# OSD62-PM-BRK.net
KiCad netlist of a schematic drawn in EAGLE
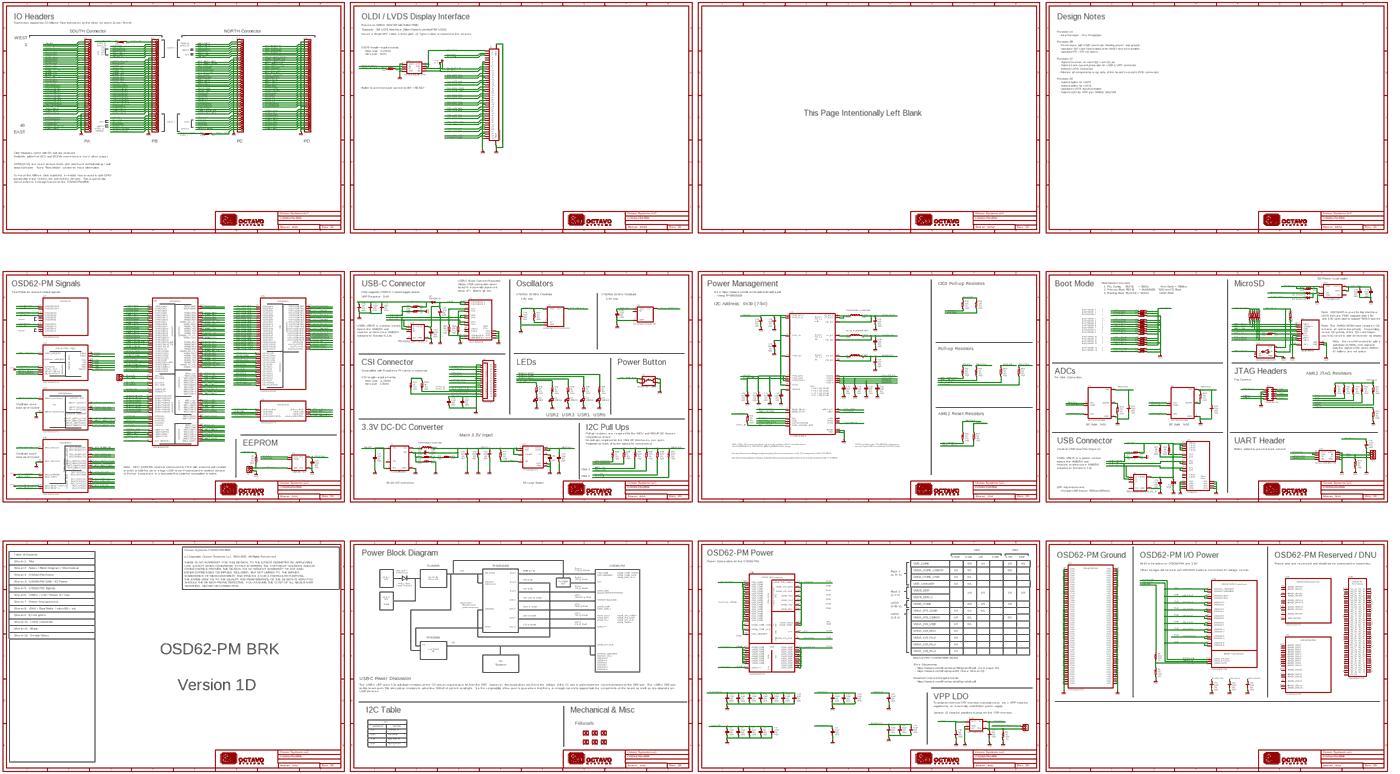
[diagram p0: schematic, sheet 1, overview]
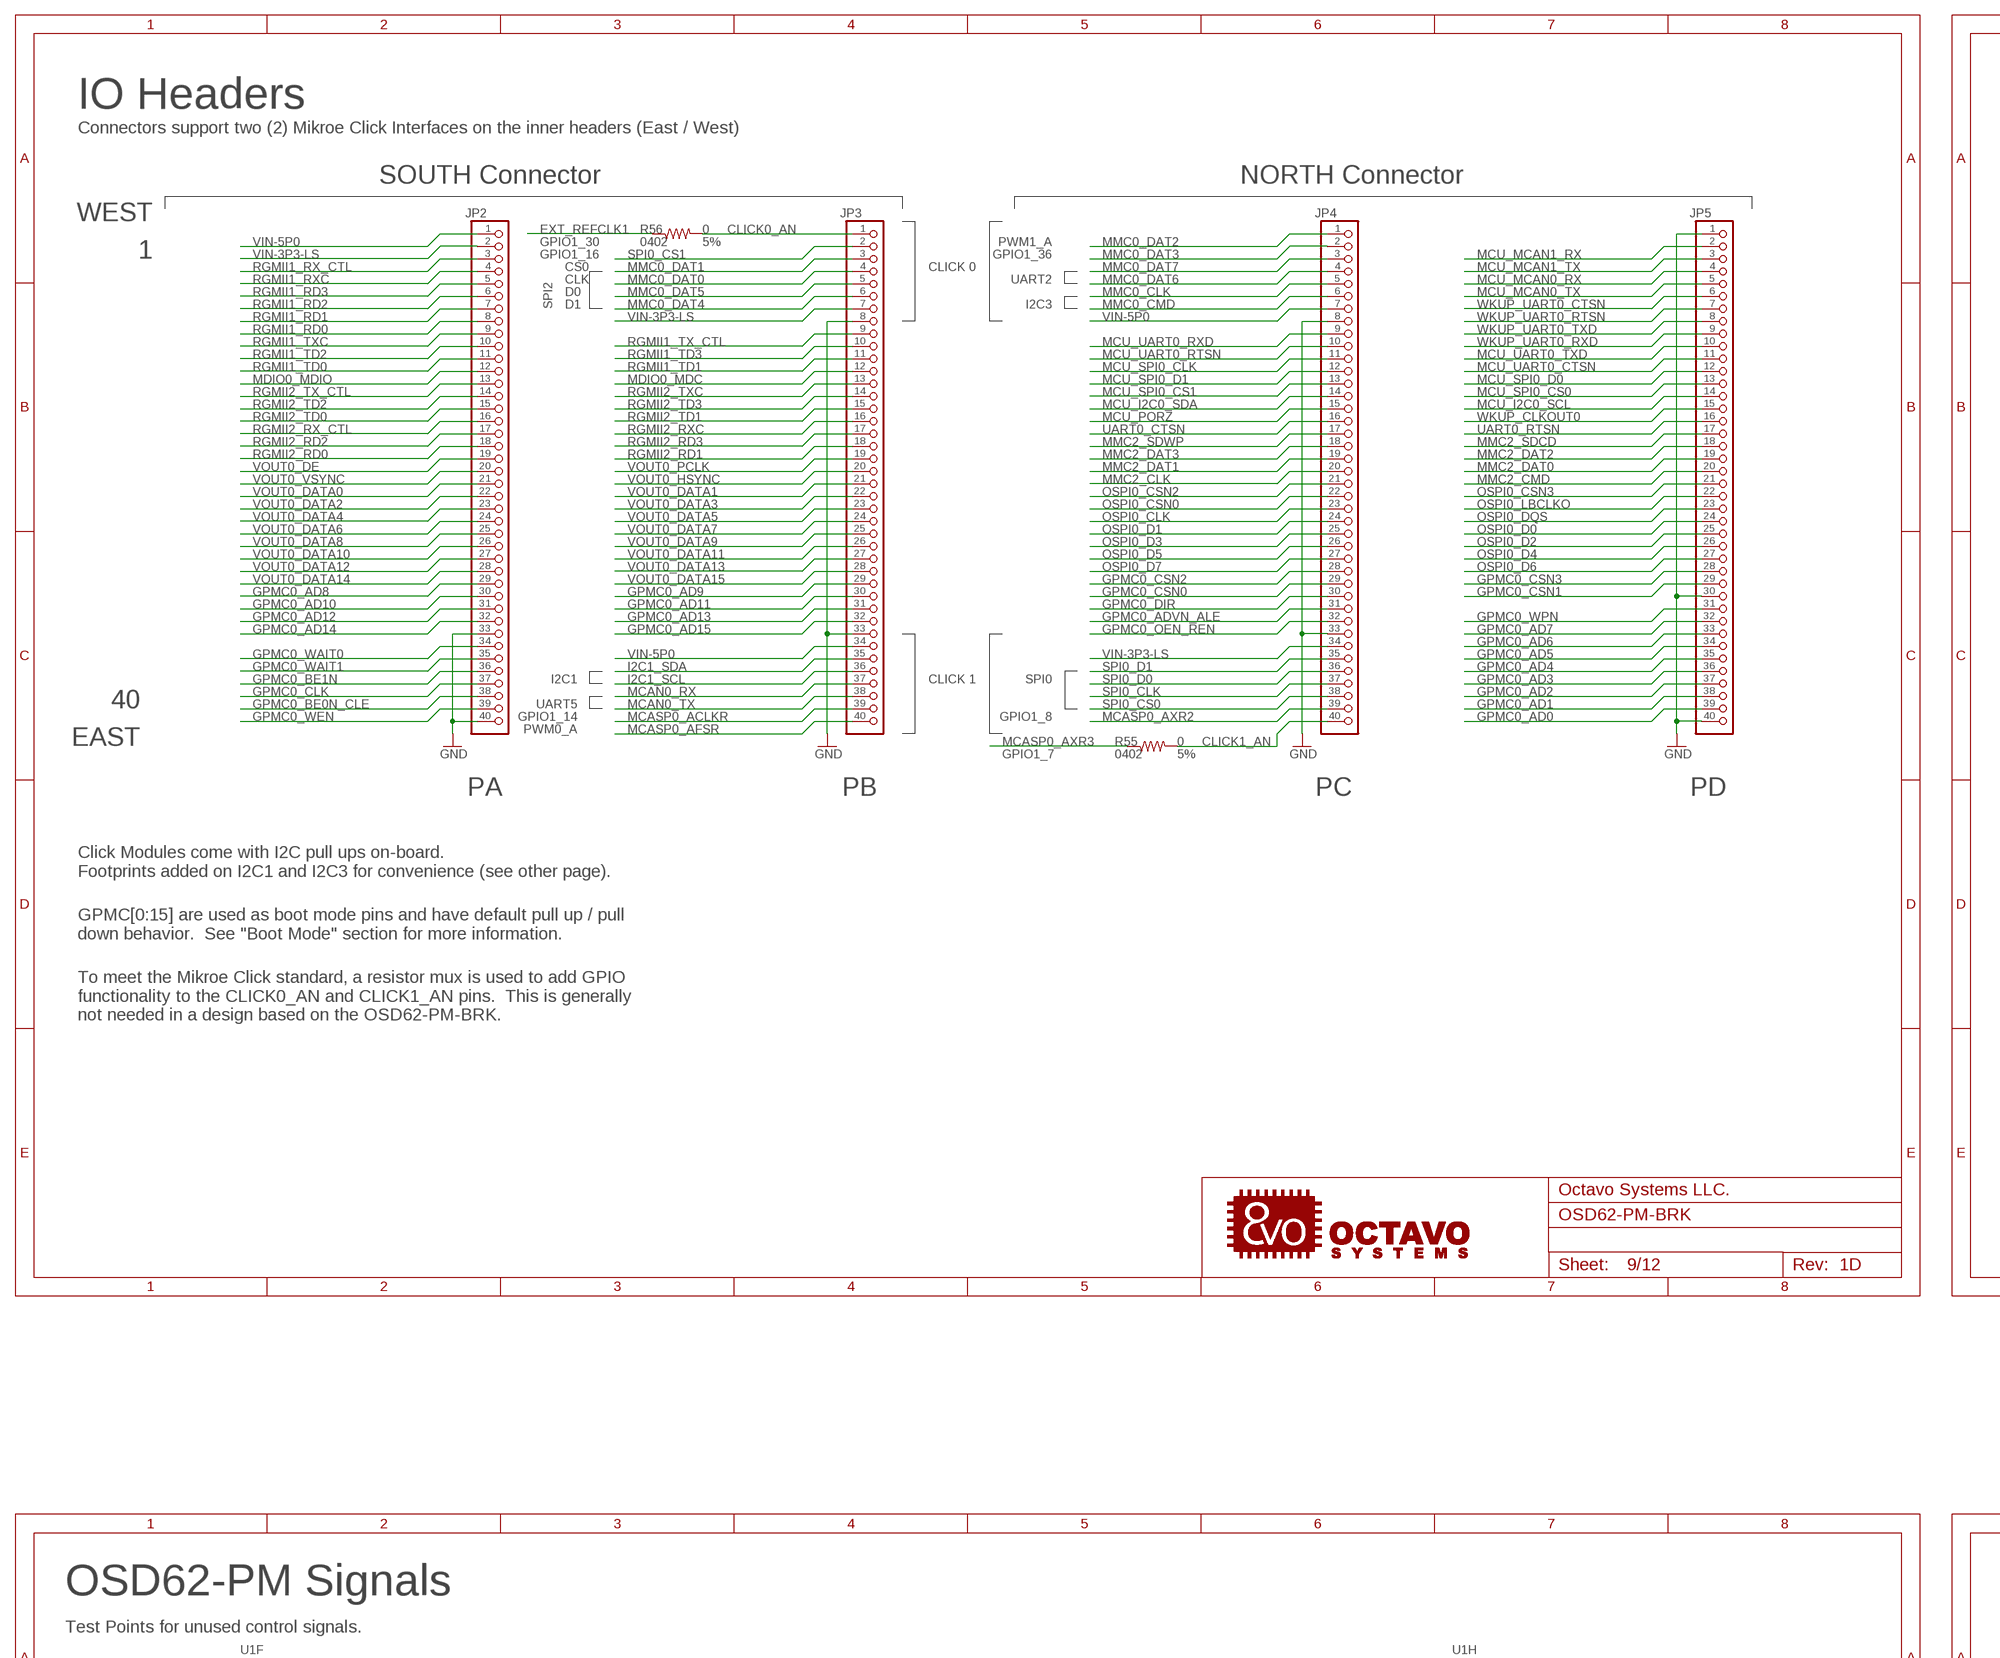
[diagram p1: schematic, sheet 1, part 1 of 8]
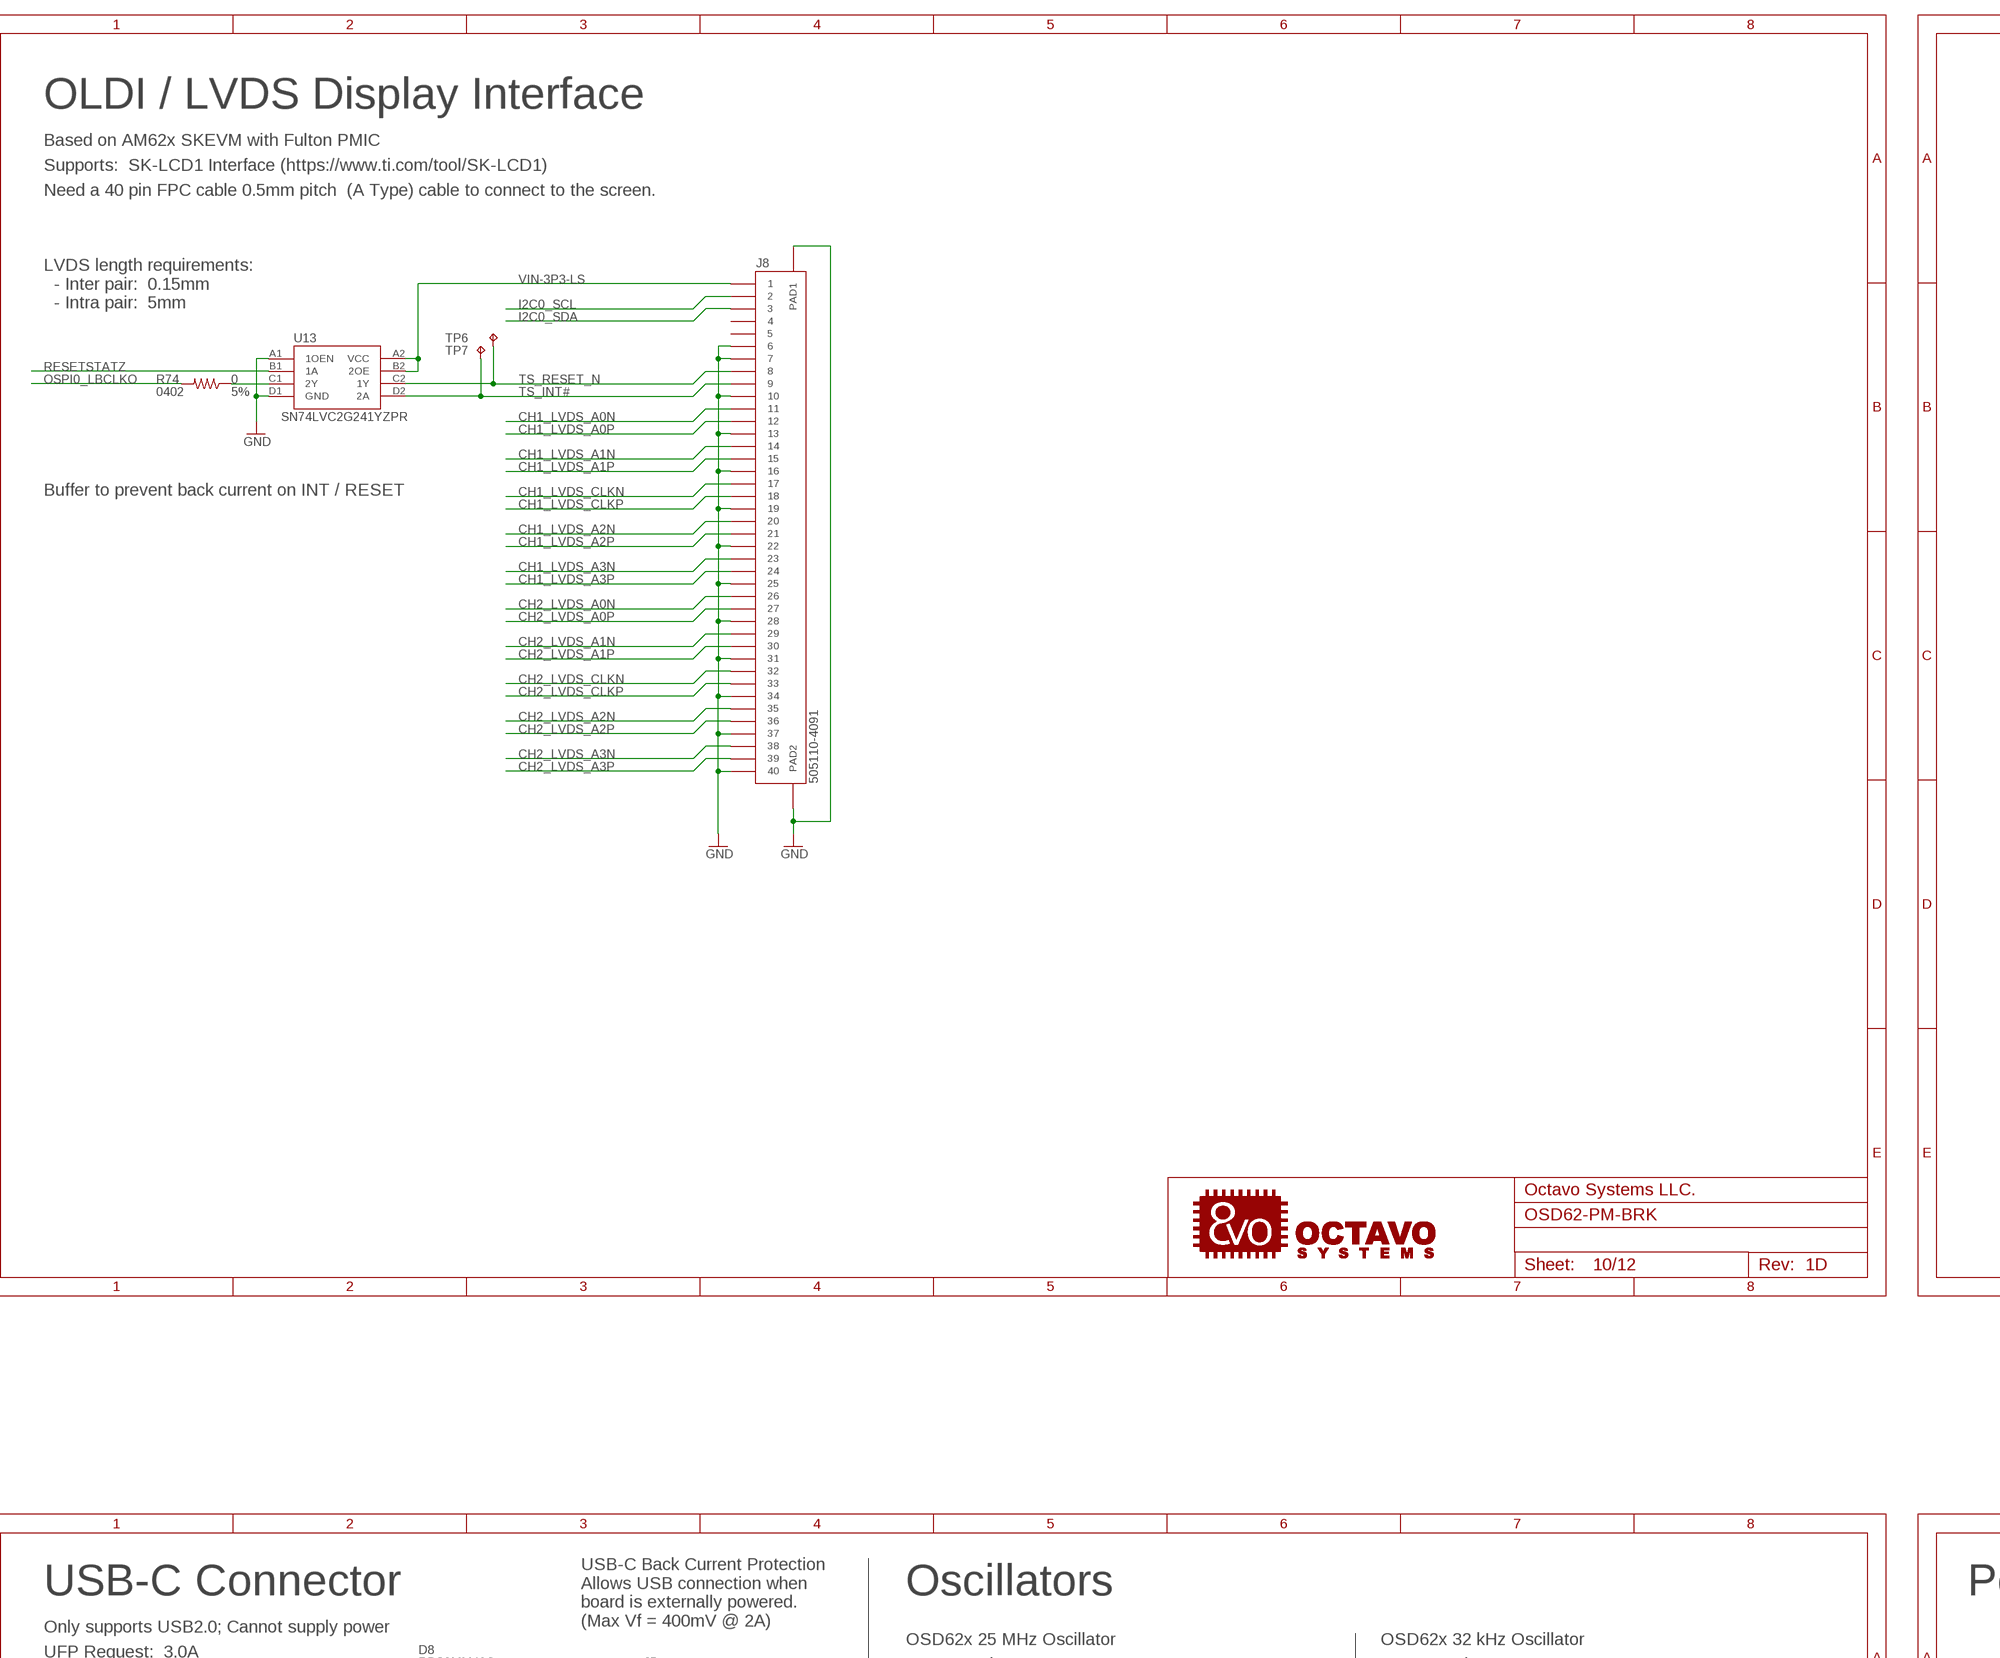
[diagram p2: schematic, sheet 1, part 2 of 8]
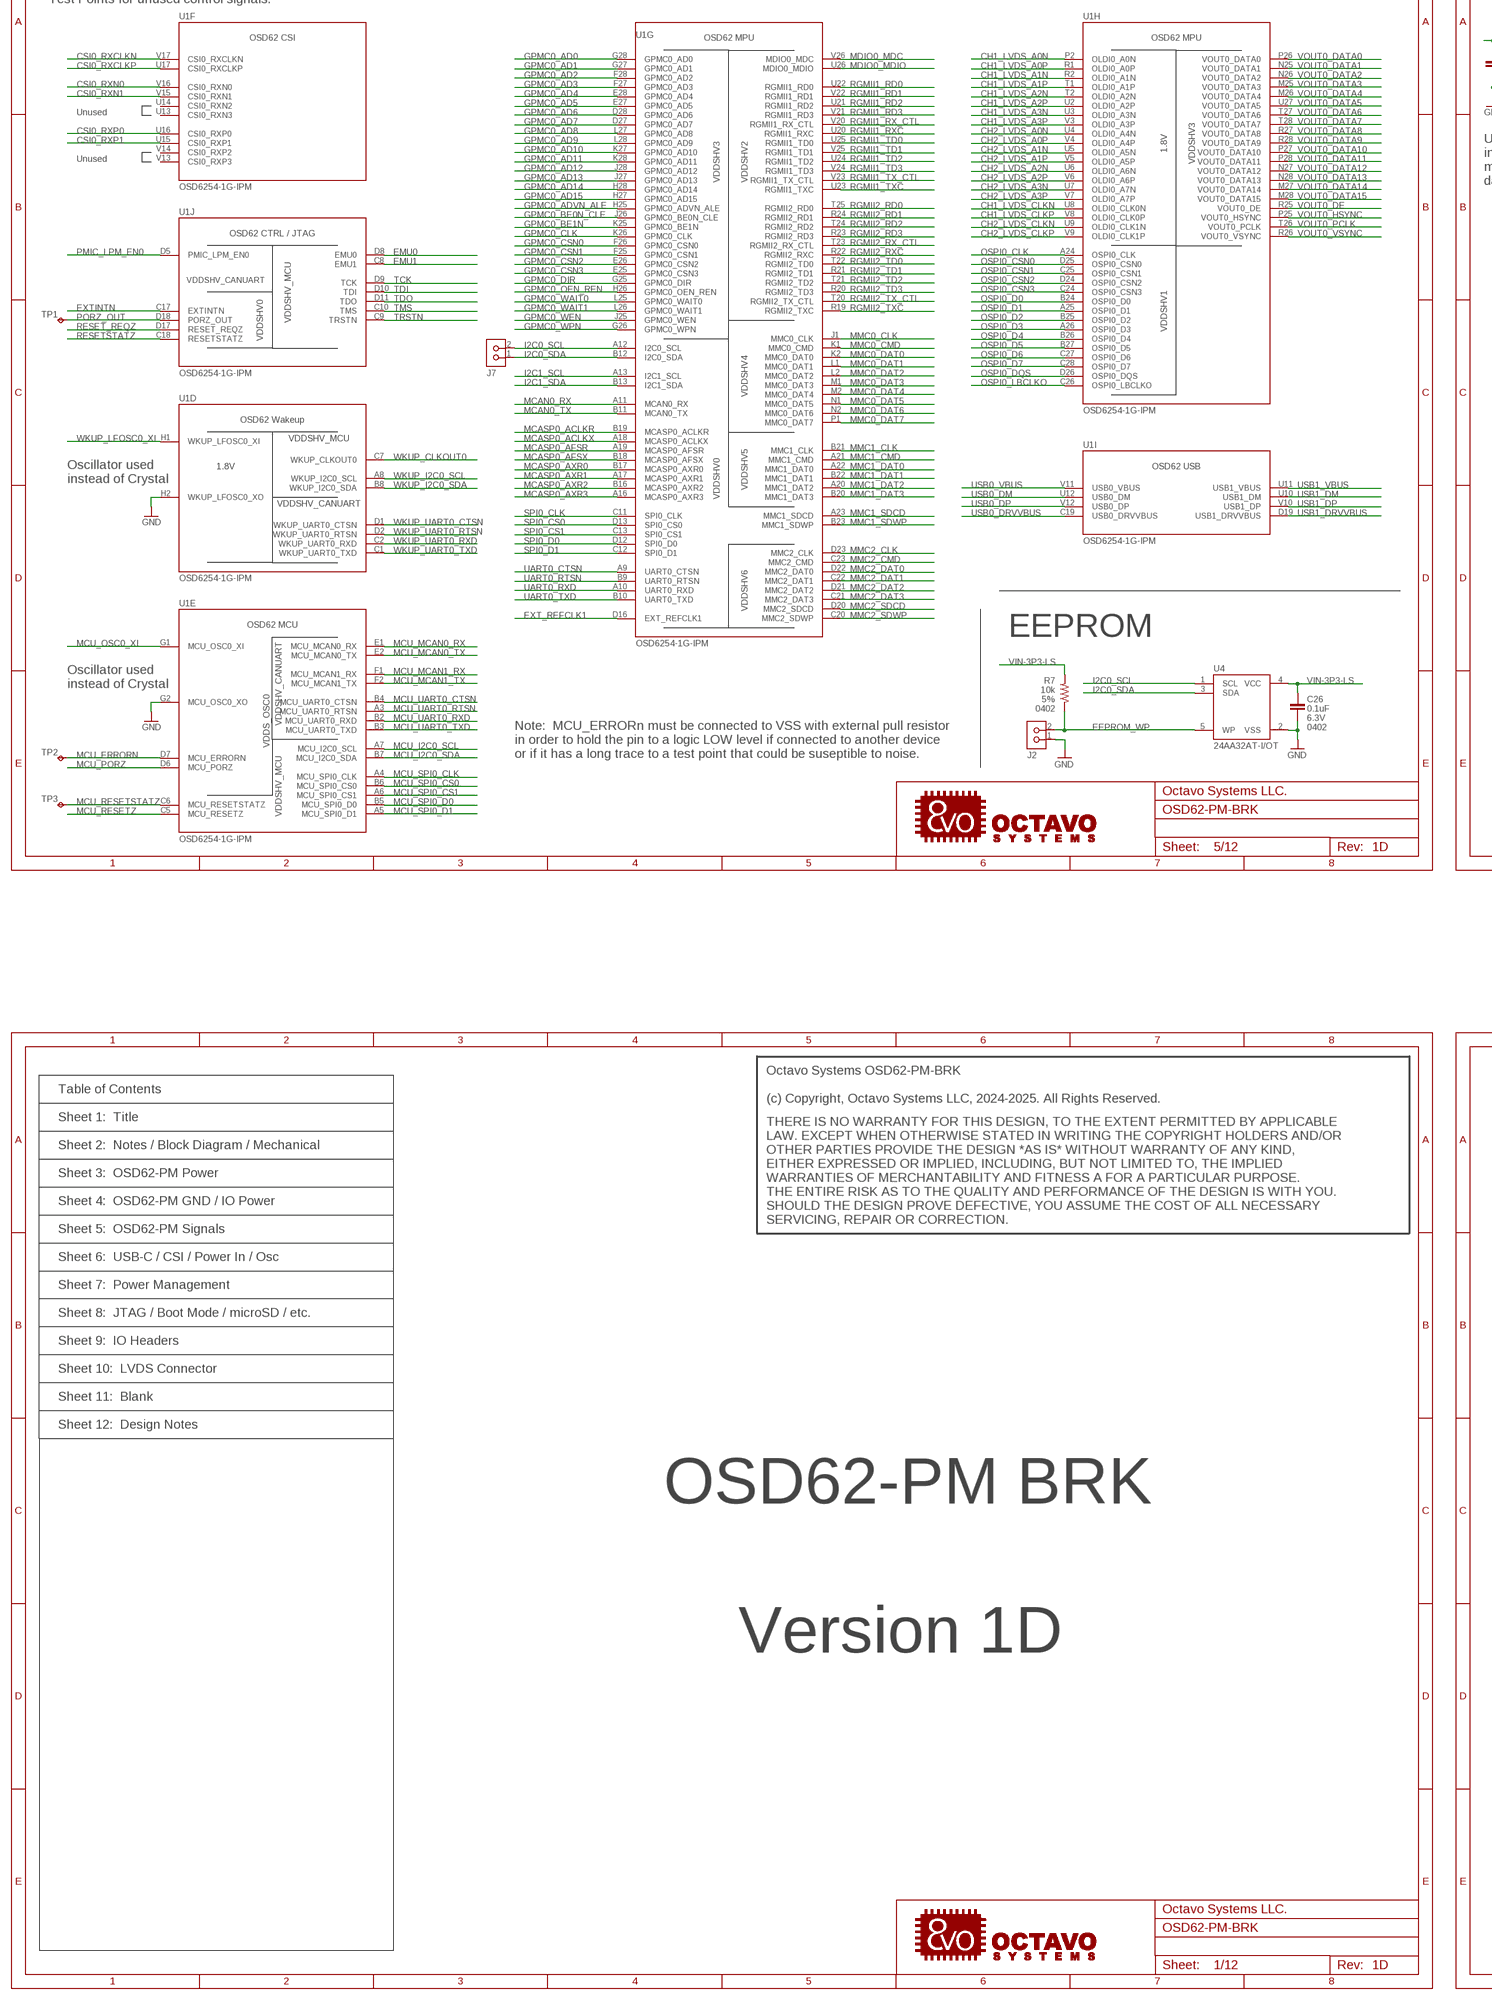
[diagram p3: schematic, sheet 1, part 3 of 8]
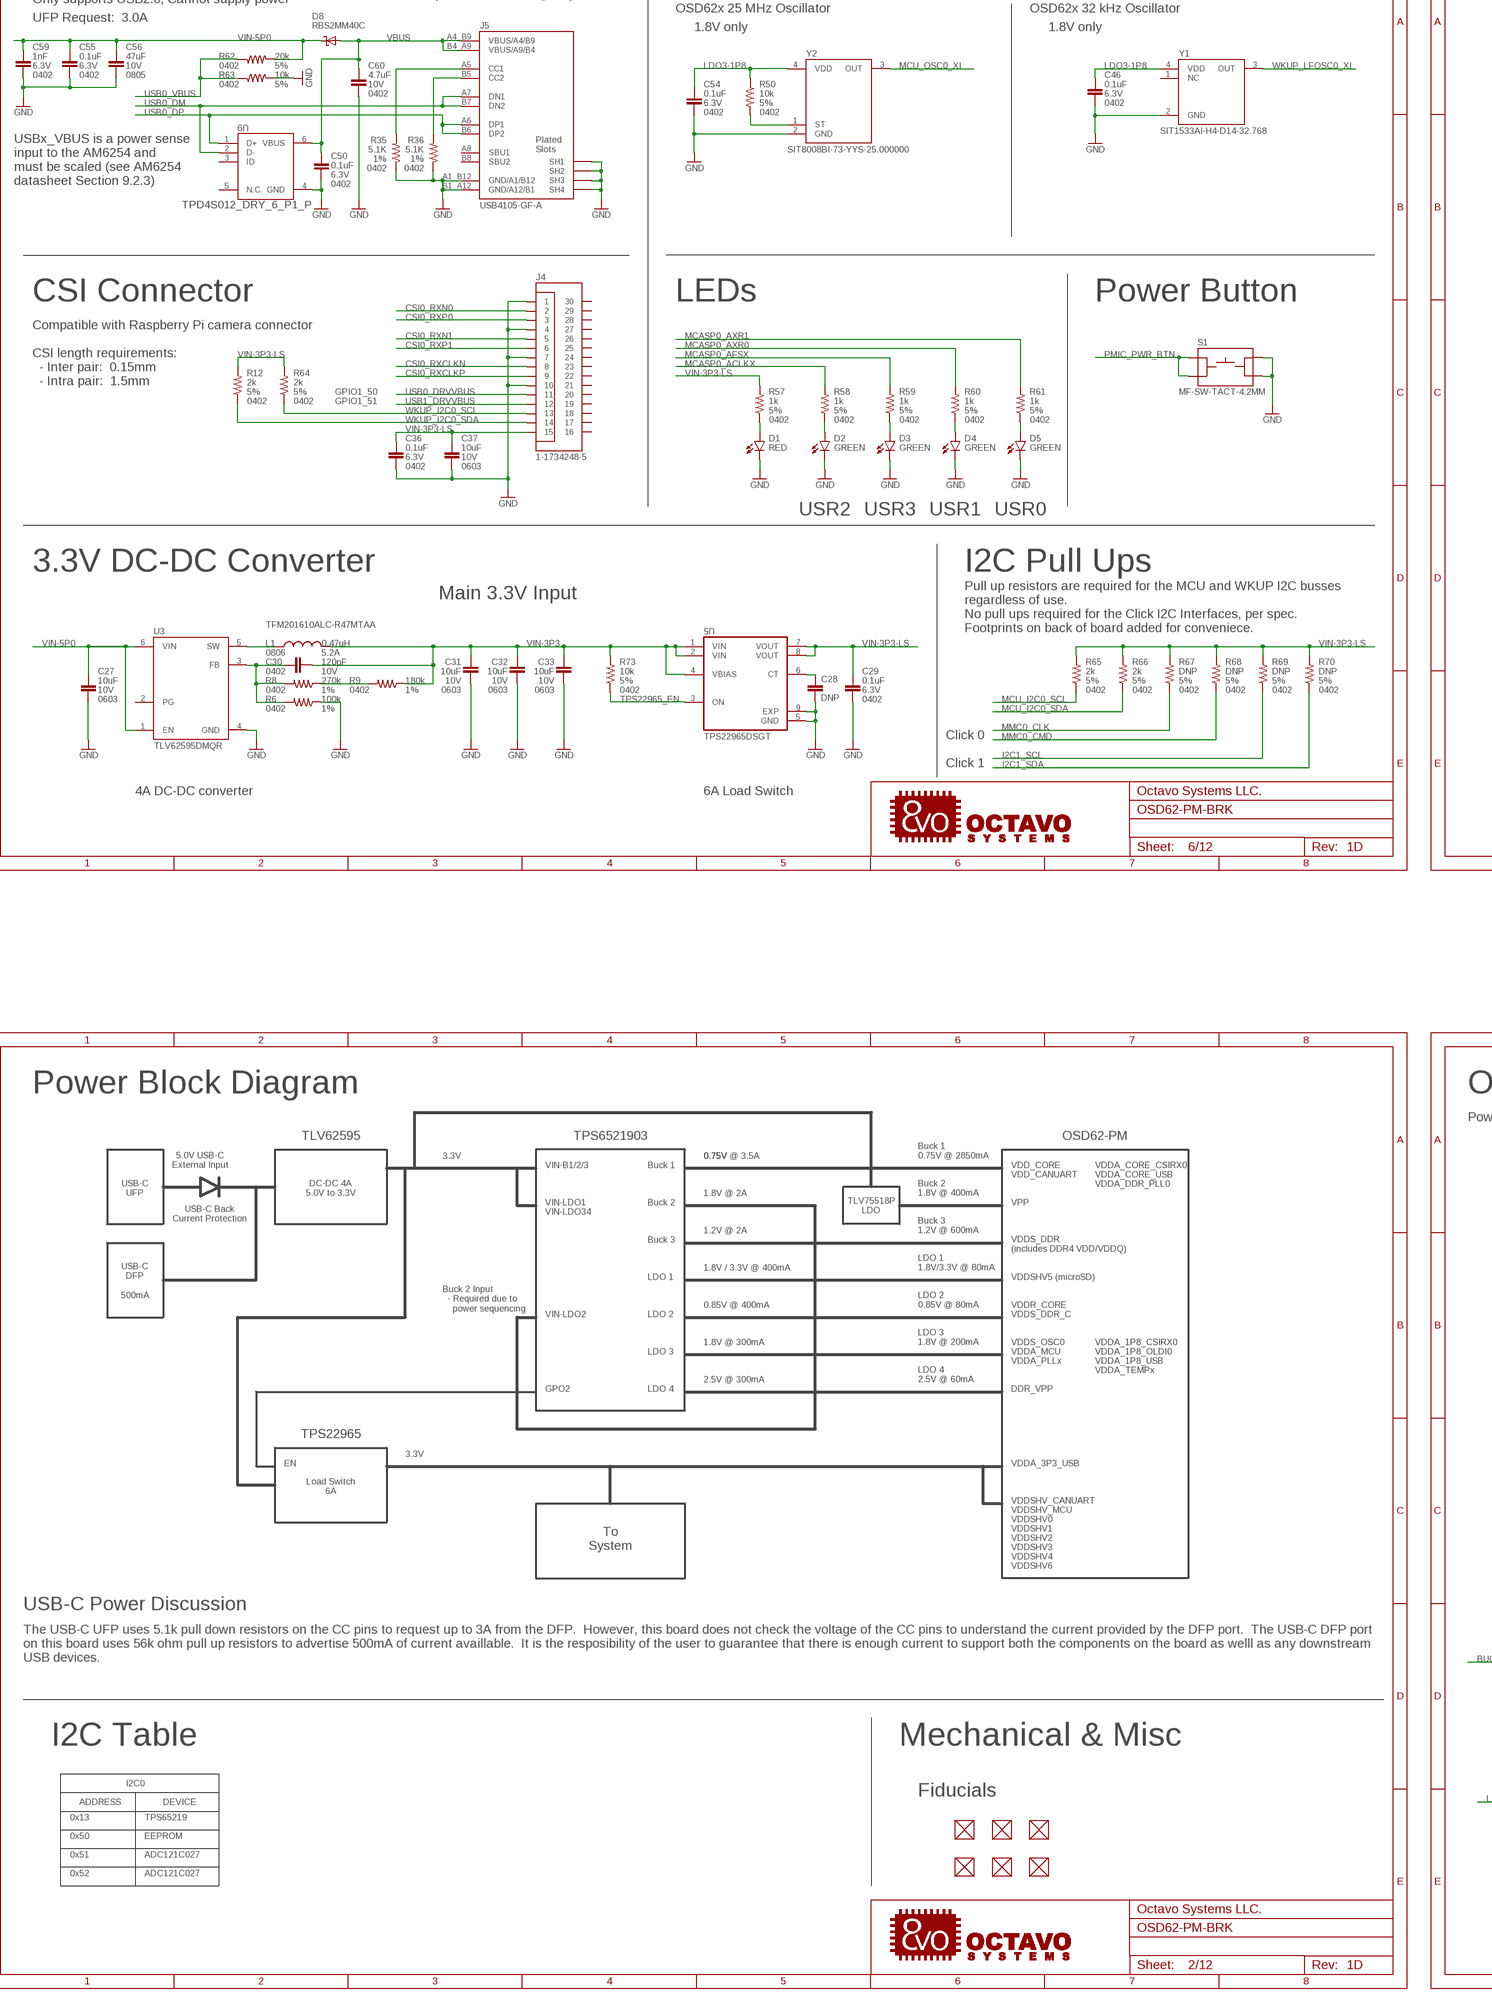
[diagram p4: schematic, sheet 1, part 4 of 8]
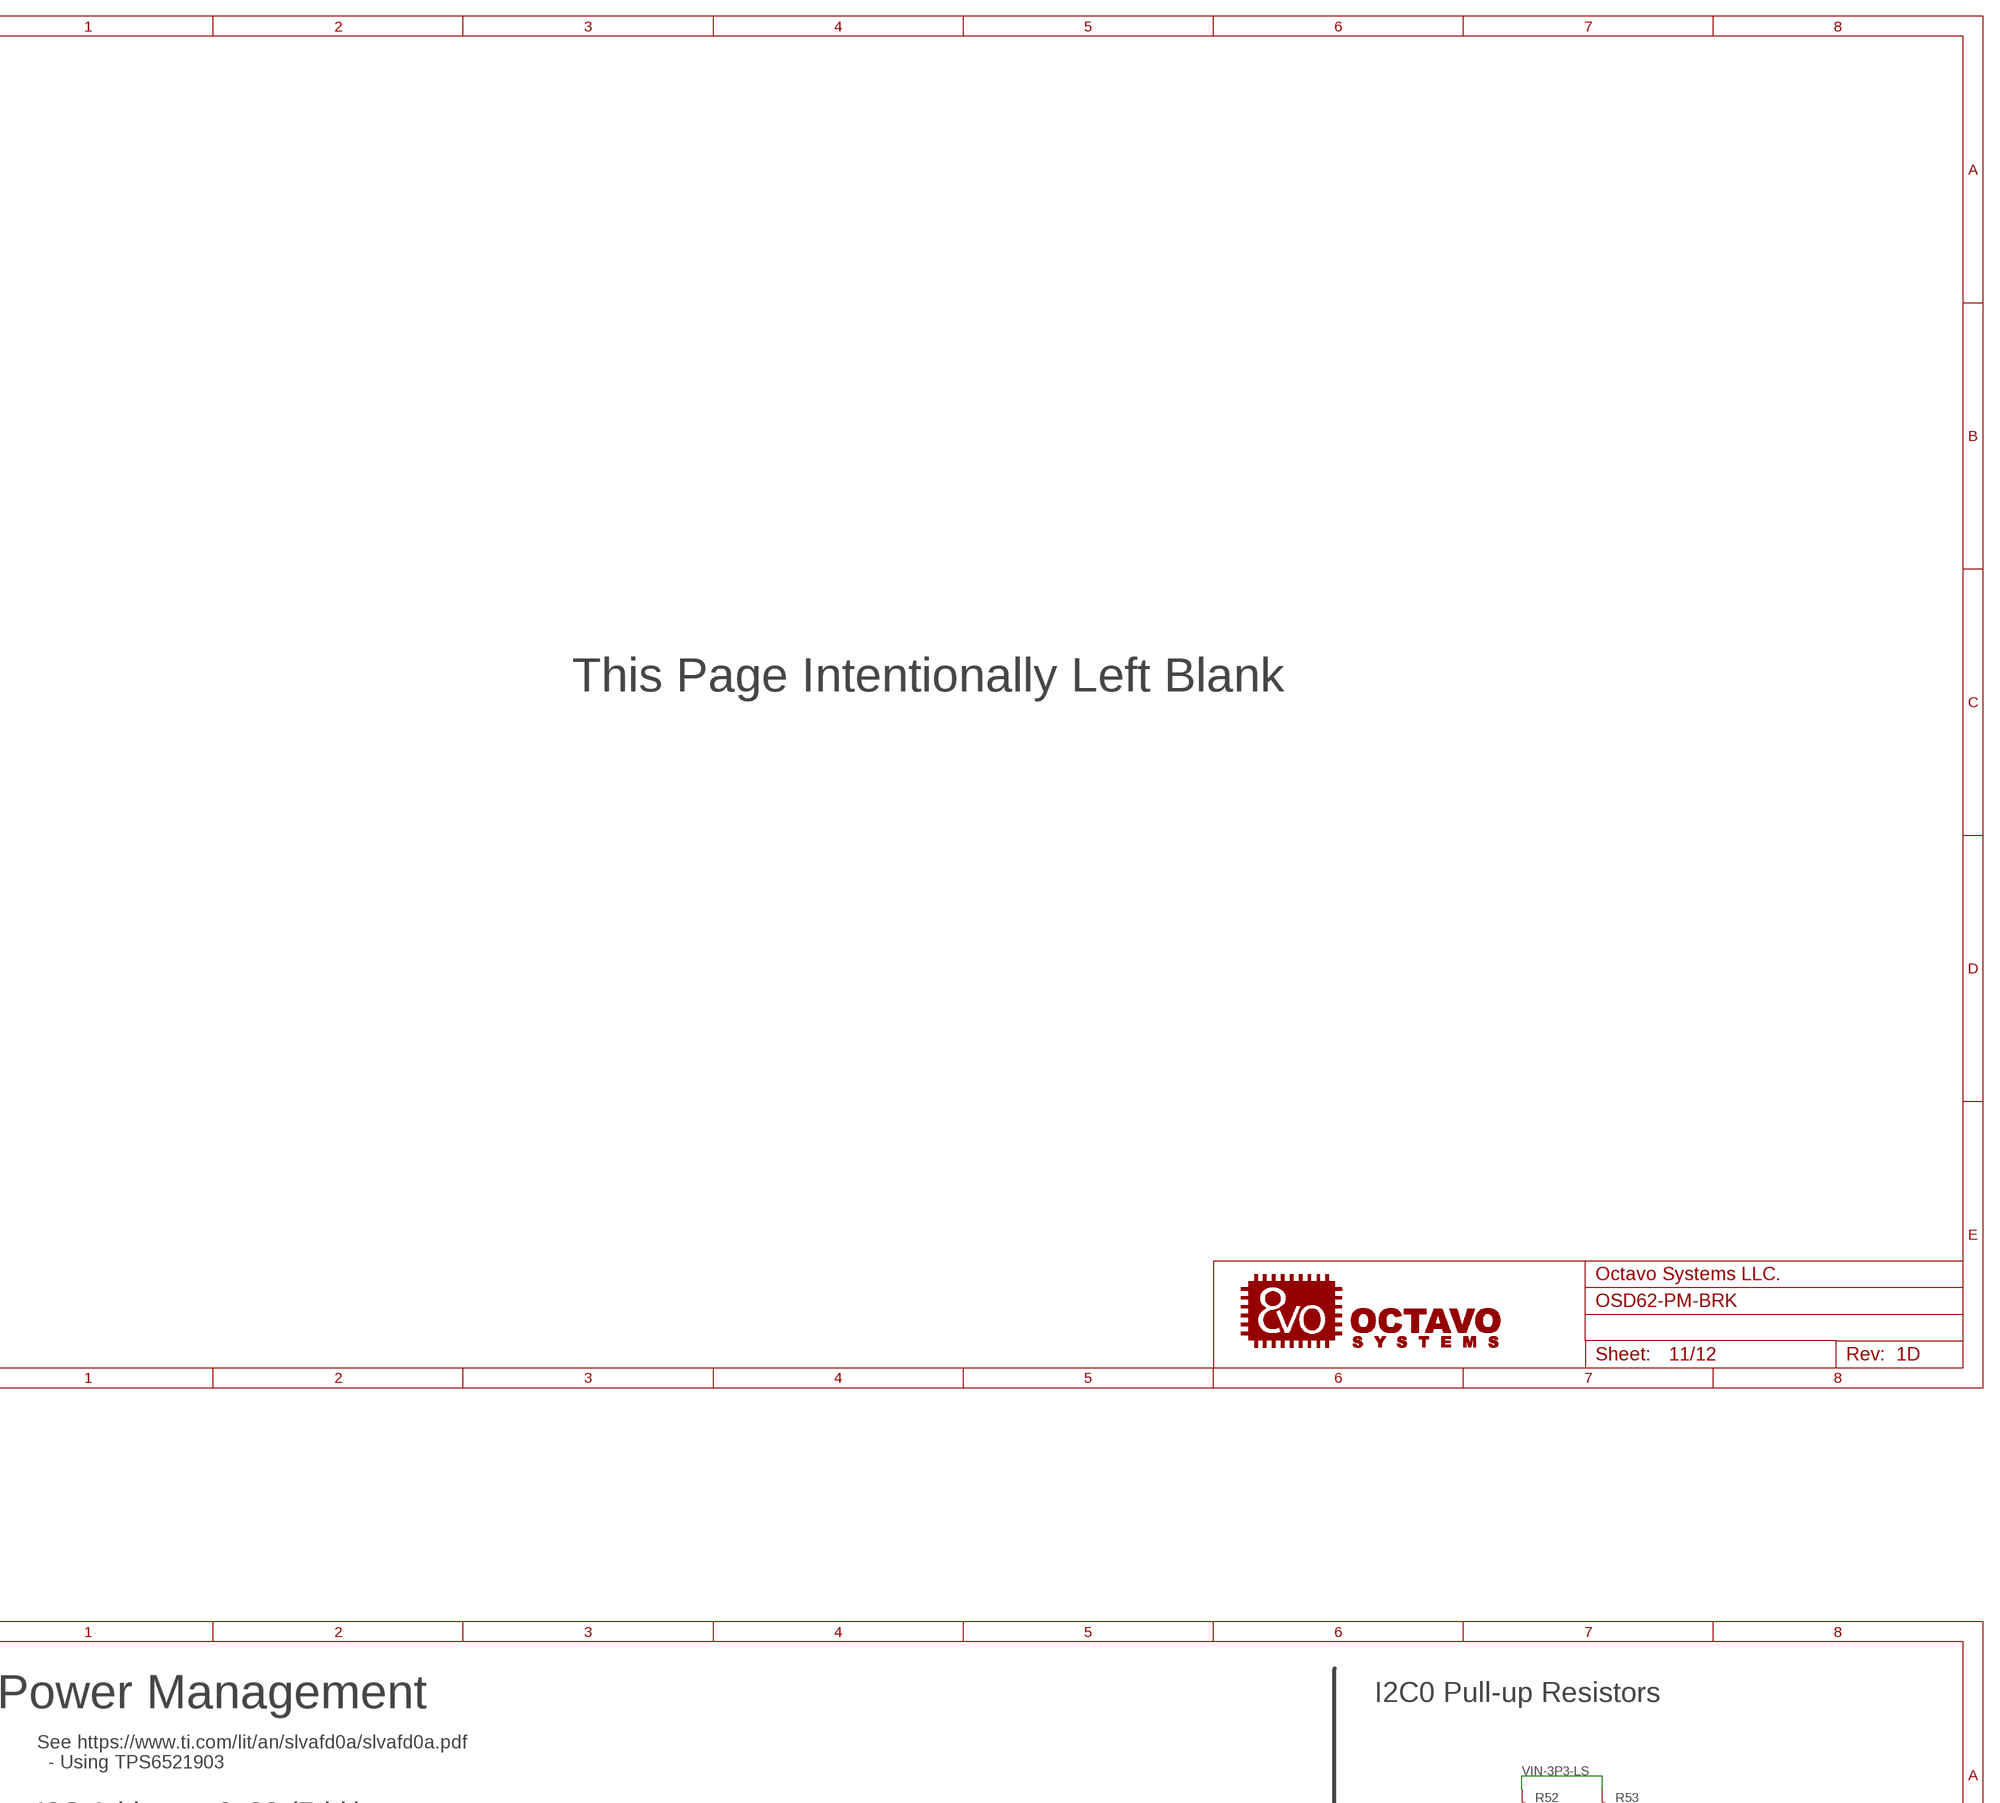
[diagram p5: schematic, sheet 1, part 5 of 8]
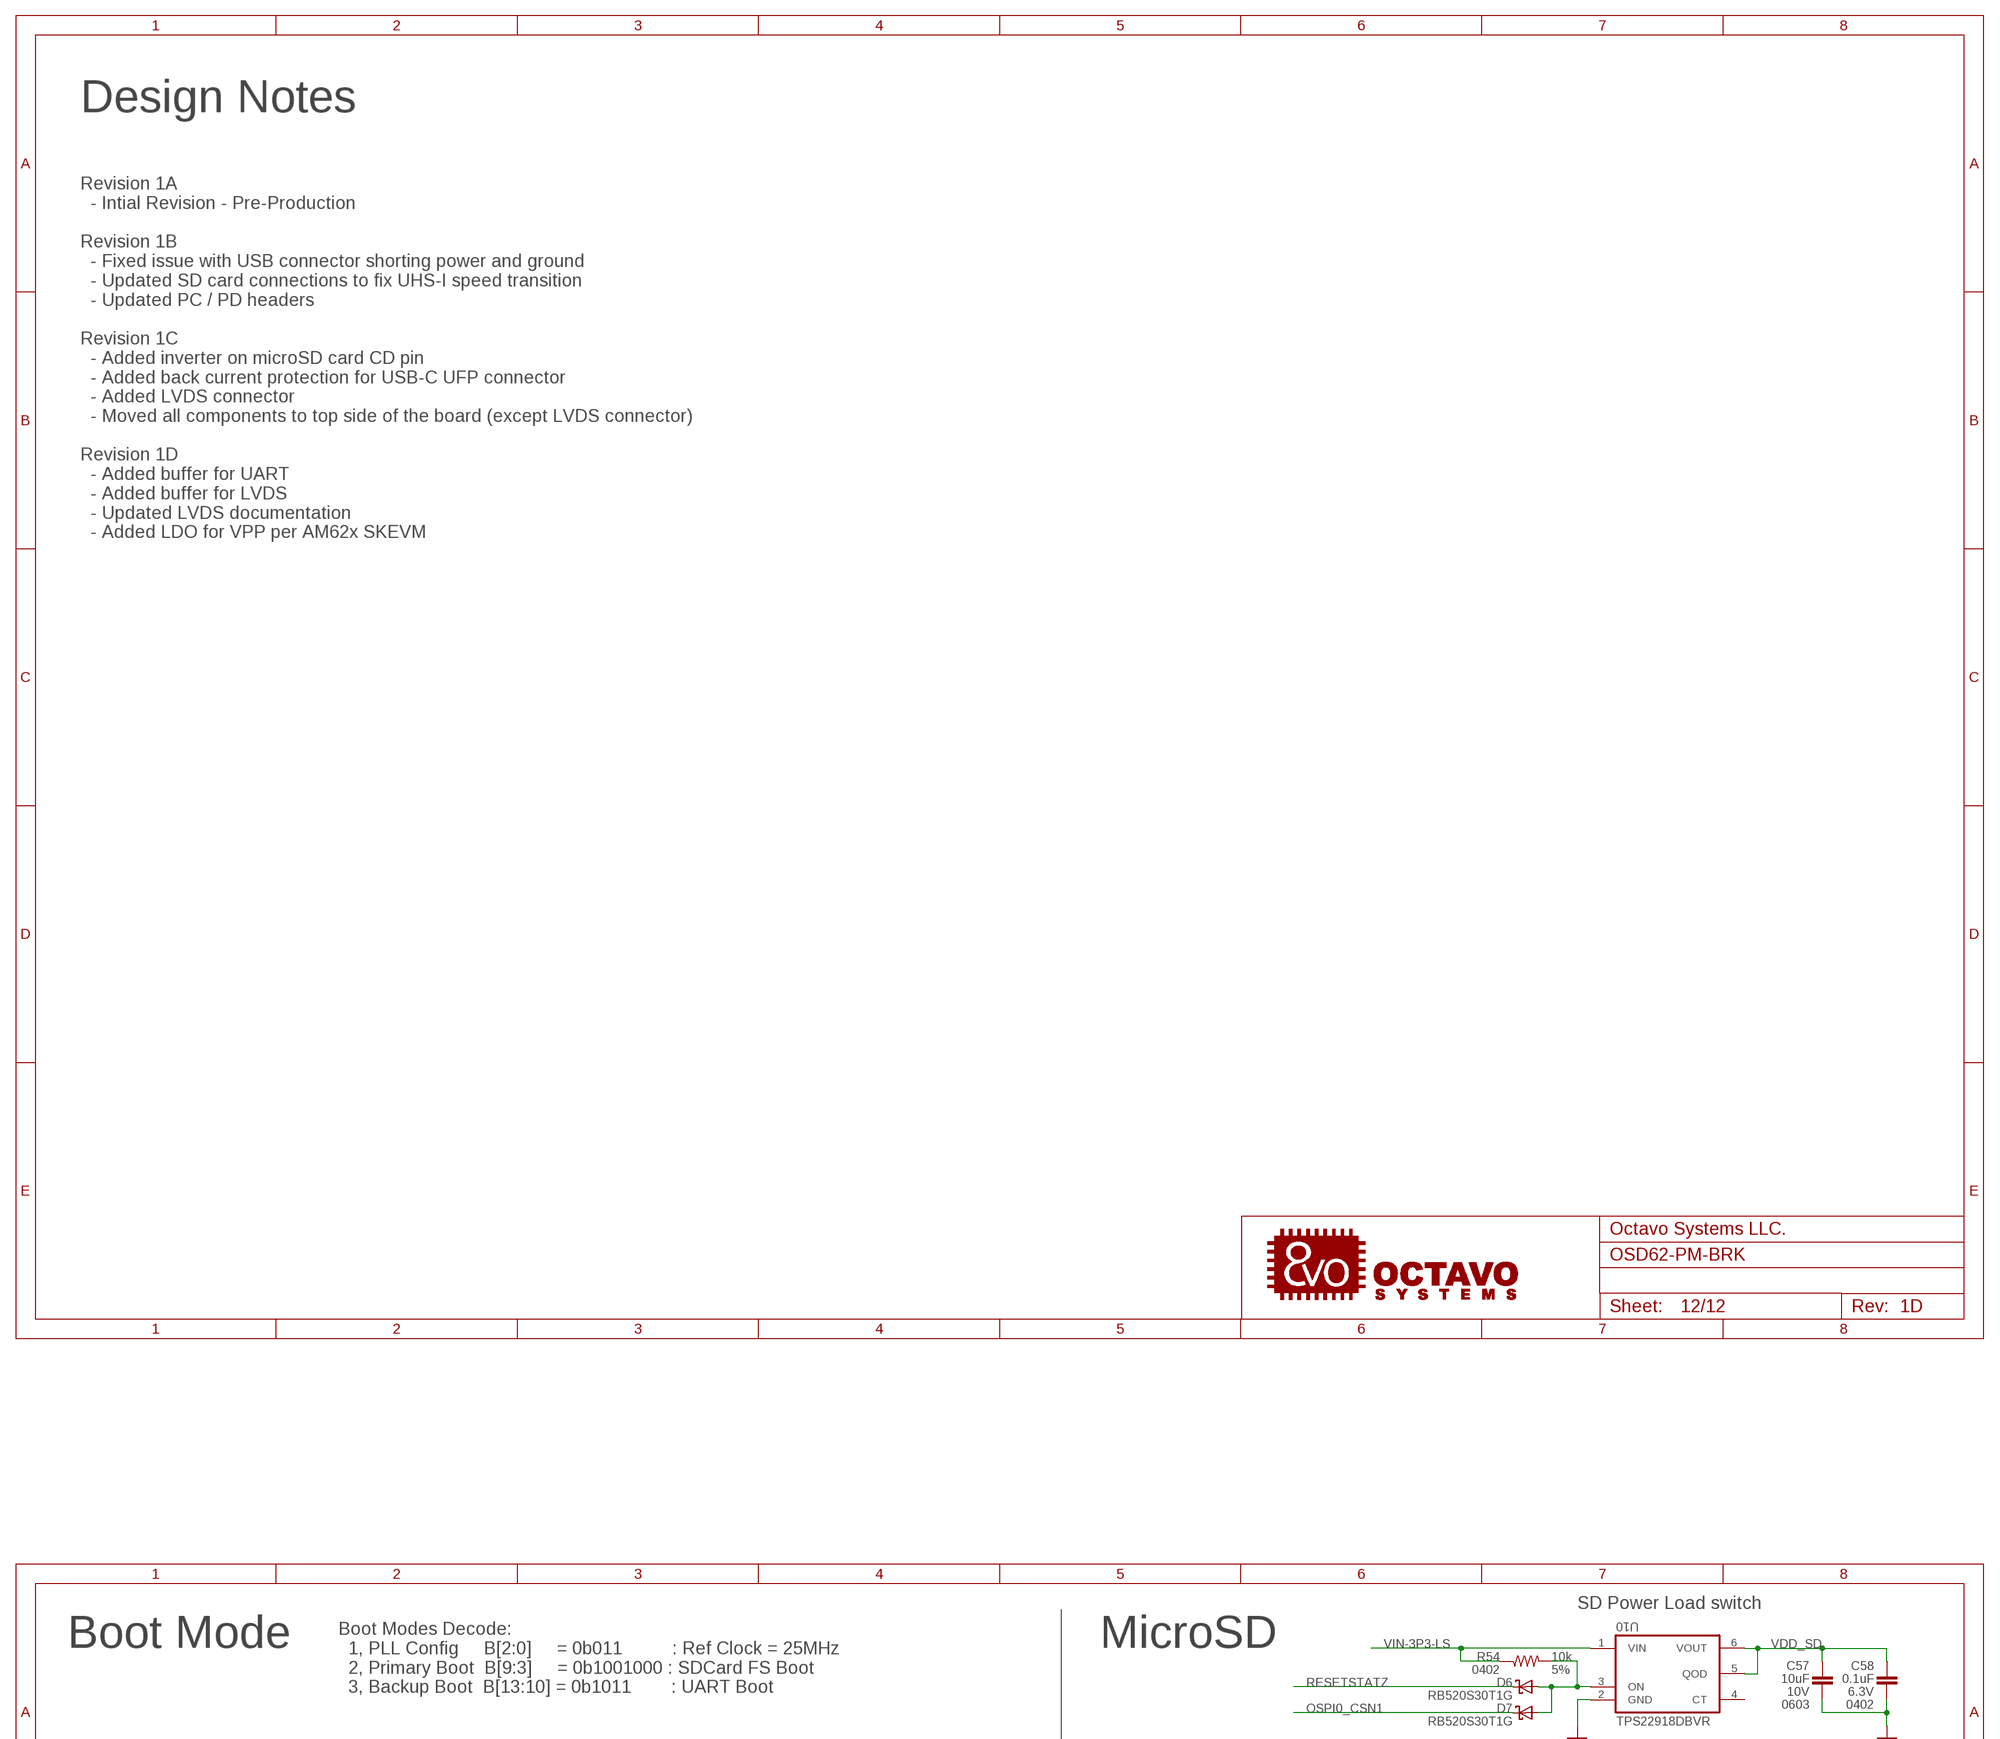
[diagram p6: schematic, sheet 1, part 6 of 8]
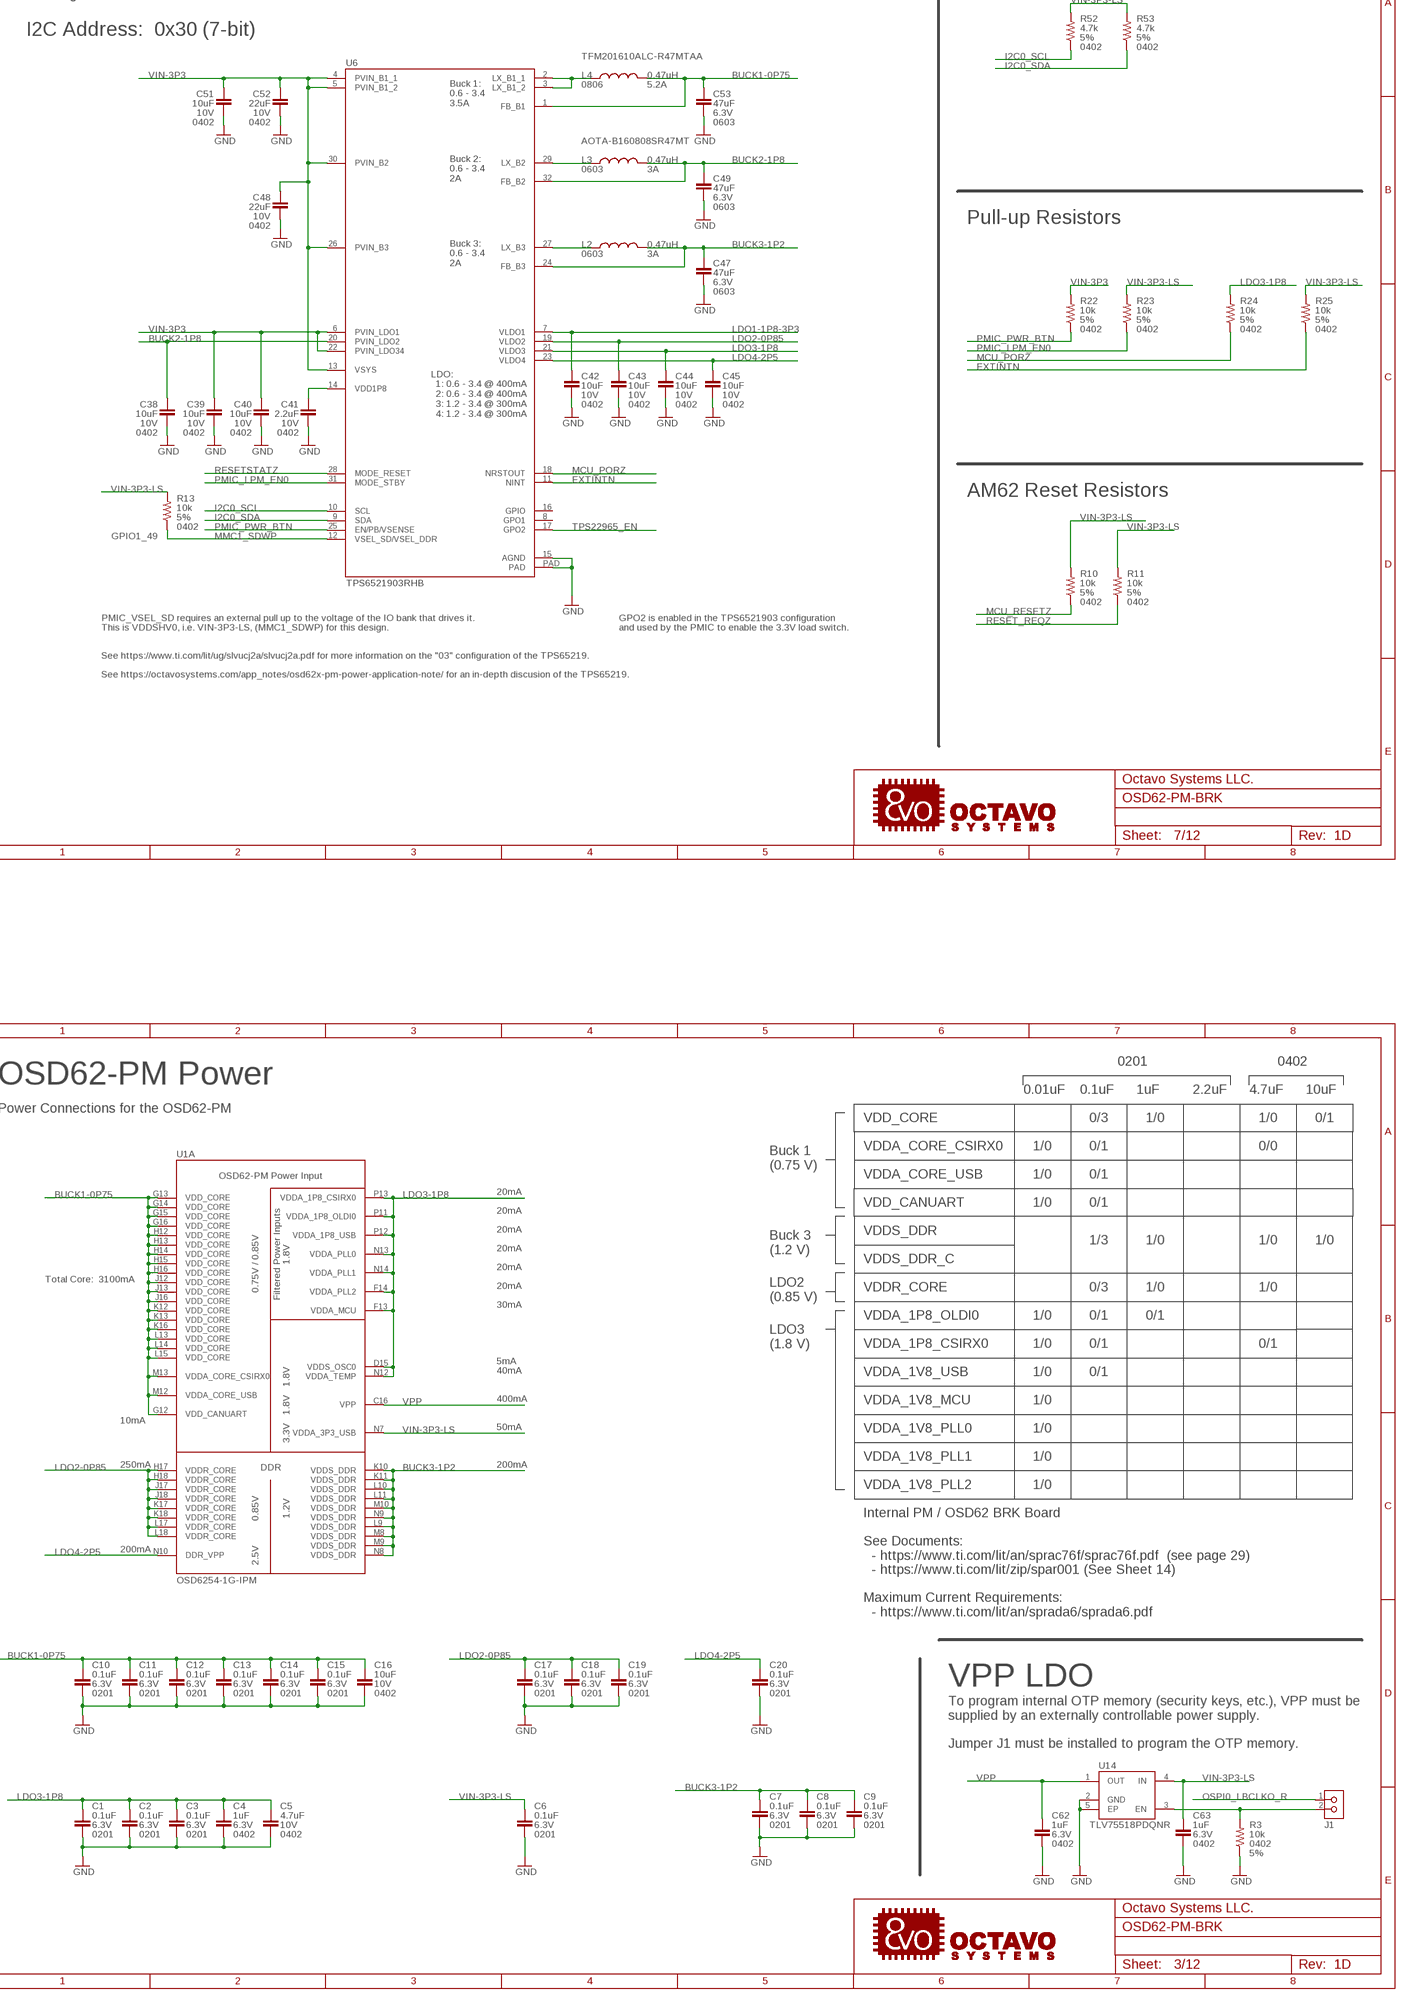
[diagram p7: schematic, sheet 1, part 7 of 8]
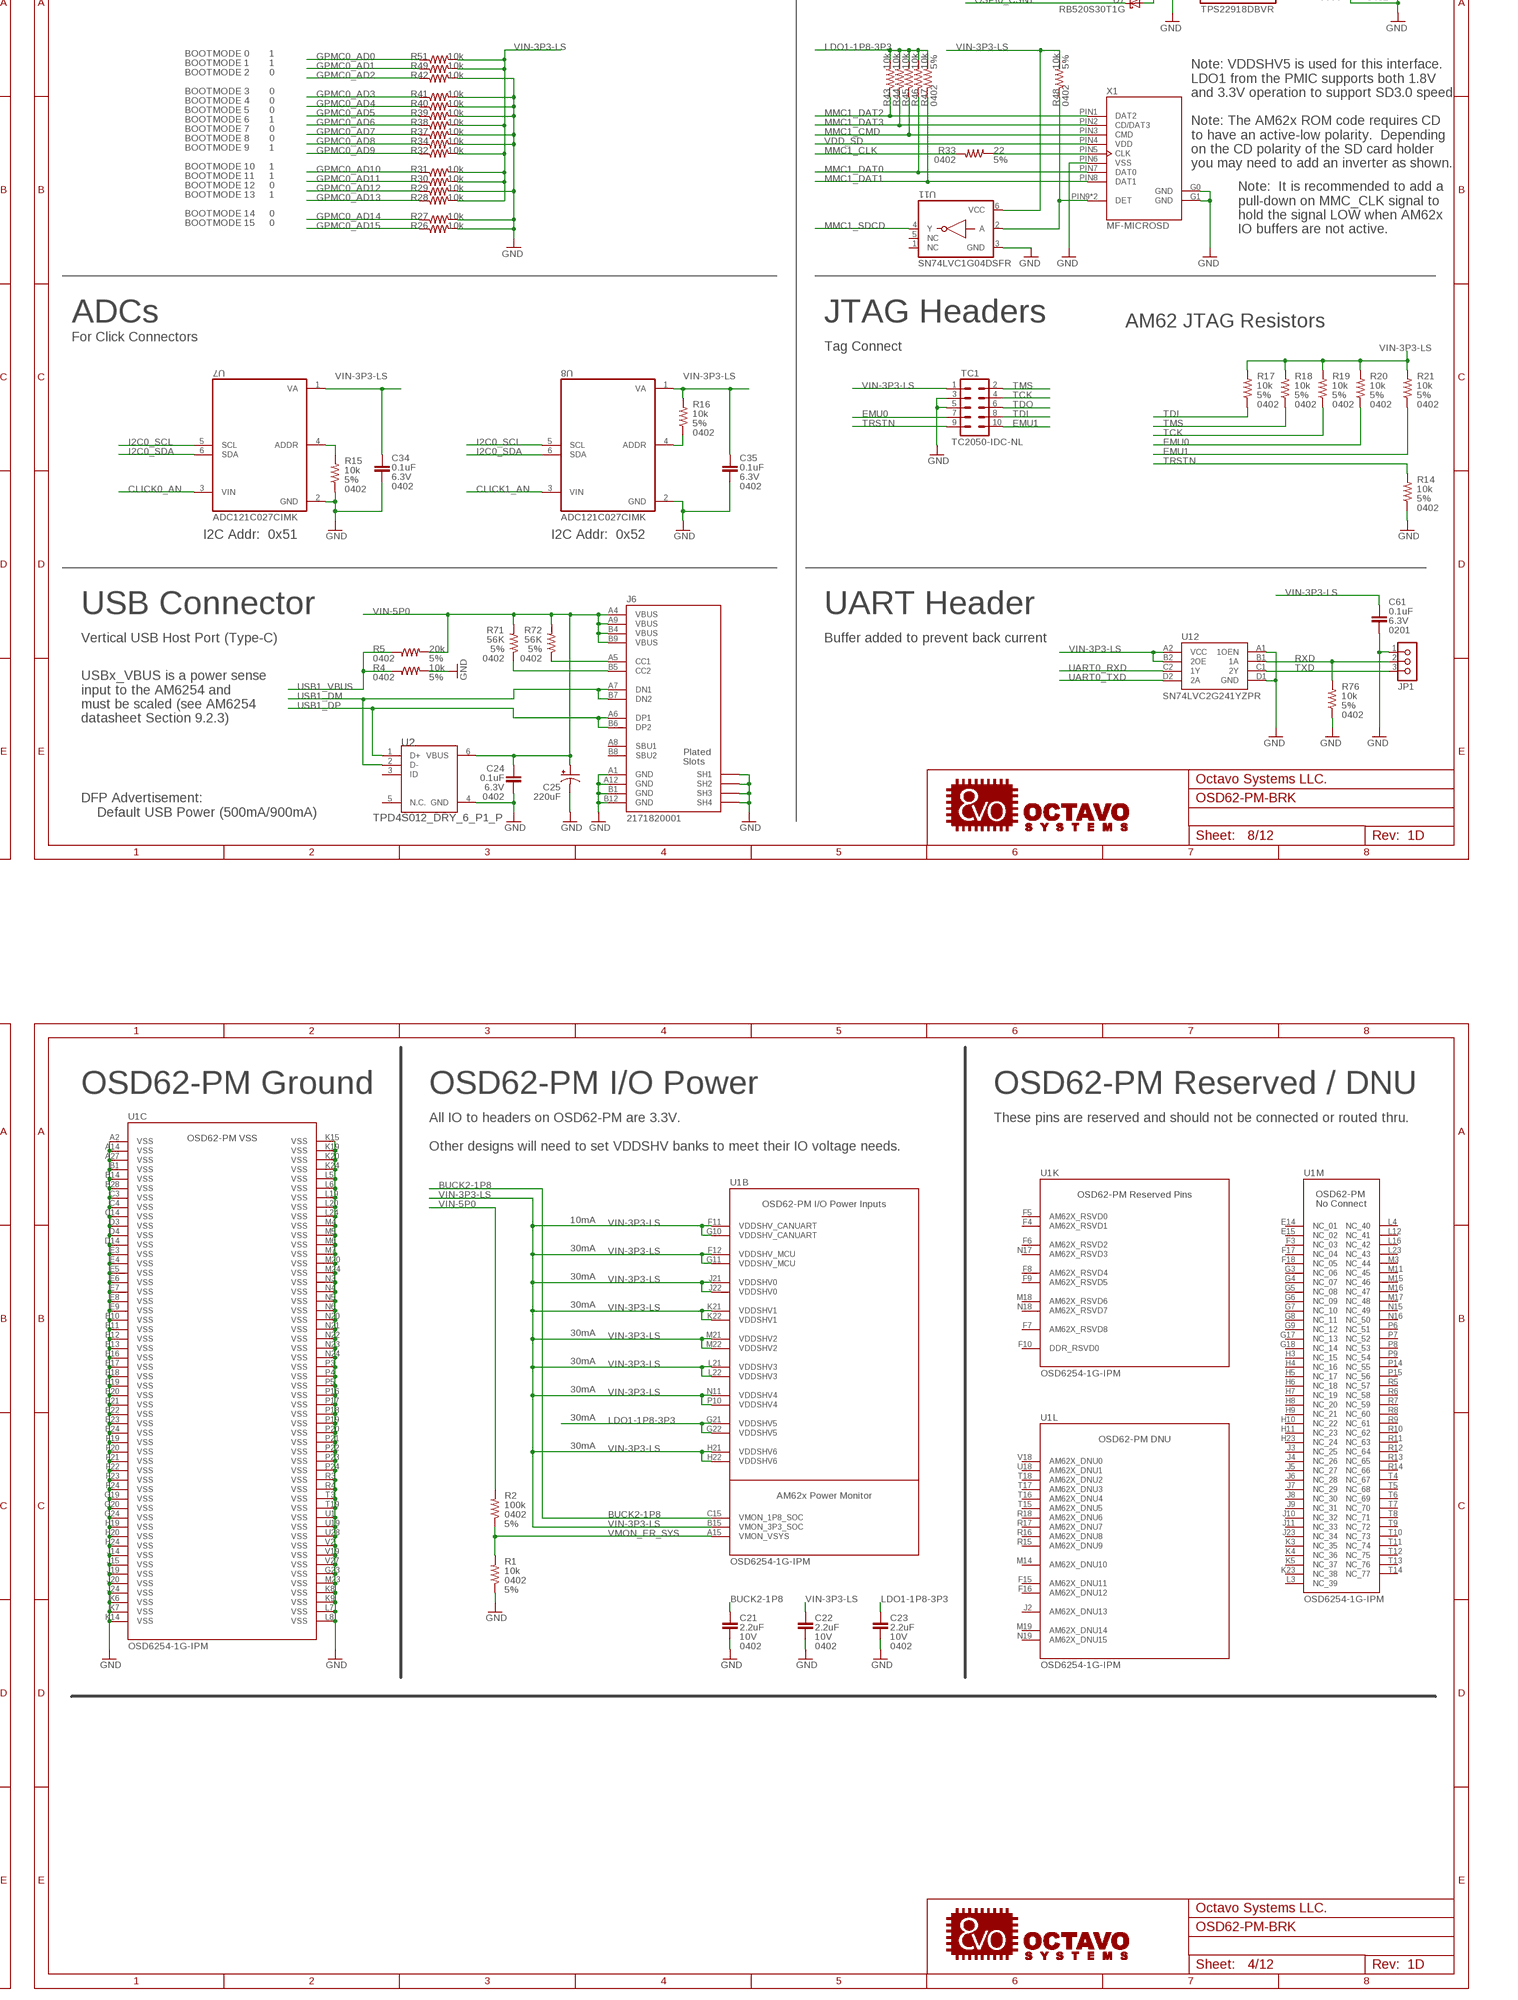
[diagram p8: schematic, sheet 1, part 8 of 8]

(export (version "E")
  (design (tool "Eeschema 10.0.6"))
  (components
    (comp (ref "C1")
      (value "0.1uF")
      (footprint "eagle-import:C0201")
      (fields (field (name "SIZE") "0201") (field (name "VOLTAGE") "6.3V"))
      (libsource (lib "eagle-import") (part "CC0201"))
    )
    (comp (ref "C2")
      (value "0.1uF")
      (footprint "eagle-import:C0201")
      (fields (field (name "SIZE") "0201") (field (name "VOLTAGE") "6.3V"))
      (libsource (lib "eagle-import") (part "CC0201"))
    )
    (comp (ref "C3")
      (value "0.1uF")
      (footprint "eagle-import:C0201")
      (fields (field (name "SIZE") "0201") (field (name "VOLTAGE") "6.3V"))
      (libsource (lib "eagle-import") (part "CC0201"))
    )
    (comp (ref "C4")
      (value "1uF")
      (footprint "eagle-import:C0402")
      (fields (field (name "SIZE") "0402") (field (name "VOLTAGE") "6.3V"))
      (libsource (lib "eagle-import") (part "CC0402"))
    )
    (comp (ref "C5")
      (value "4.7uF")
      (footprint "eagle-import:C0402")
      (fields (field (name "SIZE") "0402") (field (name "VOLTAGE") "10V"))
      (libsource (lib "eagle-import") (part "CC0402"))
    )
    (comp (ref "C6")
      (value "0.1uF")
      (footprint "eagle-import:C0201")
      (fields (field (name "SIZE") "0201") (field (name "VOLTAGE") "6.3V"))
      (libsource (lib "eagle-import") (part "CC0201"))
    )
    (comp (ref "C7")
      (value "0.1uF")
      (footprint "eagle-import:C0201")
      (fields (field (name "SIZE") "0201") (field (name "VOLTAGE") "6.3V"))
      (libsource (lib "eagle-import") (part "CC0201"))
    )
    (comp (ref "C8")
      (value "0.1uF")
      (footprint "eagle-import:C0201")
      (fields (field (name "SIZE") "0201") (field (name "VOLTAGE") "6.3V"))
      (libsource (lib "eagle-import") (part "CC0201"))
    )
    (comp (ref "C9")
      (value "0.1uF")
      (footprint "eagle-import:C0201")
      (fields (field (name "SIZE") "0201") (field (name "VOLTAGE") "6.3V"))
      (libsource (lib "eagle-import") (part "CC0201"))
    )
    (comp (ref "C10")
      (value "0.1uF")
      (footprint "eagle-import:C0201")
      (fields (field (name "SIZE") "0201") (field (name "VOLTAGE") "6.3V"))
      (libsource (lib "eagle-import") (part "CC0201"))
    )
    (comp (ref "C11")
      (value "0.1uF")
      (footprint "eagle-import:C0201")
      (fields (field (name "SIZE") "0201") (field (name "VOLTAGE") "6.3V"))
      (libsource (lib "eagle-import") (part "CC0201"))
    )
    (comp (ref "C12")
      (value "0.1uF")
      (footprint "eagle-import:C0201")
      (fields (field (name "SIZE") "0201") (field (name "VOLTAGE") "6.3V"))
      (libsource (lib "eagle-import") (part "CC0201"))
    )
    (comp (ref "C13")
      (value "0.1uF")
      (footprint "eagle-import:C0201")
      (fields (field (name "SIZE") "0201") (field (name "VOLTAGE") "6.3V"))
      (libsource (lib "eagle-import") (part "CC0201"))
    )
    (comp (ref "C14")
      (value "0.1uF")
      (footprint "eagle-import:C0201")
      (fields (field (name "SIZE") "0201") (field (name "VOLTAGE") "6.3V"))
      (libsource (lib "eagle-import") (part "CC0201"))
    )
    (comp (ref "C15")
      (value "0.1uF")
      (footprint "eagle-import:C0201")
      (fields (field (name "SIZE") "0201") (field (name "VOLTAGE") "6.3V"))
      (libsource (lib "eagle-import") (part "CC0201"))
    )
    (comp (ref "C16")
      (value "10uF")
      (footprint "eagle-import:C0402")
      (fields (field (name "SIZE") "0402") (field (name "VOLTAGE") "10V"))
      (libsource (lib "eagle-import") (part "CC0402"))
    )
    (comp (ref "C17")
      (value "0.1uF")
      (footprint "eagle-import:C0201")
      (fields (field (name "SIZE") "0201") (field (name "VOLTAGE") "6.3V"))
      (libsource (lib "eagle-import") (part "CC0201"))
    )
    (comp (ref "C18")
      (value "0.1uF")
      (footprint "eagle-import:C0201")
      (fields (field (name "SIZE") "0201") (field (name "VOLTAGE") "6.3V"))
      (libsource (lib "eagle-import") (part "CC0201"))
    )
    (comp (ref "C19")
      (value "0.1uF")
      (footprint "eagle-import:C0201")
      (fields (field (name "SIZE") "0201") (field (name "VOLTAGE") "6.3V"))
      (libsource (lib "eagle-import") (part "CC0201"))
    )
    (comp (ref "C20")
      (value "0.1uF")
      (footprint "eagle-import:C0201")
      (fields (field (name "SIZE") "0201") (field (name "VOLTAGE") "6.3V"))
      (libsource (lib "eagle-import") (part "CC0201"))
    )
    (comp (ref "C21")
      (value "2.2uF")
      (footprint "eagle-import:C0402")
      (fields (field (name "SIZE") "0402") (field (name "VOLTAGE") "10V"))
      (libsource (lib "eagle-import") (part "CC0402"))
    )
    (comp (ref "C22")
      (value "2.2uF")
      (footprint "eagle-import:C0402")
      (fields (field (name "SIZE") "0402") (field (name "VOLTAGE") "10V"))
      (libsource (lib "eagle-import") (part "CC0402"))
    )
    (comp (ref "C23")
      (value "2.2uF")
      (footprint "eagle-import:C0402")
      (fields (field (name "SIZE") "0402") (field (name "VOLTAGE") "10V"))
      (libsource (lib "eagle-import") (part "CC0402"))
    )
    (comp (ref "C24")
      (value "0.1uF")
      (footprint "eagle-import:C0402")
      (fields (field (name "SIZE") "0402") (field (name "SIZE_1") "0402") (field (name "VOLTAGE") "6.3V"))
      (libsource (lib "eagle-import") (part "CC0402"))
    )
    (comp (ref "C25")
      (value "220uF")
      (footprint "eagle-import:B_3528-21R")
      (libsource (lib "eagle-import") (part "CPOL-USB/3528-21R"))
    )
    (comp (ref "C26")
      (value "0.1uF")
      (footprint "eagle-import:C0402")
      (fields (field (name "SIZE") "0402") (field (name "VOLTAGE") "6.3V"))
      (libsource (lib "eagle-import") (part "CC0402"))
    )
    (comp (ref "C27")
      (value "10uF")
      (footprint "eagle-import:C0603")
      (fields (field (name "SIZE") "0603") (field (name "VOLTAGE") "10V"))
      (libsource (lib "eagle-import") (part "CC0603"))
    )
    (comp (ref "C28")
      (value "DNP")
      (footprint "eagle-import:C0402")
      (libsource (lib "eagle-import") (part "CC0402"))
    )
    (comp (ref "C29")
      (value "0.1uF")
      (footprint "eagle-import:C0402")
      (fields (field (name "SIZE") "0402") (field (name "VOLTAGE") "6.3V"))
      (libsource (lib "eagle-import") (part "CC0402"))
    )
    (comp (ref "C30")
      (value "120pF")
      (footprint "eagle-import:C0402")
      (fields (field (name "SIZE") "0402") (field (name "VOLTAGE") "10V"))
      (libsource (lib "eagle-import") (part "CC0402"))
    )
    (comp (ref "C31")
      (value "10uF")
      (footprint "eagle-import:C0603")
      (fields (field (name "SIZE") "0603") (field (name "VOLTAGE") "10V"))
      (libsource (lib "eagle-import") (part "CC0603"))
    )
    (comp (ref "C32")
      (value "10uF")
      (footprint "eagle-import:C0603")
      (fields (field (name "SIZE") "0603") (field (name "VOLTAGE") "10V"))
      (libsource (lib "eagle-import") (part "CC0603"))
    )
    (comp (ref "C33")
      (value "10uF")
      (footprint "eagle-import:C0603")
      (fields (field (name "SIZE") "0603") (field (name "VOLTAGE") "10V"))
      (libsource (lib "eagle-import") (part "CC0603"))
    )
    (comp (ref "C34")
      (value "0.1uF")
      (footprint "eagle-import:C0402")
      (fields (field (name "SIZE") "0402") (field (name "VOLTAGE") "6.3V"))
      (libsource (lib "eagle-import") (part "CC0402"))
    )
    (comp (ref "C35")
      (value "0.1uF")
      (footprint "eagle-import:C0402")
      (fields (field (name "SIZE") "0402") (field (name "VOLTAGE") "6.3V"))
      (libsource (lib "eagle-import") (part "CC0402"))
    )
    (comp (ref "C36")
      (value "0.1uF")
      (footprint "eagle-import:C0402")
      (fields (field (name "SIZE") "0402") (field (name "VOLTAGE") "6.3V"))
      (libsource (lib "eagle-import") (part "CC0402"))
    )
    (comp (ref "C37")
      (value "10uF")
      (footprint "eagle-import:C0603")
      (fields (field (name "SIZE") "0603") (field (name "VOLTAGE") "10V"))
      (libsource (lib "eagle-import") (part "CC0603"))
    )
    (comp (ref "C38")
      (value "10uF")
      (footprint "eagle-import:C0402")
      (fields (field (name "SIZE") "0402") (field (name "SIZE_1") "0402") (field (name "VOLTAGE") "10V"))
      (libsource (lib "eagle-import") (part "CC0402"))
    )
    (comp (ref "C39")
      (value "10uF")
      (footprint "eagle-import:C0402")
      (fields (field (name "SIZE") "0402") (field (name "SIZE_1") "0402") (field (name "VOLTAGE") "10V"))
      (libsource (lib "eagle-import") (part "CC0402"))
    )
    (comp (ref "C40")
      (value "10uF")
      (footprint "eagle-import:C0402")
      (fields (field (name "SIZE") "0402") (field (name "SIZE_1") "0402") (field (name "VOLTAGE") "10V"))
      (libsource (lib "eagle-import") (part "CC0402"))
    )
    (comp (ref "C41")
      (value "2.2uF")
      (footprint "eagle-import:C0402")
      (fields (field (name "SIZE") "0402") (field (name "SIZE_1") "0402") (field (name "VOLTAGE") "10V"))
      (libsource (lib "eagle-import") (part "CC0402"))
    )
    (comp (ref "C42")
      (value "10uF")
      (footprint "eagle-import:C0402")
      (fields (field (name "SIZE") "0402") (field (name "VOLTAGE") "10V"))
      (libsource (lib "eagle-import") (part "CC0402"))
    )
    (comp (ref "C43")
      (value "10uF")
      (footprint "eagle-import:C0402")
      (fields (field (name "SIZE") "0402") (field (name "VOLTAGE") "10V"))
      (libsource (lib "eagle-import") (part "CC0402"))
    )
    (comp (ref "C44")
      (value "10uF")
      (footprint "eagle-import:C0402")
      (fields (field (name "SIZE") "0402") (field (name "VOLTAGE") "10V"))
      (libsource (lib "eagle-import") (part "CC0402"))
    )
    (comp (ref "C45")
      (value "10uF")
      (footprint "eagle-import:C0402")
      (fields (field (name "SIZE") "0402") (field (name "VOLTAGE") "10V"))
      (libsource (lib "eagle-import") (part "CC0402"))
    )
    (comp (ref "C46")
      (value "0.1uF")
      (footprint "eagle-import:C0402")
      (fields (field (name "SIZE") "0402") (field (name "VOLTAGE") "6.3V"))
      (libsource (lib "eagle-import") (part "CC0402"))
    )
    (comp (ref "C47")
      (value "47uF")
      (footprint "eagle-import:C0603")
      (fields (field (name "SIZE") "0603") (field (name "SIZE_1") "0603") (field (name "VOLTAGE") "6.3V"))
      (libsource (lib "eagle-import") (part "CC0603"))
    )
    (comp (ref "C48")
      (value "22uF")
      (footprint "eagle-import:C0402")
      (fields (field (name "SIZE") "0402") (field (name "SIZE_1") "0402") (field (name "VOLTAGE") "10V"))
      (libsource (lib "eagle-import") (part "CC0402"))
    )
    (comp (ref "C49")
      (value "47uF")
      (footprint "eagle-import:C0603")
      (fields (field (name "SIZE") "0603") (field (name "SIZE_1") "0603") (field (name "VOLTAGE") "6.3V"))
      (libsource (lib "eagle-import") (part "CC0603"))
    )
    (comp (ref "C50")
      (value "0.1uF")
      (footprint "eagle-import:C0402")
      (fields (field (name "SIZE") "0402") (field (name "VOLTAGE") "6.3V"))
      (libsource (lib "eagle-import") (part "CC0402"))
    )
    (comp (ref "C51")
      (value "10uF")
      (footprint "eagle-import:C0402")
      (fields (field (name "SIZE") "0402") (field (name "SIZE_1") "0402") (field (name "VOLTAGE") "10V"))
      (libsource (lib "eagle-import") (part "CC0402"))
    )
    (comp (ref "C52")
      (value "22uF")
      (footprint "eagle-import:C0402")
      (fields (field (name "SIZE") "0402") (field (name "SIZE_1") "0402") (field (name "VOLTAGE") "10V"))
      (libsource (lib "eagle-import") (part "CC0402"))
    )
    (comp (ref "C53")
      (value "47uF")
      (footprint "eagle-import:C0603")
      (fields (field (name "SIZE") "0603") (field (name "SIZE_1") "0603") (field (name "VOLTAGE") "6.3V"))
      (libsource (lib "eagle-import") (part "CC0603"))
    )
    (comp (ref "C54")
      (value "0.1uF")
      (footprint "eagle-import:C0402")
      (fields (field (name "SIZE") "0402") (field (name "VOLTAGE") "6.3V"))
      (libsource (lib "eagle-import") (part "CC0402"))
    )
    (comp (ref "C55")
      (value "0.1uF")
      (footprint "eagle-import:C0402")
      (fields (field (name "SIZE") "0402") (field (name "VOLTAGE") "6.3V"))
      (libsource (lib "eagle-import") (part "CC0402"))
    )
    (comp (ref "C56")
      (value "47uF")
      (footprint "eagle-import:C0805")
      (fields (field (name "SIZE") "0805") (field (name "VOLTAGE") "10V"))
      (libsource (lib "eagle-import") (part "CC0805"))
    )
    (comp (ref "C57")
      (value "10uF")
      (footprint "eagle-import:C0603")
      (fields (field (name "SIZE") "0603") (field (name "VOLTAGE") "10V"))
      (libsource (lib "eagle-import") (part "CC0603"))
    )
    (comp (ref "C58")
      (value "0.1uF")
      (footprint "eagle-import:C0402")
      (fields (field (name "SIZE") "0402") (field (name "VOLTAGE") "6.3V"))
      (libsource (lib "eagle-import") (part "CC0402"))
    )
    (comp (ref "C59")
      (value "1nF")
      (footprint "eagle-import:C0402")
      (fields (field (name "SIZE") "0402") (field (name "VOLTAGE") "6.3V"))
      (libsource (lib "eagle-import") (part "CC0402"))
    )
    (comp (ref "C60")
      (value "4.7uF")
      (footprint "eagle-import:C0402")
      (fields (field (name "SIZE") "0402") (field (name "VOLTAGE") "10V"))
      (libsource (lib "eagle-import") (part "CC0402"))
    )
    (comp (ref "C61")
      (value "0.1uF")
      (footprint "eagle-import:C0201")
      (fields (field (name "SIZE") "0201") (field (name "VOLTAGE") "6.3V"))
      (libsource (lib "eagle-import") (part "CC0201"))
    )
    (comp (ref "C62")
      (value "1uF")
      (footprint "eagle-import:C0402")
      (fields (field (name "SIZE") "0402") (field (name "VOLTAGE") "6.3V"))
      (libsource (lib "eagle-import") (part "CC0402"))
    )
    (comp (ref "C63")
      (value "1uF")
      (footprint "eagle-import:C0402")
      (fields (field (name "SIZE") "0402") (field (name "VOLTAGE") "6.3V"))
      (libsource (lib "eagle-import") (part "CC0402"))
    )
    (comp (ref "D1")
      (value "RED")
      (footprint "eagle-import:EIA-STD")
      (libsource (lib "eagle-import") (part "LTST-C191TBKTLED_EIA-STDLA"))
    )
    (comp (ref "D2")
      (value "GREEN")
      (footprint "eagle-import:EIA-STD")
      (libsource (lib "eagle-import") (part "LTST-C191TBKTLED_EIA-STDLA"))
    )
    (comp (ref "D3")
      (value "GREEN")
      (footprint "eagle-import:EIA-STD")
      (libsource (lib "eagle-import") (part "LTST-C191TBKTLED_EIA-STDLA"))
    )
    (comp (ref "D4")
      (value "GREEN")
      (footprint "eagle-import:EIA-STD")
      (libsource (lib "eagle-import") (part "LTST-C191TBKTLED_EIA-STDLA"))
    )
    (comp (ref "D5")
      (value "GREEN")
      (footprint "eagle-import:EIA-STD")
      (libsource (lib "eagle-import") (part "LTST-C191TBKTLED_EIA-STDLA"))
    )
    (comp (ref "D6")
      (value "RB520S30T1G")
      (footprint "eagle-import:RB520S30T1G")
      (libsource (lib "eagle-import") (part "RB520S30T1G"))
    )
    (comp (ref "D7")
      (value "RB520S30T1G")
      (footprint "eagle-import:RB520S30T1G")
      (libsource (lib "eagle-import") (part "RB520S30T1G"))
    )
    (comp (ref "D8")
      (value "RBS2MM40C")
      (footprint "eagle-import:SOD-123FL")
      (libsource (lib "eagle-import") (part "RBS2MM40C"))
    )
    (comp (ref "FUD1")
      (value "FIDUCIAL")
      (footprint "eagle-import:FIDUCIAL_40MIL")
      (libsource (lib "eagle-import") (part "FIDUCIAL"))
    )
    (comp (ref "FUD2")
      (value "FIDUCIAL")
      (footprint "eagle-import:FIDUCIAL_40MIL")
      (libsource (lib "eagle-import") (part "FIDUCIAL"))
    )
    (comp (ref "FUD3")
      (value "FIDUCIAL")
      (footprint "eagle-import:FIDUCIAL_40MIL")
      (libsource (lib "eagle-import") (part "FIDUCIAL"))
    )
    (comp (ref "FUD4")
      (value "FIDUCIAL")
      (footprint "eagle-import:FIDUCIAL_40MIL")
      (libsource (lib "eagle-import") (part "FIDUCIAL"))
    )
    (comp (ref "FUD5")
      (value "FIDUCIAL")
      (footprint "eagle-import:FIDUCIAL_40MIL")
      (libsource (lib "eagle-import") (part "FIDUCIAL"))
    )
    (comp (ref "FUD6")
      (value "FIDUCIAL")
      (footprint "eagle-import:FIDUCIAL_40MIL")
      (libsource (lib "eagle-import") (part "FIDUCIAL"))
    )
    (comp (ref "J1")
      (value "PINHD-1X21.27")
      (footprint "eagle-import:H1X2-1.27")
      (libsource (lib "eagle-import") (part "PINHD-1X21.27"))
    )
    (comp (ref "J2")
      (value "PINHD-1X2")
      (footprint "eagle-import:H1X2-2.54")
      (libsource (lib "eagle-import") (part "PINHD-1X2"))
    )
    (comp (ref "J4")
      (value "1-1734248-5")
      (footprint "eagle-import:TE_1-1734248-5")
      (fields (field (name "MF") "TE Connectivity"))
      (libsource (lib "eagle-import") (part "1-1734248-5"))
    )
    (comp (ref "J5")
      (value "USB4105-GF-A")
      (footprint "eagle-import:GCT_USB4105-GF-A")
      (fields (field (name "MF") "GCT"))
      (libsource (lib "eagle-import") (part "USB4105-GF-A"))
    )
    (comp (ref "J6")
      (value "2171820001")
      (footprint "eagle-import:MOLEX_2171820001")
      (fields (field (name "MF") "Molex") (field (name "MP") "217182-0001"))
      (libsource (lib "eagle-import") (part "2171820001"))
    )
    (comp (ref "J7")
      (value "PINHD-1X2")
      (footprint "eagle-import:H1X2-2.54")
      (libsource (lib "eagle-import") (part "PINHD-1X2"))
    )
    (comp (ref "J8")
      (value "505110-4091")
      (footprint "eagle-import:MOLEX_505110-4091")
      (fields (field (name "MF") "Molex") (field (name "MP") "5051104091"))
      (libsource (lib "eagle-import") (part "505110-4091"))
    )
    (comp (ref "JP1")
      (value "PINHD-1X3")
      (footprint "eagle-import:H1X3-2.54")
      (libsource (lib "eagle-import") (part "PINHD-1X3"))
    )
    (comp (ref "JP2")
      (value "PINHD-1X40")
      (footprint "eagle-import:H1X40-2.54")
      (libsource (lib "eagle-import") (part "PINHD-1X40"))
    )
    (comp (ref "JP3")
      (value "PINHD-1X40")
      (footprint "eagle-import:H1X40-2.54")
      (libsource (lib "eagle-import") (part "PINHD-1X40"))
    )
    (comp (ref "JP4")
      (value "PINHD-1X40")
      (footprint "eagle-import:H1X40-2.54")
      (libsource (lib "eagle-import") (part "PINHD-1X40"))
    )
    (comp (ref "JP5")
      (value "PINHD-1X40")
      (footprint "eagle-import:H1X40-2.54")
      (libsource (lib "eagle-import") (part "PINHD-1X40"))
    )
    (comp (ref "L1")
      (value "0.47uH")
      (footprint "eagle-import:L0806")
      (fields (field (name "SIZE") "0806") (field (name "CURRENT") "1A") (field (name "CURRENT_1") "5.2A"))
      (libsource (lib "eagle-import") (part "L0806"))
    )
    (comp (ref "L2")
      (value "0.47uH")
      (footprint "eagle-import:L0603")
      (fields (field (name "SIZE") "0603") (field (name "CURRENT") "1A") (field (name "CURRENT_1") "3A"))
      (libsource (lib "eagle-import") (part "L0603"))
    )
    (comp (ref "L3")
      (value "0.47uH")
      (footprint "eagle-import:L0603")
      (fields (field (name "SIZE") "0603") (field (name "CURRENT") "1A") (field (name "CURRENT_1") "3A"))
      (libsource (lib "eagle-import") (part "L0603"))
    )
    (comp (ref "L4")
      (value "0.47uH")
      (footprint "eagle-import:L0806")
      (fields (field (name "SIZE") "0806") (field (name "CURRENT") "1A") (field (name "CURRENT_1") "5.2A"))
      (libsource (lib "eagle-import") (part "L0806"))
    )
    (comp (ref "R1")
      (value "10k")
      (footprint "eagle-import:R0402")
      (fields (field (name "SIZE") "0402") (field (name "SIZE_1") "0402") (field (name "TOLERANCE") "5%"))
      (libsource (lib "eagle-import") (part "R-US_R0402"))
    )
    (comp (ref "R2")
      (value "100k")
      (footprint "eagle-import:R0402")
      (fields (field (name "SIZE") "0402") (field (name "SIZE_1") "0402") (field (name "TOLERANCE") "5%"))
      (libsource (lib "eagle-import") (part "R-US_R0402"))
    )
    (comp (ref "R3")
      (value "10k")
      (footprint "eagle-import:R0402")
      (fields (field (name "SIZE") "0402") (field (name "TOLERANCE") "5%"))
      (libsource (lib "eagle-import") (part "R-US_R0402"))
    )
    (comp (ref "R4")
      (value "10k")
      (footprint "eagle-import:R0402")
      (fields (field (name "SIZE") "0402") (field (name "TOLERANCE") "5%"))
      (libsource (lib "eagle-import") (part "R-US_R0402"))
    )
    (comp (ref "R5")
      (value "20k")
      (footprint "eagle-import:R0402")
      (fields (field (name "SIZE") "0402") (field (name "TOLERANCE") "5%"))
      (libsource (lib "eagle-import") (part "R-US_R0402"))
    )
    (comp (ref "R6")
      (value "100k")
      (footprint "eagle-import:R0402")
      (fields (field (name "SIZE") "0402") (field (name "TOLERANCE") "1%"))
      (libsource (lib "eagle-import") (part "R-US_R0402"))
    )
    (comp (ref "R7")
      (value "10k")
      (footprint "eagle-import:R0402")
      (fields (field (name "SIZE") "0402") (field (name "TOLERANCE") "5%"))
      (libsource (lib "eagle-import") (part "R-US_R0402"))
    )
    (comp (ref "R8")
      (value "270k")
      (footprint "eagle-import:R0402")
      (fields (field (name "SIZE") "0402") (field (name "TOLERANCE") "1%"))
      (libsource (lib "eagle-import") (part "R-US_R0402"))
    )
    (comp (ref "R9")
      (value "180k")
      (footprint "eagle-import:R0402")
      (fields (field (name "SIZE") "0402") (field (name "TOLERANCE") "1%"))
      (libsource (lib "eagle-import") (part "R-US_R0402"))
    )
    (comp (ref "R10")
      (value "10k")
      (footprint "eagle-import:R0402")
      (fields (field (name "SIZE") "0402") (field (name "TOLERANCE") "5%"))
      (libsource (lib "eagle-import") (part "R-US_R0402"))
    )
    (comp (ref "R11")
      (value "10k")
      (footprint "eagle-import:R0402")
      (fields (field (name "SIZE") "0402") (field (name "TOLERANCE") "5%"))
      (libsource (lib "eagle-import") (part "R-US_R0402"))
    )
    (comp (ref "R12")
      (value "2k")
      (footprint "eagle-import:R0402")
      (fields (field (name "SIZE") "0402") (field (name "TOLERANCE") "5%"))
      (libsource (lib "eagle-import") (part "R-US_R0402"))
    )
    (comp (ref "R13")
      (value "10k")
      (footprint "eagle-import:R0402")
      (fields (field (name "SIZE") "0402") (field (name "TOLERANCE") "5%"))
      (libsource (lib "eagle-import") (part "R-US_R0402"))
    )
    (comp (ref "R14")
      (value "10k")
      (footprint "eagle-import:R0402")
      (fields (field (name "SIZE") "0402") (field (name "TOLERANCE") "5%"))
      (libsource (lib "eagle-import") (part "R-US_R0402"))
    )
    (comp (ref "R15")
      (value "10k")
      (footprint "eagle-import:R0402")
      (fields (field (name "SIZE") "0402") (field (name "TOLERANCE") "5%"))
      (libsource (lib "eagle-import") (part "R-US_R0402"))
    )
    (comp (ref "R16")
      (value "10k")
      (footprint "eagle-import:R0402")
      (fields (field (name "SIZE") "0402") (field (name "TOLERANCE") "5%"))
      (libsource (lib "eagle-import") (part "R-US_R0402"))
    )
    (comp (ref "R17")
      (value "10k")
      (footprint "eagle-import:R0402")
      (fields (field (name "SIZE") "0402") (field (name "TOLERANCE") "5%"))
      (libsource (lib "eagle-import") (part "R-US_R0402"))
    )
    (comp (ref "R18")
      (value "10k")
      (footprint "eagle-import:R0402")
      (fields (field (name "SIZE") "0402") (field (name "TOLERANCE") "5%"))
      (libsource (lib "eagle-import") (part "R-US_R0402"))
    )
    (comp (ref "R19")
      (value "10k")
      (footprint "eagle-import:R0402")
      (fields (field (name "SIZE") "0402") (field (name "TOLERANCE") "5%"))
      (libsource (lib "eagle-import") (part "R-US_R0402"))
    )
    (comp (ref "R20")
      (value "10k")
      (footprint "eagle-import:R0402")
      (fields (field (name "SIZE") "0402") (field (name "TOLERANCE") "5%"))
      (libsource (lib "eagle-import") (part "R-US_R0402"))
    )
    (comp (ref "R21")
      (value "10k")
      (footprint "eagle-import:R0402")
      (fields (field (name "SIZE") "0402") (field (name "TOLERANCE") "5%"))
      (libsource (lib "eagle-import") (part "R-US_R0402"))
    )
    (comp (ref "R22")
      (value "10k")
      (footprint "eagle-import:R0402")
      (fields (field (name "SIZE") "0402") (field (name "TOLERANCE") "5%"))
      (libsource (lib "eagle-import") (part "R-US_R0402"))
    )
    (comp (ref "R23")
      (value "10k")
      (footprint "eagle-import:R0402")
      (fields (field (name "SIZE") "0402") (field (name "TOLERANCE") "5%"))
      (libsource (lib "eagle-import") (part "R-US_R0402"))
    )
    (comp (ref "R24")
      (value "10k")
      (footprint "eagle-import:R0402")
      (fields (field (name "SIZE") "0402") (field (name "TOLERANCE") "5%"))
      (libsource (lib "eagle-import") (part "R-US_R0402"))
    )
    (comp (ref "R25")
      (value "10k")
      (footprint "eagle-import:R0402")
      (fields (field (name "SIZE") "0402") (field (name "TOLERANCE") "5%"))
      (libsource (lib "eagle-import") (part "R-US_R0402"))
    )
    (comp (ref "R26")
      (value "10k")
      (footprint "eagle-import:R0402")
      (fields (field (name "TOLERANCE") "5%"))
      (libsource (lib "eagle-import") (part "R-US_R0402"))
    )
    (comp (ref "R27")
      (value "10k")
      (footprint "eagle-import:R0402")
      (fields (field (name "TOLERANCE") "5%"))
      (libsource (lib "eagle-import") (part "R-US_R0402"))
    )
    (comp (ref "R28")
      (value "10k")
      (footprint "eagle-import:R0402")
      (fields (field (name "TOLERANCE") "5%"))
      (libsource (lib "eagle-import") (part "R-US_R0402"))
    )
    (comp (ref "R29")
      (value "10k")
      (footprint "eagle-import:R0402")
      (fields (field (name "TOLERANCE") "5%"))
      (libsource (lib "eagle-import") (part "R-US_R0402"))
    )
    (comp (ref "R30")
      (value "10k")
      (footprint "eagle-import:R0402")
      (fields (field (name "TOLERANCE") "5%"))
      (libsource (lib "eagle-import") (part "R-US_R0402"))
    )
    (comp (ref "R31")
      (value "10k")
      (footprint "eagle-import:R0402")
      (fields (field (name "TOLERANCE") "5%"))
      (libsource (lib "eagle-import") (part "R-US_R0402"))
    )
    (comp (ref "R32")
      (value "10k")
      (footprint "eagle-import:R0402")
      (fields (field (name "TOLERANCE") "5%"))
      (libsource (lib "eagle-import") (part "R-US_R0402"))
    )
    (comp (ref "R33")
      (value "22")
      (footprint "eagle-import:R0402")
      (fields (field (name "SIZE") "0402") (field (name "SIZE_1") "0402") (field (name "TOLERANCE") "5%"))
      (libsource (lib "eagle-import") (part "R-US_R0402"))
    )
    (comp (ref "R34")
      (value "10k")
      (footprint "eagle-import:R0402")
      (fields (field (name "TOLERANCE") "5%"))
      (libsource (lib "eagle-import") (part "R-US_R0402"))
    )
    (comp (ref "R35")
      (value "5.1K")
      (footprint "eagle-import:R0402")
      (fields (field (name "SIZE") "0402") (field (name "TOLERANCE") "1%"))
      (libsource (lib "eagle-import") (part "R-US_R0402"))
    )
    (comp (ref "R36")
      (value "5.1K")
      (footprint "eagle-import:R0402")
      (fields (field (name "SIZE") "0402") (field (name "TOLERANCE") "1%"))
      (libsource (lib "eagle-import") (part "R-US_R0402"))
    )
    (comp (ref "R37")
      (value "10k")
      (footprint "eagle-import:R0402")
      (fields (field (name "TOLERANCE") "5%"))
      (libsource (lib "eagle-import") (part "R-US_R0402"))
    )
    (comp (ref "R38")
      (value "10k")
      (footprint "eagle-import:R0402")
      (fields (field (name "TOLERANCE") "5%"))
      (libsource (lib "eagle-import") (part "R-US_R0402"))
    )
    (comp (ref "R39")
      (value "10k")
      (footprint "eagle-import:R0402")
      (fields (field (name "TOLERANCE") "5%"))
      (libsource (lib "eagle-import") (part "R-US_R0402"))
    )
    (comp (ref "R40")
      (value "10k")
      (footprint "eagle-import:R0402")
      (fields (field (name "TOLERANCE") "5%"))
      (libsource (lib "eagle-import") (part "R-US_R0402"))
    )
    (comp (ref "R41")
      (value "10k")
      (footprint "eagle-import:R0402")
      (fields (field (name "TOLERANCE") "5%"))
      (libsource (lib "eagle-import") (part "R-US_R0402"))
    )
    (comp (ref "R42")
      (value "10k")
      (footprint "eagle-import:R0402")
      (fields (field (name "TOLERANCE") "5%"))
      (libsource (lib "eagle-import") (part "R-US_R0402"))
    )
    (comp (ref "R43")
      (value "10k")
      (footprint "eagle-import:R0402")
      (fields (field (name "TOLERANCE") "5%"))
      (libsource (lib "eagle-import") (part "R-US_R0402"))
    )
    (comp (ref "R44")
      (value "10k")
      (footprint "eagle-import:R0402")
      (fields (field (name "TOLERANCE") "5%"))
      (libsource (lib "eagle-import") (part "R-US_R0402"))
    )
    (comp (ref "R45")
      (value "10k")
      (footprint "eagle-import:R0402")
      (fields (field (name "TOLERANCE") "5%"))
      (libsource (lib "eagle-import") (part "R-US_R0402"))
    )
    (comp (ref "R46")
      (value "10k")
      (footprint "eagle-import:R0402")
      (fields (field (name "TOLERANCE") "5%"))
      (libsource (lib "eagle-import") (part "R-US_R0402"))
    )
    (comp (ref "R47")
      (value "10k")
      (footprint "eagle-import:R0402")
      (fields (field (name "SIZE") "0402") (field (name "SIZE_1") "0402") (field (name "TOLERANCE") "5%"))
      (libsource (lib "eagle-import") (part "R-US_R0402"))
    )
    (comp (ref "R48")
      (value "10k")
      (footprint "eagle-import:R0402")
      (fields (field (name "SIZE") "0402") (field (name "SIZE_1") "0402") (field (name "TOLERANCE") "5%"))
      (libsource (lib "eagle-import") (part "R-US_R0402"))
    )
    (comp (ref "R49")
      (value "10k")
      (footprint "eagle-import:R0402")
      (fields (field (name "TOLERANCE") "5%"))
      (libsource (lib "eagle-import") (part "R-US_R0402"))
    )
    (comp (ref "R50")
      (value "10k")
      (footprint "eagle-import:R0402")
      (fields (field (name "SIZE") "0402") (field (name "TOLERANCE") "5%"))
      (libsource (lib "eagle-import") (part "R-US_R0402"))
    )
    (comp (ref "R51")
      (value "10k")
      (footprint "eagle-import:R0402")
      (fields (field (name "TOLERANCE") "5%"))
      (libsource (lib "eagle-import") (part "R-US_R0402"))
    )
    (comp (ref "R52")
      (value "4.7k")
      (footprint "eagle-import:R0402")
      (fields (field (name "SIZE") "0402") (field (name "TOLERANCE") "5%"))
      (libsource (lib "eagle-import") (part "R-US_R0402"))
    )
    (comp (ref "R53")
      (value "4.7k")
      (footprint "eagle-import:R0402")
      (fields (field (name "SIZE") "0402") (field (name "TOLERANCE") "5%"))
      (libsource (lib "eagle-import") (part "R-US_R0402"))
    )
    (comp (ref "R54")
      (value "10k")
      (footprint "eagle-import:R0402")
      (fields (field (name "SIZE") "0402") (field (name "TOLERANCE") "5%"))
      (libsource (lib "eagle-import") (part "R-US_R0402"))
    )
    (comp (ref "R55")
      (value "0")
      (footprint "eagle-import:R0402")
      (fields (field (name "SIZE") "0402") (field (name "SIZE_1") "0402") (field (name "TOLERANCE") "5%"))
      (libsource (lib "eagle-import") (part "R-US_R0402"))
    )
    (comp (ref "R56")
      (value "0")
      (footprint "eagle-import:R0402")
      (fields (field (name "SIZE") "0402") (field (name "TOLERANCE") "5%"))
      (libsource (lib "eagle-import") (part "R-US_R0402"))
    )
    (comp (ref "R57")
      (value "1k")
      (footprint "eagle-import:R0402")
      (fields (field (name "SIZE") "0402") (field (name "TOLERANCE") "5%"))
      (libsource (lib "eagle-import") (part "R-US_R0402"))
    )
    (comp (ref "R58")
      (value "1k")
      (footprint "eagle-import:R0402")
      (fields (field (name "SIZE") "0402") (field (name "TOLERANCE") "5%"))
      (libsource (lib "eagle-import") (part "R-US_R0402"))
    )
    (comp (ref "R59")
      (value "1k")
      (footprint "eagle-import:R0402")
      (fields (field (name "SIZE") "0402") (field (name "TOLERANCE") "5%"))
      (libsource (lib "eagle-import") (part "R-US_R0402"))
    )
    (comp (ref "R60")
      (value "1k")
      (footprint "eagle-import:R0402")
      (fields (field (name "SIZE") "0402") (field (name "TOLERANCE") "5%"))
      (libsource (lib "eagle-import") (part "R-US_R0402"))
    )
    (comp (ref "R61")
      (value "1k")
      (footprint "eagle-import:R0402")
      (fields (field (name "SIZE") "0402") (field (name "TOLERANCE") "5%"))
      (libsource (lib "eagle-import") (part "R-US_R0402"))
    )
    (comp (ref "R62")
      (value "20k")
      (footprint "eagle-import:R0402")
      (fields (field (name "SIZE") "0402") (field (name "TOLERANCE") "5%"))
      (libsource (lib "eagle-import") (part "R-US_R0402"))
    )
    (comp (ref "R63")
      (value "10k")
      (footprint "eagle-import:R0402")
      (fields (field (name "SIZE") "0402") (field (name "TOLERANCE") "5%"))
      (libsource (lib "eagle-import") (part "R-US_R0402"))
    )
    (comp (ref "R64")
      (value "2k")
      (footprint "eagle-import:R0402")
      (fields (field (name "SIZE") "0402") (field (name "TOLERANCE") "5%"))
      (libsource (lib "eagle-import") (part "R-US_R0402"))
    )
    (comp (ref "R65")
      (value "2k")
      (footprint "eagle-import:R0402")
      (fields (field (name "SIZE") "0402") (field (name "TOLERANCE") "5%"))
      (libsource (lib "eagle-import") (part "R-US_R0402"))
    )
    (comp (ref "R66")
      (value "2k")
      (footprint "eagle-import:R0402")
      (fields (field (name "SIZE") "0402") (field (name "TOLERANCE") "5%"))
      (libsource (lib "eagle-import") (part "R-US_R0402"))
    )
    (comp (ref "R67")
      (value "DNP")
      (footprint "eagle-import:R0402")
      (fields (field (name "SIZE") "0402") (field (name "TOLERANCE") "5%"))
      (libsource (lib "eagle-import") (part "R-US_R0402"))
    )
    (comp (ref "R68")
      (value "DNP")
      (footprint "eagle-import:R0402")
      (fields (field (name "SIZE") "0402") (field (name "TOLERANCE") "5%"))
      (libsource (lib "eagle-import") (part "R-US_R0402"))
    )
    (comp (ref "R69")
      (value "DNP")
      (footprint "eagle-import:R0402")
      (fields (field (name "SIZE") "0402") (field (name "TOLERANCE") "5%"))
      (libsource (lib "eagle-import") (part "R-US_R0402"))
    )
    (comp (ref "R70")
      (value "DNP")
      (footprint "eagle-import:R0402")
      (fields (field (name "SIZE") "0402") (field (name "TOLERANCE") "5%"))
      (libsource (lib "eagle-import") (part "R-US_R0402"))
    )
    (comp (ref "R71")
      (value "56K")
      (footprint "eagle-import:R0402")
      (fields (field (name "SIZE") "0402") (field (name "TOLERANCE") "5%"))
      (libsource (lib "eagle-import") (part "R-US_R0402"))
    )
    (comp (ref "R72")
      (value "56K")
      (footprint "eagle-import:R0402")
      (fields (field (name "SIZE") "0402") (field (name "TOLERANCE") "5%"))
      (libsource (lib "eagle-import") (part "R-US_R0402"))
    )
    (comp (ref "R73")
      (value "10k")
      (footprint "eagle-import:R0402")
      (fields (field (name "SIZE") "0402") (field (name "TOLERANCE") "5%"))
      (libsource (lib "eagle-import") (part "R-US_R0402"))
    )
    (comp (ref "R74")
      (value "0")
      (footprint "eagle-import:R0402")
      (fields (field (name "SIZE") "0402") (field (name "TOLERANCE") "5%"))
      (libsource (lib "eagle-import") (part "R-US_R0402"))
    )
    (comp (ref "R76")
      (value "10k")
      (footprint "eagle-import:R0402")
      (fields (field (name "SIZE") "0402") (field (name "TOLERANCE") "5%"))
      (libsource (lib "eagle-import") (part "R-US_R0402"))
    )
    (comp (ref "S1")
      (value "MF-SW-TACT-4.2MM")
      (footprint "eagle-import:TACT4.2MM")
      (fields (field (name "HOUSEPART") "YES"))
      (libsource (lib "eagle-import") (part "TACT_4.2MM"))
    )
    (comp (ref "TC1")
      (value "TC2050-IDC-NL")
      (footprint "eagle-import:TC2050-IDC-NL")
      (libsource (lib "eagle-import") (part "TC2050-IDC-NL"))
    )
    (comp (ref "TP1")
      (value "TPB0,65")
      (footprint "eagle-import:TP_B0,65")
      (libsource (lib "eagle-import") (part "TPB0,65"))
    )
    (comp (ref "TP2")
      (value "TPB0,65")
      (footprint "eagle-import:TP_B0,65")
      (libsource (lib "eagle-import") (part "TPB0,65"))
    )
    (comp (ref "TP3")
      (value "TPB0,65")
      (footprint "eagle-import:TP_B0,65")
      (libsource (lib "eagle-import") (part "TPB0,65"))
    )
    (comp (ref "TP6")
      (value "TPB0,65")
      (footprint "eagle-import:TP_B0,65")
      (libsource (lib "eagle-import") (part "TPB0,65"))
    )
    (comp (ref "TP7")
      (value "TPB0,65")
      (footprint "eagle-import:TP_B0,65")
      (libsource (lib "eagle-import") (part "TPB0,65"))
    )
    (comp (ref "U1")
      (value "OSD6254-1G-IPM")
      (footprint "eagle-import:OSD6254-BGA-500")
      (libsource (lib "eagle-import") (part "OSD6254-1G-IPM"))
    )
    (comp (ref "U2")
      (value "TPD4S012_DRY_6_P1_P")
      (footprint "eagle-import:DRY6")
      (libsource (lib "eagle-import") (part "TPD4S012_DRY_6_P1_P"))
    )
    (comp (ref "U3")
      (value "TLV62595DMQR")
      (footprint "eagle-import:DMQ0006A")
      (libsource (lib "eagle-import") (part "TLV62595DMQR"))
    )
    (comp (ref "U4")
      (value "24AA32AT-I/OT")
      (footprint "eagle-import:SOT95P280X145-5N")
      (libsource (lib "eagle-import") (part "24AA32AT-I/OT"))
    )
    (comp (ref "U5")
      (value "TPS22965DSGT")
      (footprint "eagle-import:SON50P200X200X80-9N")
      (fields (field (name "MF") "Texas Instruments"))
      (libsource (lib "eagle-import") (part "TPS22965DSGT"))
    )
    (comp (ref "U6")
      (value "TPS6521903RHB")
      (footprint "eagle-import:RHB0032W")
      (libsource (lib "eagle-import") (part "TPS65219-5X5"))
    )
    (comp (ref "U7")
      (value "ADC121C027CIMK")
      (footprint "eagle-import:SOT95P280X110-6N")
      (fields (field (name "MF") "Texas Instruments") (field (name "MP") "ADC121C027CIMK/NOPB"))
      (libsource (lib "eagle-import") (part "ADC121C027CIMK"))
    )
    (comp (ref "U8")
      (value "ADC121C027CIMK")
      (footprint "eagle-import:SOT95P280X110-6N")
      (fields (field (name "MF") "Texas Instruments") (field (name "MP") "ADC121C027CIMK/NOPB"))
      (libsource (lib "eagle-import") (part "ADC121C027CIMK"))
    )
    (comp (ref "U9")
      (value "TPD4S012_DRY_6_P1_P")
      (footprint "eagle-import:DRY6")
      (libsource (lib "eagle-import") (part "TPD4S012_DRY_6_P1_P"))
    )
    (comp (ref "U10")
      (value "TPS22918DBVR")
      (footprint "eagle-import:SOT95P280X145-6N")
      (fields (field (name "MF") "Texas Instruments"))
      (libsource (lib "eagle-import") (part "TPS22918DBVR"))
    )
    (comp (ref "U11")
      (value "SN74LVC1G04DSFR")
      (footprint "eagle-import:SON35P100X100X40-6N")
      (fields (field (name "MF") "Texas Instruments"))
      (libsource (lib "eagle-import") (part "SN74LVC1G04DSFR"))
    )
    (comp (ref "U12")
      (value "SN74LVC2G241YZPR")
      (footprint "eagle-import:YZP0008")
      (libsource (lib "eagle-import") (part "SN74LVC2G241YZPR"))
    )
    (comp (ref "U13")
      (value "SN74LVC2G241YZPR")
      (footprint "eagle-import:YZP0008")
      (libsource (lib "eagle-import") (part "SN74LVC2G241YZPR"))
    )
    (comp (ref "U14")
      (value "TLV75518PDQNR")
      (footprint "eagle-import:DQN0004A")
      (libsource (lib "eagle-import") (part "TLV75518PDQNR"))
    )
    (comp (ref "X1")
      (value "MF-MICROSD")
      (footprint "eagle-import:MF-MICROSD")
      (fields (field (name "HOUSEPART") "YES"))
      (libsource (lib "eagle-import") (part "SD_CARD_SLOT_MICRO_RIGHT"))
    )
    (comp (ref "Y1")
      (value "SIT1533AI-H4-D14-32.768")
      (footprint "eagle-import:SIT1533AI_2X1.2MM")
      (libsource (lib "eagle-import") (part "SIT1533AI-H4-D14-32.768"))
    )
    (comp (ref "Y2")
      (value "SIT8008BI-73-YYS-25.000000")
      (footprint "eagle-import:QFN-4-2X1.6MM")
      (libsource (lib "eagle-import") (part "SIT8008BI-73-YYS-25.000000"))
    )
  )
  (nets
    (net (code "1") (name "/BUCK1-0P75") (class "Default")
      (node (ref "C10") (pin "1") (pinfunction "1_1") (pintype "passive"))
      (node (ref "C11") (pin "1") (pinfunction "1_1") (pintype "passive"))
      (node (ref "C12") (pin "1") (pinfunction "1_1") (pintype "passive"))
      (node (ref "C13") (pin "1") (pinfunction "1_1") (pintype "passive"))
      (node (ref "C14") (pin "1") (pinfunction "1_1") (pintype "passive"))
      (node (ref "C15") (pin "1") (pinfunction "1_1") (pintype "passive"))
      (node (ref "C16") (pin "1") (pinfunction "1_1") (pintype "passive"))
      (node (ref "C53") (pin "1") (pinfunction "1_1") (pintype "passive"))
      (node (ref "L4") (pin "2") (pinfunction "2_2") (pintype "passive"))
      (node (ref "U1") (pin "G12") (pinfunction "VDD_CANUART_G12") (pintype "bidirectional"))
      (node (ref "U1") (pin "G13") (pinfunction "VDD_CORE_G13") (pintype "bidirectional"))
      (node (ref "U1") (pin "G14") (pinfunction "VDD_CORE_G14") (pintype "bidirectional"))
      (node (ref "U1") (pin "G15") (pinfunction "VDD_CORE_G15") (pintype "bidirectional"))
      (node (ref "U1") (pin "G16") (pinfunction "VDD_CORE_G16") (pintype "bidirectional"))
      (node (ref "U1") (pin "H12") (pinfunction "VDD_CORE_H12") (pintype "bidirectional"))
      (node (ref "U1") (pin "H13") (pinfunction "VDD_CORE_H13") (pintype "bidirectional"))
      (node (ref "U1") (pin "H14") (pinfunction "VDD_CORE_H14") (pintype "bidirectional"))
      (node (ref "U1") (pin "H15") (pinfunction "VDD_CORE_H15") (pintype "bidirectional"))
      (node (ref "U1") (pin "H16") (pinfunction "VDD_CORE_H16") (pintype "bidirectional"))
      (node (ref "U1") (pin "J12") (pinfunction "VDD_CORE_J12") (pintype "bidirectional"))
      (node (ref "U1") (pin "J13") (pinfunction "VDD_CORE_J13") (pintype "bidirectional"))
      (node (ref "U1") (pin "J16") (pinfunction "VDD_CORE_J16") (pintype "bidirectional"))
      (node (ref "U1") (pin "K12") (pinfunction "VDD_CORE_K12") (pintype "bidirectional"))
      (node (ref "U1") (pin "K13") (pinfunction "VDD_CORE_K13") (pintype "bidirectional"))
      (node (ref "U1") (pin "K16") (pinfunction "VDD_CORE_K16") (pintype "bidirectional"))
      (node (ref "U1") (pin "L13") (pinfunction "VDD_CORE_L13") (pintype "bidirectional"))
      (node (ref "U1") (pin "L14") (pinfunction "VDD_CORE_L14") (pintype "bidirectional"))
      (node (ref "U1") (pin "L15") (pinfunction "VDD_CORE_L15") (pintype "bidirectional"))
      (node (ref "U1") (pin "M12") (pinfunction "VDDA_CORE_USB_M12") (pintype "bidirectional"))
      (node (ref "U1") (pin "M13") (pinfunction "VDDA_CORE_CSIRX0_M13") (pintype "bidirectional"))
      (node (ref "U6") (pin "1") (pinfunction "FB_B1_1") (pintype "bidirectional"))
    )
    (net (code "2") (name "/BUCK2-1P8") (class "Default")
      (node (ref "C21") (pin "1") (pinfunction "1_1") (pintype "passive"))
      (node (ref "C38") (pin "1") (pinfunction "1_1") (pintype "passive"))
      (node (ref "C49") (pin "1") (pinfunction "1_1") (pintype "passive"))
      (node (ref "L3") (pin "2") (pinfunction "2_2") (pintype "passive"))
      (node (ref "U1") (pin "C15") (pinfunction "VMON_1P8_SOC_C15") (pintype "bidirectional"))
      (node (ref "U6") (pin "20") (pinfunction "PVIN_LDO2_20") (pintype "bidirectional"))
      (node (ref "U6") (pin "32") (pinfunction "FB_B2_32") (pintype "bidirectional"))
    )
    (net (code "3") (name "/BUCK3-1P2") (class "Default")
      (node (ref "C47") (pin "1") (pinfunction "1_1") (pintype "passive"))
      (node (ref "C7") (pin "1") (pinfunction "1_1") (pintype "passive"))
      (node (ref "C8") (pin "1") (pinfunction "1_1") (pintype "passive"))
      (node (ref "C9") (pin "1") (pinfunction "1_1") (pintype "passive"))
      (node (ref "L2") (pin "2") (pinfunction "2_2") (pintype "passive"))
      (node (ref "U1") (pin "K10") (pinfunction "VDDS_DDR_K10") (pintype "bidirectional"))
      (node (ref "U1") (pin "K11") (pinfunction "VDDS_DDR_K11") (pintype "bidirectional"))
      (node (ref "U1") (pin "L10") (pinfunction "VDDS_DDR_L10") (pintype "bidirectional"))
      (node (ref "U1") (pin "L11") (pinfunction "VDDS_DDR_L11") (pintype "bidirectional"))
      (node (ref "U1") (pin "L9") (pinfunction "VDDS_DDR_L9") (pintype "bidirectional"))
      (node (ref "U1") (pin "M10") (pinfunction "VDDS_DDR_M10") (pintype "bidirectional"))
      (node (ref "U1") (pin "M8") (pinfunction "VDDS_DDR_M8") (pintype "bidirectional"))
      (node (ref "U1") (pin "M9") (pinfunction "VDDS_DDR_M9") (pintype "bidirectional"))
      (node (ref "U1") (pin "N8") (pinfunction "VDDS_DDR_N8") (pintype "bidirectional"))
      (node (ref "U1") (pin "N9") (pinfunction "VDDS_DDR_N9") (pintype "bidirectional"))
      (node (ref "U6") (pin "24") (pinfunction "FB_B3_24") (pintype "bidirectional"))
    )
    (net (code "4") (name "/CH1_LVDS_A0N") (class "Default")
      (node (ref "J8") (pin "11") (pinfunction "11_11") (pintype "bidirectional"))
      (node (ref "U1") (pin "P2") (pinfunction "OLDI0_A0N_P2") (pintype "bidirectional"))
    )
    (net (code "5") (name "/CH1_LVDS_A0P") (class "Default")
      (node (ref "J8") (pin "12") (pinfunction "12_12") (pintype "bidirectional"))
      (node (ref "U1") (pin "R1") (pinfunction "OLDI0_A0P_R1") (pintype "bidirectional"))
    )
    (net (code "6") (name "/CH1_LVDS_A1N") (class "Default")
      (node (ref "J8") (pin "14") (pinfunction "14_14") (pintype "bidirectional"))
      (node (ref "U1") (pin "R2") (pinfunction "OLDI0_A1N_R2") (pintype "bidirectional"))
    )
    (net (code "7") (name "/CH1_LVDS_A1P") (class "Default")
      (node (ref "J8") (pin "15") (pinfunction "15_15") (pintype "bidirectional"))
      (node (ref "U1") (pin "T1") (pinfunction "OLDI0_A1P_T1") (pintype "bidirectional"))
    )
    (net (code "8") (name "/CH1_LVDS_A2N") (class "Default")
      (node (ref "J8") (pin "20") (pinfunction "20_20") (pintype "bidirectional"))
      (node (ref "U1") (pin "T2") (pinfunction "OLDI0_A2N_T2") (pintype "bidirectional"))
    )
    (net (code "9") (name "/CH1_LVDS_A2P") (class "Default")
      (node (ref "J8") (pin "21") (pinfunction "21_21") (pintype "bidirectional"))
      (node (ref "U1") (pin "U2") (pinfunction "OLDI0_A2P_U2") (pintype "bidirectional"))
    )
    (net (code "10") (name "/CH1_LVDS_A3N") (class "Default")
      (node (ref "J8") (pin "23") (pinfunction "23_23") (pintype "bidirectional"))
      (node (ref "U1") (pin "U3") (pinfunction "OLDI0_A3N_U3") (pintype "bidirectional"))
    )
    (net (code "11") (name "/CH1_LVDS_A3P") (class "Default")
      (node (ref "J8") (pin "24") (pinfunction "24_24") (pintype "bidirectional"))
      (node (ref "U1") (pin "V3") (pinfunction "OLDI0_A3P_V3") (pintype "bidirectional"))
    )
    (net (code "12") (name "/CH1_LVDS_CLKN") (class "Default")
      (node (ref "J8") (pin "17") (pinfunction "17_17") (pintype "bidirectional"))
      (node (ref "U1") (pin "U8") (pinfunction "OLDI0_CLK0N_U8") (pintype "bidirectional"))
    )
    (net (code "13") (name "/CH1_LVDS_CLKP") (class "Default")
      (node (ref "J8") (pin "18") (pinfunction "18_18") (pintype "bidirectional"))
      (node (ref "U1") (pin "V8") (pinfunction "OLDI0_CLK0P_V8") (pintype "bidirectional"))
    )
    (net (code "14") (name "/CH2_LVDS_A0N") (class "Default")
      (node (ref "J8") (pin "26") (pinfunction "26_26") (pintype "bidirectional"))
      (node (ref "U1") (pin "U4") (pinfunction "OLDI0_A4N_U4") (pintype "bidirectional"))
    )
    (net (code "15") (name "/CH2_LVDS_A0P") (class "Default")
      (node (ref "J8") (pin "27") (pinfunction "27_27") (pintype "bidirectional"))
      (node (ref "U1") (pin "V4") (pinfunction "OLDI0_A4P_V4") (pintype "bidirectional"))
    )
    (net (code "16") (name "/CH2_LVDS_A1N") (class "Default")
      (node (ref "J8") (pin "29") (pinfunction "29_29") (pintype "bidirectional"))
      (node (ref "U1") (pin "U5") (pinfunction "OLDI0_A5N_U5") (pintype "bidirectional"))
    )
    (net (code "17") (name "/CH2_LVDS_A1P") (class "Default")
      (node (ref "J8") (pin "30") (pinfunction "30_30") (pintype "bidirectional"))
      (node (ref "U1") (pin "V5") (pinfunction "OLDI0_A5P_V5") (pintype "bidirectional"))
    )
    (net (code "18") (name "/CH2_LVDS_A2N") (class "Default")
      (node (ref "J8") (pin "35") (pinfunction "35_35") (pintype "bidirectional"))
      (node (ref "U1") (pin "U6") (pinfunction "OLDI0_A6N_U6") (pintype "bidirectional"))
    )
    (net (code "19") (name "/CH2_LVDS_A2P") (class "Default")
      (node (ref "J8") (pin "36") (pinfunction "36_36") (pintype "bidirectional"))
      (node (ref "U1") (pin "V6") (pinfunction "OLDI0_A6P_V6") (pintype "bidirectional"))
    )
    (net (code "20") (name "/CH2_LVDS_A3N") (class "Default")
      (node (ref "J8") (pin "38") (pinfunction "38_38") (pintype "bidirectional"))
      (node (ref "U1") (pin "U7") (pinfunction "OLDI0_A7N_U7") (pintype "bidirectional"))
    )
    (net (code "21") (name "/CH2_LVDS_A3P") (class "Default")
      (node (ref "J8") (pin "39") (pinfunction "39_39") (pintype "bidirectional"))
      (node (ref "U1") (pin "V7") (pinfunction "OLDI0_A7P_V7") (pintype "bidirectional"))
    )
    (net (code "22") (name "/CH2_LVDS_CLKN") (class "Default")
      (node (ref "J8") (pin "32") (pinfunction "32_32") (pintype "bidirectional"))
      (node (ref "U1") (pin "U9") (pinfunction "OLDI0_CLK1N_U9") (pintype "bidirectional"))
    )
    (net (code "23") (name "/CH2_LVDS_CLKP") (class "Default")
      (node (ref "J8") (pin "33") (pinfunction "33_33") (pintype "bidirectional"))
      (node (ref "U1") (pin "V9") (pinfunction "OLDI0_CLK1P_V9") (pintype "bidirectional"))
    )
    (net (code "24") (name "/CLICK0_AN") (class "Default")
      (node (ref "JP3") (pin "1") (pinfunction "1_1") (pintype "passive"))
      (node (ref "R56") (pin "2") (pinfunction "2_2") (pintype "passive"))
      (node (ref "U7") (pin "3") (pinfunction "VIN_3") (pintype "input"))
    )
    (net (code "25") (name "/CLICK1_AN") (class "Default")
      (node (ref "JP4") (pin "40") (pinfunction "40_40") (pintype "passive"))
      (node (ref "R55") (pin "2") (pinfunction "2_2") (pintype "passive"))
      (node (ref "U8") (pin "3") (pinfunction "VIN_3") (pintype "input"))
    )
    (net (code "26") (name "/CSI0_RXCLKN") (class "Default")
      (node (ref "J4") (pin "8") (pinfunction "8_8") (pintype "passive"))
      (node (ref "U1") (pin "V17") (pinfunction "CSI0_RXCLKN_V17") (pintype "bidirectional"))
    )
    (net (code "27") (name "/CSI0_RXCLKP") (class "Default")
      (node (ref "J4") (pin "9") (pinfunction "9_9") (pintype "passive"))
      (node (ref "U1") (pin "U17") (pinfunction "CSI0_RXCLKP_U17") (pintype "bidirectional"))
    )
    (net (code "28") (name "/CSI0_RXN0") (class "Default")
      (node (ref "J4") (pin "2") (pinfunction "2_2") (pintype "passive"))
      (node (ref "U1") (pin "V16") (pinfunction "CSI0_RXN0_V16") (pintype "bidirectional"))
    )
    (net (code "29") (name "/CSI0_RXN1") (class "Default")
      (node (ref "J4") (pin "5") (pinfunction "5_5") (pintype "passive"))
      (node (ref "U1") (pin "V15") (pinfunction "CSI0_RXN1_V15") (pintype "bidirectional"))
    )
    (net (code "30") (name "/CSI0_RXP0") (class "Default")
      (node (ref "J4") (pin "3") (pinfunction "3_3") (pintype "passive"))
      (node (ref "U1") (pin "U16") (pinfunction "CSI0_RXP0_U16") (pintype "bidirectional"))
    )
    (net (code "31") (name "/CSI0_RXP1") (class "Default")
      (node (ref "J4") (pin "6") (pinfunction "6_6") (pintype "passive"))
      (node (ref "U1") (pin "U15") (pinfunction "CSI0_RXP1_U15") (pintype "bidirectional"))
    )
    (net (code "32") (name "/EEPROM_WP") (class "Default")
      (node (ref "J2") (pin "2") (pinfunction "2_2") (pintype "bidirectional"))
      (node (ref "R7") (pin "1") (pinfunction "1_1") (pintype "passive"))
      (node (ref "U4") (pin "5") (pinfunction "WP_5") (pintype "bidirectional"))
    )
    (net (code "33") (name "/EMU0") (class "Default")
      (node (ref "R20") (pin "1") (pinfunction "1_1") (pintype "passive"))
      (node (ref "TC1") (pin "7") (pinfunction "7_7") (pintype "passive"))
      (node (ref "U1") (pin "D8") (pinfunction "EMU0_D8") (pintype "bidirectional"))
    )
    (net (code "34") (name "/EMU1") (class "Default")
      (node (ref "R21") (pin "1") (pinfunction "1_1") (pintype "passive"))
      (node (ref "TC1") (pin "10") (pinfunction "10_10") (pintype "passive"))
      (node (ref "U1") (pin "C8") (pinfunction "EMU1_C8") (pintype "bidirectional"))
    )
    (net (code "35") (name "/EXTINTN") (class "Default")
      (node (ref "R25") (pin "1") (pinfunction "1_1") (pintype "passive"))
      (node (ref "U1") (pin "C17") (pinfunction "EXTINTN_C17") (pintype "bidirectional"))
      (node (ref "U6") (pin "11") (pinfunction "NINT_11") (pintype "bidirectional"))
    )
    (net (code "36") (name "/EXT_REFCLK1") (class "Default")
      (node (ref "R56") (pin "1") (pinfunction "1_1") (pintype "passive"))
      (node (ref "U1") (pin "D16") (pinfunction "EXT_REFCLK1_D16") (pintype "bidirectional"))
    )
    (net (code "37") (name "/GPMC0_AD0") (class "Default")
      (node (ref "JP5") (pin "39") (pinfunction "39_39") (pintype "passive"))
      (node (ref "R51") (pin "1") (pinfunction "1_1") (pintype "passive"))
      (node (ref "U1") (pin "G28") (pinfunction "GPMC0_AD0_G28") (pintype "bidirectional"))
    )
    (net (code "38") (name "/GPMC0_AD1") (class "Default")
      (node (ref "JP5") (pin "38") (pinfunction "38_38") (pintype "passive"))
      (node (ref "R49") (pin "1") (pinfunction "1_1") (pintype "passive"))
      (node (ref "U1") (pin "G27") (pinfunction "GPMC0_AD1_G27") (pintype "bidirectional"))
    )
    (net (code "39") (name "/GPMC0_AD2") (class "Default")
      (node (ref "JP5") (pin "37") (pinfunction "37_37") (pintype "passive"))
      (node (ref "R42") (pin "1") (pinfunction "1_1") (pintype "passive"))
      (node (ref "U1") (pin "F28") (pinfunction "GPMC0_AD2_F28") (pintype "bidirectional"))
    )
    (net (code "40") (name "/GPMC0_AD3") (class "Default")
      (node (ref "JP5") (pin "36") (pinfunction "36_36") (pintype "passive"))
      (node (ref "R41") (pin "1") (pinfunction "1_1") (pintype "passive"))
      (node (ref "U1") (pin "F27") (pinfunction "GPMC0_AD3_F27") (pintype "bidirectional"))
    )
    (net (code "41") (name "/GPMC0_AD4") (class "Default")
      (node (ref "JP5") (pin "35") (pinfunction "35_35") (pintype "passive"))
      (node (ref "R40") (pin "1") (pinfunction "1_1") (pintype "passive"))
      (node (ref "U1") (pin "E28") (pinfunction "GPMC0_AD4_E28") (pintype "bidirectional"))
    )
    (net (code "42") (name "/GPMC0_AD5") (class "Default")
      (node (ref "JP5") (pin "34") (pinfunction "34_34") (pintype "passive"))
      (node (ref "R39") (pin "1") (pinfunction "1_1") (pintype "passive"))
      (node (ref "U1") (pin "E27") (pinfunction "GPMC0_AD5_E27") (pintype "bidirectional"))
    )
    (net (code "43") (name "/GPMC0_AD6") (class "Default")
      (node (ref "JP5") (pin "33") (pinfunction "33_33") (pintype "passive"))
      (node (ref "R38") (pin "1") (pinfunction "1_1") (pintype "passive"))
      (node (ref "U1") (pin "D28") (pinfunction "GPMC0_AD6_D28") (pintype "bidirectional"))
    )
    (net (code "44") (name "/GPMC0_AD7") (class "Default")
      (node (ref "JP5") (pin "32") (pinfunction "32_32") (pintype "passive"))
      (node (ref "R37") (pin "1") (pinfunction "1_1") (pintype "passive"))
      (node (ref "U1") (pin "D27") (pinfunction "GPMC0_AD7_D27") (pintype "bidirectional"))
    )
    (net (code "45") (name "/GPMC0_AD8") (class "Default")
      (node (ref "JP2") (pin "29") (pinfunction "29_29") (pintype "passive"))
      (node (ref "R34") (pin "1") (pinfunction "1_1") (pintype "passive"))
      (node (ref "U1") (pin "L27") (pinfunction "GPMC0_AD8_L27") (pintype "bidirectional"))
    )
    (net (code "46") (name "/GPMC0_AD9") (class "Default")
      (node (ref "JP3") (pin "29") (pinfunction "29_29") (pintype "passive"))
      (node (ref "R32") (pin "1") (pinfunction "1_1") (pintype "passive"))
      (node (ref "U1") (pin "L28") (pinfunction "GPMC0_AD9_L28") (pintype "bidirectional"))
    )
    (net (code "47") (name "/GPMC0_AD10") (class "Default")
      (node (ref "JP2") (pin "30") (pinfunction "30_30") (pintype "passive"))
      (node (ref "R31") (pin "1") (pinfunction "1_1") (pintype "passive"))
      (node (ref "U1") (pin "K27") (pinfunction "GPMC0_AD10_K27") (pintype "bidirectional"))
    )
    (net (code "48") (name "/GPMC0_AD11") (class "Default")
      (node (ref "JP3") (pin "30") (pinfunction "30_30") (pintype "passive"))
      (node (ref "R30") (pin "1") (pinfunction "1_1") (pintype "passive"))
      (node (ref "U1") (pin "K28") (pinfunction "GPMC0_AD11_K28") (pintype "bidirectional"))
    )
    (net (code "49") (name "/GPMC0_AD12") (class "Default")
      (node (ref "JP2") (pin "31") (pinfunction "31_31") (pintype "passive"))
      (node (ref "R29") (pin "1") (pinfunction "1_1") (pintype "passive"))
      (node (ref "U1") (pin "J28") (pinfunction "GPMC0_AD12_J28") (pintype "bidirectional"))
    )
    (net (code "50") (name "/GPMC0_AD13") (class "Default")
      (node (ref "JP3") (pin "31") (pinfunction "31_31") (pintype "passive"))
      (node (ref "R28") (pin "1") (pinfunction "1_1") (pintype "passive"))
      (node (ref "U1") (pin "J27") (pinfunction "GPMC0_AD13_J27") (pintype "bidirectional"))
    )
    (net (code "51") (name "/GPMC0_AD14") (class "Default")
      (node (ref "JP2") (pin "32") (pinfunction "32_32") (pintype "passive"))
      (node (ref "R27") (pin "1") (pinfunction "1_1") (pintype "passive"))
      (node (ref "U1") (pin "H28") (pinfunction "GPMC0_AD14_H28") (pintype "bidirectional"))
    )
    (net (code "52") (name "/GPMC0_AD15") (class "Default")
      (node (ref "JP3") (pin "32") (pinfunction "32_32") (pintype "passive"))
      (node (ref "R26") (pin "1") (pinfunction "1_1") (pintype "passive"))
      (node (ref "U1") (pin "H27") (pinfunction "GPMC0_AD15_H27") (pintype "bidirectional"))
    )
    (net (code "53") (name "/GPMC0_ADVN_ALE") (class "Default")
      (node (ref "JP4") (pin "31") (pinfunction "31_31") (pintype "passive"))
      (node (ref "U1") (pin "H25") (pinfunction "GPMC0_ADVN_ALE_H25") (pintype "bidirectional"))
    )
    (net (code "54") (name "/GPMC0_BE0N_CLE") (class "Default")
      (node (ref "JP2") (pin "38") (pinfunction "38_38") (pintype "passive"))
      (node (ref "U1") (pin "J26") (pinfunction "GPMC0_BE0N_CLE_J26") (pintype "bidirectional"))
    )
    (net (code "55") (name "/GPMC0_BE1N") (class "Default")
      (node (ref "JP2") (pin "36") (pinfunction "36_36") (pintype "passive"))
      (node (ref "U1") (pin "K25") (pinfunction "GPMC0_BE1N_K25") (pintype "bidirectional"))
    )
    (net (code "56") (name "/GPMC0_CLK") (class "Default")
      (node (ref "JP2") (pin "37") (pinfunction "37_37") (pintype "passive"))
      (node (ref "U1") (pin "K26") (pinfunction "GPMC0_CLK_K26") (pintype "bidirectional"))
    )
    (net (code "57") (name "/GPMC0_CSN0") (class "Default")
      (node (ref "JP4") (pin "29") (pinfunction "29_29") (pintype "passive"))
      (node (ref "U1") (pin "F26") (pinfunction "GPMC0_CSN0_F26") (pintype "bidirectional"))
    )
    (net (code "58") (name "/GPMC0_CSN1") (class "Default")
      (node (ref "JP5") (pin "29") (pinfunction "29_29") (pintype "passive"))
      (node (ref "U1") (pin "F25") (pinfunction "GPMC0_CSN1_F25") (pintype "bidirectional"))
    )
    (net (code "59") (name "/GPMC0_CSN2") (class "Default")
      (node (ref "JP4") (pin "28") (pinfunction "28_28") (pintype "passive"))
      (node (ref "U1") (pin "E26") (pinfunction "GPMC0_CSN2_E26") (pintype "bidirectional"))
    )
    (net (code "60") (name "/GPMC0_CSN3") (class "Default")
      (node (ref "JP5") (pin "28") (pinfunction "28_28") (pintype "passive"))
      (node (ref "U1") (pin "E25") (pinfunction "GPMC0_CSN3_E25") (pintype "bidirectional"))
    )
    (net (code "61") (name "/GPMC0_DIR") (class "Default")
      (node (ref "JP4") (pin "30") (pinfunction "30_30") (pintype "passive"))
      (node (ref "U1") (pin "G25") (pinfunction "GPMC0_DIR_G25") (pintype "bidirectional"))
    )
    (net (code "62") (name "/GPMC0_OEN_REN") (class "Default")
      (node (ref "JP4") (pin "32") (pinfunction "32_32") (pintype "passive"))
      (node (ref "U1") (pin "H26") (pinfunction "GPMC0_OEN_REN_H26") (pintype "bidirectional"))
    )
    (net (code "63") (name "/GPMC0_WAIT0") (class "Default")
      (node (ref "JP2") (pin "34") (pinfunction "34_34") (pintype "passive"))
      (node (ref "U1") (pin "L25") (pinfunction "GPMC0_WAIT0_L25") (pintype "bidirectional"))
    )
    (net (code "64") (name "/GPMC0_WAIT1") (class "Default")
      (node (ref "JP2") (pin "35") (pinfunction "35_35") (pintype "passive"))
      (node (ref "U1") (pin "L26") (pinfunction "GPMC0_WAIT1_L26") (pintype "bidirectional"))
    )
    (net (code "65") (name "/GPMC0_WEN") (class "Default")
      (node (ref "JP2") (pin "39") (pinfunction "39_39") (pintype "passive"))
      (node (ref "U1") (pin "J25") (pinfunction "GPMC0_WEN_J25") (pintype "bidirectional"))
    )
    (net (code "66") (name "/GPMC0_WPN") (class "Default")
      (node (ref "JP5") (pin "31") (pinfunction "31_31") (pintype "passive"))
      (node (ref "U1") (pin "G26") (pinfunction "GPMC0_WPN_G26") (pintype "bidirectional"))
    )
    (net (code "67") (name "/I2C0_SCL") (class "Default")
      (node (ref "J7") (pin "2") (pinfunction "2_2") (pintype "bidirectional"))
      (node (ref "J8") (pin "2") (pinfunction "2_2") (pintype "bidirectional"))
      (node (ref "R52") (pin "1") (pinfunction "1_1") (pintype "passive"))
      (node (ref "U1") (pin "A12") (pinfunction "I2C0_SCL_A12") (pintype "bidirectional"))
      (node (ref "U4") (pin "1") (pinfunction "SCL_1") (pintype "bidirectional"))
      (node (ref "U6") (pin "10") (pinfunction "SCL_10") (pintype "bidirectional"))
      (node (ref "U7") (pin "5") (pinfunction "SCL_5") (pintype "input"))
      (node (ref "U8") (pin "5") (pinfunction "SCL_5") (pintype "input"))
    )
    (net (code "68") (name "/I2C0_SDA") (class "Default")
      (node (ref "J7") (pin "1") (pinfunction "1_1") (pintype "bidirectional"))
      (node (ref "J8") (pin "3") (pinfunction "3_3") (pintype "bidirectional"))
      (node (ref "R53") (pin "1") (pinfunction "1_1") (pintype "passive"))
      (node (ref "U1") (pin "B12") (pinfunction "I2C0_SDA_B12") (pintype "bidirectional"))
      (node (ref "U4") (pin "3") (pinfunction "SDA_3") (pintype "bidirectional"))
      (node (ref "U6") (pin "9") (pinfunction "SDA_9") (pintype "bidirectional"))
      (node (ref "U7") (pin "6") (pinfunction "SDA_6") (pintype "bidirectional"))
      (node (ref "U8") (pin "6") (pinfunction "SDA_6") (pintype "bidirectional"))
    )
    (net (code "69") (name "/I2C1_SCL") (class "Default")
      (node (ref "JP3") (pin "36") (pinfunction "36_36") (pintype "passive"))
      (node (ref "R69") (pin "1") (pinfunction "1_1") (pintype "passive"))
      (node (ref "U1") (pin "A13") (pinfunction "I2C1_SCL_A13") (pintype "bidirectional"))
    )
    (net (code "70") (name "/I2C1_SDA") (class "Default")
      (node (ref "JP3") (pin "35") (pinfunction "35_35") (pintype "passive"))
      (node (ref "R70") (pin "1") (pinfunction "1_1") (pintype "passive"))
      (node (ref "U1") (pin "B13") (pinfunction "I2C1_SDA_B13") (pintype "bidirectional"))
    )
    (net (code "71") (name "/LDO1-1P8-3P3") (class "Default")
      (node (ref "C23") (pin "1") (pinfunction "1_1") (pintype "passive"))
      (node (ref "C42") (pin "1") (pinfunction "1_1") (pintype "passive"))
      (node (ref "R43") (pin "2") (pinfunction "2_2") (pintype "passive"))
      (node (ref "R44") (pin "2") (pinfunction "2_2") (pintype "passive"))
      (node (ref "R45") (pin "2") (pinfunction "2_2") (pintype "passive"))
      (node (ref "R46") (pin "2") (pinfunction "2_2") (pintype "passive"))
      (node (ref "R47") (pin "2") (pinfunction "2_2") (pintype "passive"))
      (node (ref "U1") (pin "G21") (pinfunction "VDDSHV5_G21") (pintype "bidirectional"))
      (node (ref "U1") (pin "G22") (pinfunction "VDDSHV5_G22") (pintype "bidirectional"))
      (node (ref "U6") (pin "7") (pinfunction "VLDO1_7") (pintype "bidirectional"))
    )
    (net (code "72") (name "/LDO2-0P85") (class "Default")
      (node (ref "C17") (pin "1") (pinfunction "1_1") (pintype "passive"))
      (node (ref "C18") (pin "1") (pinfunction "1_1") (pintype "passive"))
      (node (ref "C19") (pin "1") (pinfunction "1_1") (pintype "passive"))
      (node (ref "C43") (pin "1") (pinfunction "1_1") (pintype "passive"))
      (node (ref "U1") (pin "H17") (pinfunction "VDDR_CORE_H17") (pintype "bidirectional"))
      (node (ref "U1") (pin "H18") (pinfunction "VDDR_CORE_H18") (pintype "bidirectional"))
      (node (ref "U1") (pin "J17") (pinfunction "VDDR_CORE_J17") (pintype "bidirectional"))
      (node (ref "U1") (pin "J18") (pinfunction "VDDR_CORE_J18") (pintype "bidirectional"))
      (node (ref "U1") (pin "K17") (pinfunction "VDDR_CORE_K17") (pintype "bidirectional"))
      (node (ref "U1") (pin "K18") (pinfunction "VDDR_CORE_K18") (pintype "bidirectional"))
      (node (ref "U1") (pin "L17") (pinfunction "VDDR_CORE_L17") (pintype "bidirectional"))
      (node (ref "U1") (pin "L18") (pinfunction "VDDR_CORE_L18") (pintype "bidirectional"))
      (node (ref "U6") (pin "19") (pinfunction "VLDO2_19") (pintype "bidirectional"))
    )
    (net (code "73") (name "/LDO3-1P8") (class "Default")
      (node (ref "C1") (pin "1") (pinfunction "1_1") (pintype "passive"))
      (node (ref "C2") (pin "1") (pinfunction "1_1") (pintype "passive"))
      (node (ref "C3") (pin "1") (pinfunction "1_1") (pintype "passive"))
      (node (ref "C4") (pin "1") (pinfunction "1_1") (pintype "passive"))
      (node (ref "C44") (pin "1") (pinfunction "1_1") (pintype "passive"))
      (node (ref "C46") (pin "1") (pinfunction "1_1") (pintype "passive"))
      (node (ref "C5") (pin "1") (pinfunction "1_1") (pintype "passive"))
      (node (ref "C54") (pin "1") (pinfunction "1_1") (pintype "passive"))
      (node (ref "R24") (pin "2") (pinfunction "2_2") (pintype "passive"))
      (node (ref "R50") (pin "1") (pinfunction "1_1") (pintype "passive"))
      (node (ref "U1") (pin "D15") (pinfunction "VDDS_OSC0_D15") (pintype "bidirectional"))
      (node (ref "U1") (pin "F13") (pinfunction "VDDA_MCU_F13") (pintype "bidirectional"))
      (node (ref "U1") (pin "F14") (pinfunction "VDDA_PLL2_F14") (pintype "bidirectional"))
      (node (ref "U1") (pin "N12") (pinfunction "VDDA_TEMP_N12") (pintype "bidirectional"))
      (node (ref "U1") (pin "N13") (pinfunction "VDDA_PLL0_N13") (pintype "bidirectional"))
      (node (ref "U1") (pin "N14") (pinfunction "VDDA_PLL1_N14") (pintype "bidirectional"))
      (node (ref "U1") (pin "P11") (pinfunction "VDDA_1P8_OLDI0_P11") (pintype "bidirectional"))
      (node (ref "U1") (pin "P12") (pinfunction "VDDA_1P8_USB_P12") (pintype "bidirectional"))
      (node (ref "U1") (pin "P13") (pinfunction "VDDA_1P8_CSIRX0_P13") (pintype "bidirectional"))
      (node (ref "U6") (pin "21") (pinfunction "VLDO3_21") (pintype "bidirectional"))
      (node (ref "Y1") (pin "4") (pinfunction "VDD_4") (pintype "bidirectional"))
      (node (ref "Y2") (pin "4") (pinfunction "VDD_4") (pintype "bidirectional"))
    )
    (net (code "74") (name "/LDO4-2P5") (class "Default")
      (node (ref "C20") (pin "1") (pinfunction "1_1") (pintype "passive"))
      (node (ref "C45") (pin "1") (pinfunction "1_1") (pintype "passive"))
      (node (ref "U1") (pin "N10") (pinfunction "DDR_VPP_N10") (pintype "bidirectional"))
      (node (ref "U6") (pin "23") (pinfunction "VLDO4_23") (pintype "bidirectional"))
    )
    (net (code "75") (name "/MCAN0_RX") (class "Default")
      (node (ref "JP3") (pin "37") (pinfunction "37_37") (pintype "passive"))
      (node (ref "U1") (pin "A11") (pinfunction "MCAN0_RX_A11") (pintype "bidirectional"))
    )
    (net (code "76") (name "/MCAN0_TX") (class "Default")
      (node (ref "JP3") (pin "38") (pinfunction "38_38") (pintype "passive"))
      (node (ref "U1") (pin "B11") (pinfunction "MCAN0_TX_B11") (pintype "bidirectional"))
    )
    (net (code "77") (name "/MCASP0_ACLKR") (class "Default")
      (node (ref "JP3") (pin "39") (pinfunction "39_39") (pintype "passive"))
      (node (ref "U1") (pin "B19") (pinfunction "MCASP0_ACLKR_B19") (pintype "bidirectional"))
    )
    (net (code "78") (name "/MCASP0_ACLKX") (class "Default")
      (node (ref "R58") (pin "2") (pinfunction "2_2") (pintype "passive"))
      (node (ref "U1") (pin "A18") (pinfunction "MCASP0_ACLKX_A18") (pintype "bidirectional"))
    )
    (net (code "79") (name "/MCASP0_AFSR") (class "Default")
      (node (ref "JP3") (pin "40") (pinfunction "40_40") (pintype "passive"))
      (node (ref "U1") (pin "A19") (pinfunction "MCASP0_AFSR_A19") (pintype "bidirectional"))
    )
    (net (code "80") (name "/MCASP0_AFSX") (class "Default")
      (node (ref "R59") (pin "2") (pinfunction "2_2") (pintype "passive"))
      (node (ref "U1") (pin "B18") (pinfunction "MCASP0_AFSX_B18") (pintype "bidirectional"))
    )
    (net (code "81") (name "/MCASP0_AXR0") (class "Default")
      (node (ref "R60") (pin "2") (pinfunction "2_2") (pintype "passive"))
      (node (ref "U1") (pin "B17") (pinfunction "MCASP0_AXR0_B17") (pintype "bidirectional"))
    )
    (net (code "82") (name "/MCASP0_AXR1") (class "Default")
      (node (ref "R61") (pin "2") (pinfunction "2_2") (pintype "passive"))
      (node (ref "U1") (pin "A17") (pinfunction "MCASP0_AXR1_A17") (pintype "bidirectional"))
    )
    (net (code "83") (name "/MCASP0_AXR2") (class "Default")
      (node (ref "JP4") (pin "39") (pinfunction "39_39") (pintype "passive"))
      (node (ref "U1") (pin "B16") (pinfunction "MCASP0_AXR2_B16") (pintype "bidirectional"))
    )
    (net (code "84") (name "/MCASP0_AXR3") (class "Default")
      (node (ref "R55") (pin "1") (pinfunction "1_1") (pintype "passive"))
      (node (ref "U1") (pin "A16") (pinfunction "MCASP0_AXR3_A16") (pintype "bidirectional"))
    )
    (net (code "85") (name "/MCU_ERRORN") (class "Default")
      (node (ref "TP2") (pin "TP") (pinfunction "TP_TP") (pintype "input"))
      (node (ref "U1") (pin "D7") (pinfunction "MCU_ERRORN_D7") (pintype "bidirectional"))
    )
    (net (code "86") (name "/MCU_I2C0_SCL") (class "Default")
      (node (ref "JP5") (pin "14") (pinfunction "14_14") (pintype "passive"))
      (node (ref "R65") (pin "1") (pinfunction "1_1") (pintype "passive"))
      (node (ref "U1") (pin "A7") (pinfunction "MCU_I2C0_SCL_A7") (pintype "bidirectional"))
    )
    (net (code "87") (name "/MCU_I2C0_SDA") (class "Default")
      (node (ref "JP4") (pin "14") (pinfunction "14_14") (pintype "passive"))
      (node (ref "R66") (pin "1") (pinfunction "1_1") (pintype "passive"))
      (node (ref "U1") (pin "B7") (pinfunction "MCU_I2C0_SDA_B7") (pintype "bidirectional"))
    )
    (net (code "88") (name "/MCU_MCAN0_RX") (class "Default")
      (node (ref "JP5") (pin "4") (pinfunction "4_4") (pintype "passive"))
      (node (ref "U1") (pin "E1") (pinfunction "MCU_MCAN0_RX_E1") (pintype "bidirectional"))
    )
    (net (code "89") (name "/MCU_MCAN0_TX") (class "Default")
      (node (ref "JP5") (pin "5") (pinfunction "5_5") (pintype "passive"))
      (node (ref "U1") (pin "E2") (pinfunction "MCU_MCAN0_TX_E2") (pintype "bidirectional"))
    )
    (net (code "90") (name "/MCU_MCAN1_RX") (class "Default")
      (node (ref "JP5") (pin "2") (pinfunction "2_2") (pintype "passive"))
      (node (ref "U1") (pin "F1") (pinfunction "MCU_MCAN1_RX_F1") (pintype "bidirectional"))
    )
    (net (code "91") (name "/MCU_MCAN1_TX") (class "Default")
      (node (ref "JP5") (pin "3") (pinfunction "3_3") (pintype "passive"))
      (node (ref "U1") (pin "F2") (pinfunction "MCU_MCAN1_TX_F2") (pintype "bidirectional"))
    )
    (net (code "92") (name "/MCU_OSC0_XI") (class "Default")
      (node (ref "U1") (pin "G1") (pinfunction "MCU_OSC0_XI_G1") (pintype "bidirectional"))
      (node (ref "Y2") (pin "3") (pinfunction "OUT_3") (pintype "bidirectional"))
    )
    (net (code "93") (name "/MCU_PORZ") (class "Default")
      (node (ref "JP4") (pin "15") (pinfunction "15_15") (pintype "passive"))
      (node (ref "R24") (pin "1") (pinfunction "1_1") (pintype "passive"))
      (node (ref "U1") (pin "D6") (pinfunction "MCU_PORZ_D6") (pintype "bidirectional"))
      (node (ref "U6") (pin "18") (pinfunction "NRSTOUT_18") (pintype "bidirectional"))
    )
    (net (code "94") (name "/MCU_RESETSTATZ") (class "Default")
      (node (ref "TP3") (pin "TP") (pinfunction "TP_TP") (pintype "input"))
      (node (ref "U1") (pin "C6") (pinfunction "MCU_RESETSTATZ_C6") (pintype "bidirectional"))
    )
    (net (code "95") (name "/MCU_RESETZ") (class "Default")
      (node (ref "R10") (pin "1") (pinfunction "1_1") (pintype "passive"))
      (node (ref "U1") (pin "C5") (pinfunction "MCU_RESETZ_C5") (pintype "bidirectional"))
    )
    (net (code "96") (name "/MCU_SPI0_CLK") (class "Default")
      (node (ref "JP4") (pin "11") (pinfunction "11_11") (pintype "passive"))
      (node (ref "U1") (pin "A4") (pinfunction "MCU_SPI0_CLK_A4") (pintype "bidirectional"))
    )
    (net (code "97") (name "/MCU_SPI0_CS0") (class "Default")
      (node (ref "JP5") (pin "13") (pinfunction "13_13") (pintype "passive"))
      (node (ref "U1") (pin "B6") (pinfunction "MCU_SPI0_CS0_B6") (pintype "bidirectional"))
    )
    (net (code "98") (name "/MCU_SPI0_CS1") (class "Default")
      (node (ref "JP4") (pin "13") (pinfunction "13_13") (pintype "passive"))
      (node (ref "U1") (pin "A6") (pinfunction "MCU_SPI0_CS1_A6") (pintype "bidirectional"))
    )
    (net (code "99") (name "/MCU_SPI0_D0") (class "Default")
      (node (ref "JP5") (pin "12") (pinfunction "12_12") (pintype "passive"))
      (node (ref "U1") (pin "B5") (pinfunction "MCU_SPI0_D0_B5") (pintype "bidirectional"))
    )
    (net (code "100") (name "/MCU_SPI0_D1") (class "Default")
      (node (ref "JP4") (pin "12") (pinfunction "12_12") (pintype "passive"))
      (node (ref "U1") (pin "A5") (pinfunction "MCU_SPI0_D1_A5") (pintype "bidirectional"))
    )
    (net (code "101") (name "/MCU_UART0_CTSN") (class "Default")
      (node (ref "JP5") (pin "11") (pinfunction "11_11") (pintype "passive"))
      (node (ref "U1") (pin "B4") (pinfunction "MCU_UART0_CTSN_B4") (pintype "bidirectional"))
    )
    (net (code "102") (name "/MCU_UART0_RTSN") (class "Default")
      (node (ref "JP4") (pin "10") (pinfunction "10_10") (pintype "passive"))
      (node (ref "U1") (pin "A3") (pinfunction "MCU_UART0_RTSN_A3") (pintype "bidirectional"))
    )
    (net (code "103") (name "/MCU_UART0_RXD") (class "Default")
      (node (ref "JP4") (pin "9") (pinfunction "9_9") (pintype "passive"))
      (node (ref "U1") (pin "B2") (pinfunction "MCU_UART0_RXD_B2") (pintype "bidirectional"))
    )
    (net (code "104") (name "/MCU_UART0_TXD") (class "Default")
      (node (ref "JP5") (pin "10") (pinfunction "10_10") (pintype "passive"))
      (node (ref "U1") (pin "B3") (pinfunction "MCU_UART0_TXD_B3") (pintype "bidirectional"))
    )
    (net (code "105") (name "/MDIO0_MDC") (class "Default")
      (node (ref "JP3") (pin "12") (pinfunction "12_12") (pintype "passive"))
      (node (ref "U1") (pin "V26") (pinfunction "MDIO0_MDC_V26") (pintype "bidirectional"))
    )
    (net (code "106") (name "/MDIO0_MDIO") (class "Default")
      (node (ref "JP2") (pin "12") (pinfunction "12_12") (pintype "passive"))
      (node (ref "U1") (pin "U26") (pinfunction "MDIO0_MDIO_U26") (pintype "bidirectional"))
    )
    (net (code "107") (name "/MMC0_CLK") (class "Default")
      (node (ref "JP4") (pin "5") (pinfunction "5_5") (pintype "passive"))
      (node (ref "R67") (pin "1") (pinfunction "1_1") (pintype "passive"))
      (node (ref "U1") (pin "J1") (pinfunction "MMC0_CLK_J1") (pintype "bidirectional"))
    )
    (net (code "108") (name "/MMC0_CMD") (class "Default")
      (node (ref "JP4") (pin "6") (pinfunction "6_6") (pintype "passive"))
      (node (ref "R68") (pin "1") (pinfunction "1_1") (pintype "passive"))
      (node (ref "U1") (pin "K1") (pinfunction "MMC0_CMD_K1") (pintype "bidirectional"))
    )
    (net (code "109") (name "/MMC0_DAT0") (class "Default")
      (node (ref "JP3") (pin "4") (pinfunction "4_4") (pintype "passive"))
      (node (ref "U1") (pin "K2") (pinfunction "MMC0_DAT0_K2") (pintype "bidirectional"))
    )
    (net (code "110") (name "/MMC0_DAT1") (class "Default")
      (node (ref "JP3") (pin "3") (pinfunction "3_3") (pintype "passive"))
      (node (ref "U1") (pin "L1") (pinfunction "MMC0_DAT1_L1") (pintype "bidirectional"))
    )
    (net (code "111") (name "/MMC0_DAT2") (class "Default")
      (node (ref "JP4") (pin "1") (pinfunction "1_1") (pintype "passive"))
      (node (ref "U1") (pin "L2") (pinfunction "MMC0_DAT2_L2") (pintype "bidirectional"))
    )
    (net (code "112") (name "/MMC0_DAT3") (class "Default")
      (node (ref "JP4") (pin "2") (pinfunction "2_2") (pintype "passive"))
      (node (ref "U1") (pin "M1") (pinfunction "MMC0_DAT3_M1") (pintype "bidirectional"))
    )
    (net (code "113") (name "/MMC0_DAT4") (class "Default")
      (node (ref "JP3") (pin "6") (pinfunction "6_6") (pintype "passive"))
      (node (ref "U1") (pin "M2") (pinfunction "MMC0_DAT4_M2") (pintype "bidirectional"))
    )
    (net (code "114") (name "/MMC0_DAT5") (class "Default")
      (node (ref "JP3") (pin "5") (pinfunction "5_5") (pintype "passive"))
      (node (ref "U1") (pin "N1") (pinfunction "MMC0_DAT5_N1") (pintype "bidirectional"))
    )
    (net (code "115") (name "/MMC0_DAT6") (class "Default")
      (node (ref "JP4") (pin "4") (pinfunction "4_4") (pintype "passive"))
      (node (ref "U1") (pin "N2") (pinfunction "MMC0_DAT6_N2") (pintype "bidirectional"))
    )
    (net (code "116") (name "/MMC0_DAT7") (class "Default")
      (node (ref "JP4") (pin "3") (pinfunction "3_3") (pintype "passive"))
      (node (ref "U1") (pin "P1") (pinfunction "MMC0_DAT7_P1") (pintype "bidirectional"))
    )
    (net (code "117") (name "/MMC1_CLK") (class "Default")
      (node (ref "R33") (pin "2") (pinfunction "2_2") (pintype "passive"))
      (node (ref "U1") (pin "B21") (pinfunction "MMC1_CLK_B21") (pintype "bidirectional"))
    )
    (net (code "118") (name "/MMC1_CMD") (class "Default")
      (node (ref "R45") (pin "1") (pinfunction "1_1") (pintype "passive"))
      (node (ref "U1") (pin "A21") (pinfunction "MMC1_CMD_A21") (pintype "bidirectional"))
      (node (ref "X1") (pin "PIN3") (pinfunction "CMD_PIN3") (pintype "bidirectional"))
    )
    (net (code "119") (name "/MMC1_DAT0") (class "Default")
      (node (ref "R46") (pin "1") (pinfunction "1_1") (pintype "passive"))
      (node (ref "U1") (pin "A22") (pinfunction "MMC1_DAT0_A22") (pintype "bidirectional"))
      (node (ref "X1") (pin "PIN7") (pinfunction "DAT0_PIN7") (pintype "bidirectional"))
    )
    (net (code "120") (name "/MMC1_DAT1") (class "Default")
      (node (ref "R47") (pin "1") (pinfunction "1_1") (pintype "passive"))
      (node (ref "U1") (pin "B22") (pinfunction "MMC1_DAT1_B22") (pintype "bidirectional"))
      (node (ref "X1") (pin "PIN8") (pinfunction "DAT1_PIN8") (pintype "bidirectional"))
    )
    (net (code "121") (name "/MMC1_DAT2") (class "Default")
      (node (ref "R43") (pin "1") (pinfunction "1_1") (pintype "passive"))
      (node (ref "U1") (pin "A20") (pinfunction "MMC1_DAT2_A20") (pintype "bidirectional"))
      (node (ref "X1") (pin "PIN1") (pinfunction "DAT2_PIN1") (pintype "bidirectional"))
    )
    (net (code "122") (name "/MMC1_DAT3") (class "Default")
      (node (ref "R44") (pin "1") (pinfunction "1_1") (pintype "passive"))
      (node (ref "U1") (pin "B20") (pinfunction "MMC1_DAT3_B20") (pintype "bidirectional"))
      (node (ref "X1") (pin "PIN2") (pinfunction "CD/DAT3_PIN2") (pintype "bidirectional"))
    )
    (net (code "123") (name "/MMC1_SDCD") (class "Default")
      (node (ref "U1") (pin "A23") (pinfunction "MMC1_SDCD_A23") (pintype "bidirectional"))
      (node (ref "U11") (pin "4") (pinfunction "Y_4") (pintype "output"))
    )
    (net (code "124") (name "/MMC1_SDWP") (class "Default")
      (node (ref "R13") (pin "1") (pinfunction "1_1") (pintype "passive"))
      (node (ref "U1") (pin "B23") (pinfunction "MMC1_SDWP_B23") (pintype "bidirectional"))
      (node (ref "U6") (pin "12") (pinfunction "VSEL_SD/VSEL_DDR_12") (pintype "bidirectional"))
    )
    (net (code "125") (name "/MMC2_CLK") (class "Default")
      (node (ref "JP4") (pin "20") (pinfunction "20_20") (pintype "passive"))
      (node (ref "U1") (pin "D23") (pinfunction "MMC2_CLK_D23") (pintype "bidirectional"))
    )
    (net (code "126") (name "/MMC2_CMD") (class "Default")
      (node (ref "JP5") (pin "20") (pinfunction "20_20") (pintype "passive"))
      (node (ref "U1") (pin "C23") (pinfunction "MMC2_CMD_C23") (pintype "bidirectional"))
    )
    (net (code "127") (name "/MMC2_DAT0") (class "Default")
      (node (ref "JP5") (pin "19") (pinfunction "19_19") (pintype "passive"))
      (node (ref "U1") (pin "D22") (pinfunction "MMC2_DAT0_D22") (pintype "bidirectional"))
    )
    (net (code "128") (name "/MMC2_DAT1") (class "Default")
      (node (ref "JP4") (pin "19") (pinfunction "19_19") (pintype "passive"))
      (node (ref "U1") (pin "C22") (pinfunction "MMC2_DAT1_C22") (pintype "bidirectional"))
    )
    (net (code "129") (name "/MMC2_DAT2") (class "Default")
      (node (ref "JP5") (pin "18") (pinfunction "18_18") (pintype "passive"))
      (node (ref "U1") (pin "D21") (pinfunction "MMC2_DAT2_D21") (pintype "bidirectional"))
    )
    (net (code "130") (name "/MMC2_DAT3") (class "Default")
      (node (ref "JP4") (pin "18") (pinfunction "18_18") (pintype "passive"))
      (node (ref "U1") (pin "C21") (pinfunction "MMC2_DAT3_C21") (pintype "bidirectional"))
    )
    (net (code "131") (name "/MMC2_SDCD") (class "Default")
      (node (ref "JP5") (pin "17") (pinfunction "17_17") (pintype "passive"))
      (node (ref "U1") (pin "D20") (pinfunction "MMC2_SDCD_D20") (pintype "bidirectional"))
    )
    (net (code "132") (name "/MMC2_SDWP") (class "Default")
      (node (ref "JP4") (pin "17") (pinfunction "17_17") (pintype "passive"))
      (node (ref "U1") (pin "C20") (pinfunction "MMC2_SDWP_C20") (pintype "bidirectional"))
    )
    (net (code "133") (name "/OSPI0_CLK") (class "Default")
      (node (ref "JP4") (pin "23") (pinfunction "23_23") (pintype "passive"))
      (node (ref "U1") (pin "A24") (pinfunction "OSPI0_CLK_A24") (pintype "bidirectional"))
    )
    (net (code "134") (name "/OSPI0_CSN0") (class "Default")
      (node (ref "JP4") (pin "22") (pinfunction "22_22") (pintype "passive"))
      (node (ref "U1") (pin "D25") (pinfunction "OSPI0_CSN0_D25") (pintype "bidirectional"))
    )
    (net (code "135") (name "/OSPI0_CSN1") (class "Default")
      (node (ref "D7") (pin "CATHODE") (pinfunction "C_CATHODE") (pintype "passive"))
      (node (ref "U1") (pin "C25") (pinfunction "OSPI0_CSN1_C25") (pintype "bidirectional"))
    )
    (net (code "136") (name "/OSPI0_CSN2") (class "Default")
      (node (ref "JP4") (pin "21") (pinfunction "21_21") (pintype "passive"))
      (node (ref "U1") (pin "D24") (pinfunction "OSPI0_CSN2_D24") (pintype "bidirectional"))
    )
    (net (code "137") (name "/OSPI0_CSN3") (class "Default")
      (node (ref "JP5") (pin "21") (pinfunction "21_21") (pintype "passive"))
      (node (ref "U1") (pin "C24") (pinfunction "OSPI0_CSN3_C24") (pintype "bidirectional"))
    )
    (net (code "138") (name "/OSPI0_D0") (class "Default")
      (node (ref "JP5") (pin "24") (pinfunction "24_24") (pintype "passive"))
      (node (ref "U1") (pin "B24") (pinfunction "OSPI0_D0_B24") (pintype "bidirectional"))
    )
    (net (code "139") (name "/OSPI0_D1") (class "Default")
      (node (ref "JP4") (pin "24") (pinfunction "24_24") (pintype "passive"))
      (node (ref "U1") (pin "A25") (pinfunction "OSPI0_D1_A25") (pintype "bidirectional"))
    )
    (net (code "140") (name "/OSPI0_D2") (class "Default")
      (node (ref "JP5") (pin "25") (pinfunction "25_25") (pintype "passive"))
      (node (ref "U1") (pin "B25") (pinfunction "OSPI0_D2_B25") (pintype "bidirectional"))
    )
    (net (code "141") (name "/OSPI0_D3") (class "Default")
      (node (ref "JP4") (pin "25") (pinfunction "25_25") (pintype "passive"))
      (node (ref "U1") (pin "A26") (pinfunction "OSPI0_D3_A26") (pintype "bidirectional"))
    )
    (net (code "142") (name "/OSPI0_D4") (class "Default")
      (node (ref "JP5") (pin "26") (pinfunction "26_26") (pintype "passive"))
      (node (ref "U1") (pin "B26") (pinfunction "OSPI0_D4_B26") (pintype "bidirectional"))
    )
    (net (code "143") (name "/OSPI0_D5") (class "Default")
      (node (ref "JP4") (pin "26") (pinfunction "26_26") (pintype "passive"))
      (node (ref "U1") (pin "B27") (pinfunction "OSPI0_D5_B27") (pintype "bidirectional"))
    )
    (net (code "144") (name "/OSPI0_D6") (class "Default")
      (node (ref "JP5") (pin "27") (pinfunction "27_27") (pintype "passive"))
      (node (ref "U1") (pin "C27") (pinfunction "OSPI0_D6_C27") (pintype "bidirectional"))
    )
    (net (code "145") (name "/OSPI0_D7") (class "Default")
      (node (ref "JP4") (pin "27") (pinfunction "27_27") (pintype "passive"))
      (node (ref "U1") (pin "C28") (pinfunction "OSPI0_D7_C28") (pintype "bidirectional"))
    )
    (net (code "146") (name "/OSPI0_DQS") (class "Default")
      (node (ref "JP5") (pin "23") (pinfunction "23_23") (pintype "passive"))
      (node (ref "U1") (pin "D26") (pinfunction "OSPI0_DQS_D26") (pintype "bidirectional"))
    )
    (net (code "147") (name "/OSPI0_LBCLKO") (class "Default")
      (node (ref "JP5") (pin "22") (pinfunction "22_22") (pintype "passive"))
      (node (ref "R74") (pin "2") (pinfunction "2_2") (pintype "passive"))
      (node (ref "U1") (pin "C26") (pinfunction "OSPI0_LBCLKO_C26") (pintype "bidirectional"))
    )
    (net (code "148") (name "/OSPI0_LBCLKO_R") (class "Default")
      (node (ref "J1") (pin "1") (pinfunction "1_1") (pintype "bidirectional"))
      (node (ref "R74") (pin "1") (pinfunction "1_1") (pintype "passive"))
      (node (ref "U13") (pin "C1") (pinfunction "2Y_C1") (pintype "bidirectional"))
    )
    (net (code "149") (name "/PMIC_LPM_EN0") (class "Default")
      (node (ref "R23") (pin "1") (pinfunction "1_1") (pintype "passive"))
      (node (ref "U1") (pin "D5") (pinfunction "PMIC_LPM_EN0_D5") (pintype "bidirectional"))
      (node (ref "U6") (pin "31") (pinfunction "MODE_STBY_31") (pintype "bidirectional"))
    )
    (net (code "150") (name "/PMIC_PWR_BTN") (class "Default")
      (node (ref "R22") (pin "1") (pinfunction "1_1") (pintype "passive"))
      (node (ref "S1") (pin "P$1") (pinfunction "P$1_P$1") (pintype "bidirectional"))
      (node (ref "S1") (pin "P$2") (pinfunction "P$2_P$2") (pintype "bidirectional"))
      (node (ref "U6") (pin "25") (pinfunction "EN/PB/VSENSE_25") (pintype "bidirectional"))
    )
    (net (code "151") (name "/PORZ_OUT") (class "Default")
      (node (ref "TP1") (pin "TP") (pinfunction "TP_TP") (pintype "input"))
      (node (ref "U1") (pin "D18") (pinfunction "PORZ_OUT_D18") (pintype "bidirectional"))
    )
    (net (code "152") (name "/RESETSTATZ") (class "Default")
      (node (ref "D6") (pin "CATHODE") (pinfunction "C_CATHODE") (pintype "passive"))
      (node (ref "U1") (pin "C18") (pinfunction "RESETSTATZ_C18") (pintype "bidirectional"))
      (node (ref "U13") (pin "B1") (pinfunction "1A_B1") (pintype "bidirectional"))
      (node (ref "U6") (pin "28") (pinfunction "MODE_RESET_28") (pintype "bidirectional"))
    )
    (net (code "153") (name "/RESET_REQZ") (class "Default")
      (node (ref "R11") (pin "1") (pinfunction "1_1") (pintype "passive"))
      (node (ref "U1") (pin "D17") (pinfunction "RESET_REQZ_D17") (pintype "bidirectional"))
    )
    (net (code "154") (name "/RGMII1_RD0") (class "Default")
      (node (ref "JP2") (pin "8") (pinfunction "8_8") (pintype "passive"))
      (node (ref "U1") (pin "U22") (pinfunction "RGMII1_RD0_U22") (pintype "bidirectional"))
    )
    (net (code "155") (name "/RGMII1_RD1") (class "Default")
      (node (ref "JP2") (pin "7") (pinfunction "7_7") (pintype "passive"))
      (node (ref "U1") (pin "V22") (pinfunction "RGMII1_RD1_V22") (pintype "bidirectional"))
    )
    (net (code "156") (name "/RGMII1_RD2") (class "Default")
      (node (ref "JP2") (pin "6") (pinfunction "6_6") (pintype "passive"))
      (node (ref "U1") (pin "U21") (pinfunction "RGMII1_RD2_U21") (pintype "bidirectional"))
    )
    (net (code "157") (name "/RGMII1_RD3") (class "Default")
      (node (ref "JP2") (pin "5") (pinfunction "5_5") (pintype "passive"))
      (node (ref "U1") (pin "V21") (pinfunction "RGMII1_RD3_V21") (pintype "bidirectional"))
    )
    (net (code "158") (name "/RGMII1_RXC") (class "Default")
      (node (ref "JP2") (pin "4") (pinfunction "4_4") (pintype "passive"))
      (node (ref "U1") (pin "U20") (pinfunction "RGMII1_RXC_U20") (pintype "bidirectional"))
    )
    (net (code "159") (name "/RGMII1_RX_CTL") (class "Default")
      (node (ref "JP2") (pin "3") (pinfunction "3_3") (pintype "passive"))
      (node (ref "U1") (pin "V20") (pinfunction "RGMII1_RX_CTL_V20") (pintype "bidirectional"))
    )
    (net (code "160") (name "/RGMII1_TD0") (class "Default")
      (node (ref "JP2") (pin "11") (pinfunction "11_11") (pintype "passive"))
      (node (ref "U1") (pin "U25") (pinfunction "RGMII1_TD0_U25") (pintype "bidirectional"))
    )
    (net (code "161") (name "/RGMII1_TD1") (class "Default")
      (node (ref "JP3") (pin "11") (pinfunction "11_11") (pintype "passive"))
      (node (ref "U1") (pin "V25") (pinfunction "RGMII1_TD1_V25") (pintype "bidirectional"))
    )
    (net (code "162") (name "/RGMII1_TD2") (class "Default")
      (node (ref "JP2") (pin "10") (pinfunction "10_10") (pintype "passive"))
      (node (ref "U1") (pin "U24") (pinfunction "RGMII1_TD2_U24") (pintype "bidirectional"))
    )
    (net (code "163") (name "/RGMII1_TD3") (class "Default")
      (node (ref "JP3") (pin "10") (pinfunction "10_10") (pintype "passive"))
      (node (ref "U1") (pin "V24") (pinfunction "RGMII1_TD3_V24") (pintype "bidirectional"))
    )
    (net (code "164") (name "/RGMII1_TXC") (class "Default")
      (node (ref "JP2") (pin "9") (pinfunction "9_9") (pintype "passive"))
      (node (ref "U1") (pin "U23") (pinfunction "RGMII1_TXC_U23") (pintype "bidirectional"))
    )
    (net (code "165") (name "/RGMII1_TX_CTL") (class "Default")
      (node (ref "JP3") (pin "9") (pinfunction "9_9") (pintype "passive"))
      (node (ref "U1") (pin "V23") (pinfunction "RGMII1_TX_CTL_V23") (pintype "bidirectional"))
    )
    (net (code "166") (name "/RGMII2_RD0") (class "Default")
      (node (ref "JP2") (pin "18") (pinfunction "18_18") (pintype "passive"))
      (node (ref "U1") (pin "T25") (pinfunction "RGMII2_RD0_T25") (pintype "bidirectional"))
    )
    (net (code "167") (name "/RGMII2_RD1") (class "Default")
      (node (ref "JP3") (pin "18") (pinfunction "18_18") (pintype "passive"))
      (node (ref "U1") (pin "R24") (pinfunction "RGMII2_RD1_R24") (pintype "bidirectional"))
    )
    (net (code "168") (name "/RGMII2_RD2") (class "Default")
      (node (ref "JP2") (pin "17") (pinfunction "17_17") (pintype "passive"))
      (node (ref "U1") (pin "T24") (pinfunction "RGMII2_RD2_T24") (pintype "bidirectional"))
    )
    (net (code "169") (name "/RGMII2_RD3") (class "Default")
      (node (ref "JP3") (pin "17") (pinfunction "17_17") (pintype "passive"))
      (node (ref "U1") (pin "R23") (pinfunction "RGMII2_RD3_R23") (pintype "bidirectional"))
    )
    (net (code "170") (name "/RGMII2_RXC") (class "Default")
      (node (ref "JP3") (pin "16") (pinfunction "16_16") (pintype "passive"))
      (node (ref "U1") (pin "R22") (pinfunction "RGMII2_RXC_R22") (pintype "bidirectional"))
    )
    (net (code "171") (name "/RGMII2_RX_CTL") (class "Default")
      (node (ref "JP2") (pin "16") (pinfunction "16_16") (pintype "passive"))
      (node (ref "U1") (pin "T23") (pinfunction "RGMII2_RX_CTL_T23") (pintype "bidirectional"))
    )
    (net (code "172") (name "/RGMII2_TD0") (class "Default")
      (node (ref "JP2") (pin "15") (pinfunction "15_15") (pintype "passive"))
      (node (ref "U1") (pin "T22") (pinfunction "RGMII2_TD0_T22") (pintype "bidirectional"))
    )
    (net (code "173") (name "/RGMII2_TD1") (class "Default")
      (node (ref "JP3") (pin "15") (pinfunction "15_15") (pintype "passive"))
      (node (ref "U1") (pin "R21") (pinfunction "RGMII2_TD1_R21") (pintype "bidirectional"))
    )
    (net (code "174") (name "/RGMII2_TD2") (class "Default")
      (node (ref "JP2") (pin "14") (pinfunction "14_14") (pintype "passive"))
      (node (ref "U1") (pin "T21") (pinfunction "RGMII2_TD2_T21") (pintype "bidirectional"))
    )
    (net (code "175") (name "/RGMII2_TD3") (class "Default")
      (node (ref "JP3") (pin "14") (pinfunction "14_14") (pintype "passive"))
      (node (ref "U1") (pin "R20") (pinfunction "RGMII2_TD3_R20") (pintype "bidirectional"))
    )
    (net (code "176") (name "/RGMII2_TXC") (class "Default")
      (node (ref "JP3") (pin "13") (pinfunction "13_13") (pintype "passive"))
      (node (ref "U1") (pin "R19") (pinfunction "RGMII2_TXC_R19") (pintype "bidirectional"))
    )
    (net (code "177") (name "/RGMII2_TX_CTL") (class "Default")
      (node (ref "JP2") (pin "13") (pinfunction "13_13") (pintype "passive"))
      (node (ref "U1") (pin "T20") (pinfunction "RGMII2_TX_CTL_T20") (pintype "bidirectional"))
    )
    (net (code "178") (name "/RXD") (class "Default")
      (node (ref "JP1") (pin "2") (pinfunction "2_2") (pintype "passive"))
      (node (ref "R76") (pin "2") (pinfunction "2_2") (pintype "passive"))
      (node (ref "U12") (pin "B1") (pinfunction "1A_B1") (pintype "bidirectional"))
    )
    (net (code "179") (name "/SPI0_CLK") (class "Default")
      (node (ref "JP4") (pin "37") (pinfunction "37_37") (pintype "passive"))
      (node (ref "U1") (pin "C11") (pinfunction "SPI0_CLK_C11") (pintype "bidirectional"))
    )
    (net (code "180") (name "/SPI0_CS0") (class "Default")
      (node (ref "JP4") (pin "38") (pinfunction "38_38") (pintype "passive"))
      (node (ref "U1") (pin "D13") (pinfunction "SPI0_CS0_D13") (pintype "bidirectional"))
    )
    (net (code "181") (name "/SPI0_CS1") (class "Default")
      (node (ref "JP3") (pin "2") (pinfunction "2_2") (pintype "passive"))
      (node (ref "U1") (pin "C13") (pinfunction "SPI0_CS1_C13") (pintype "bidirectional"))
    )
    (net (code "182") (name "/SPI0_D0") (class "Default")
      (node (ref "JP4") (pin "36") (pinfunction "36_36") (pintype "passive"))
      (node (ref "U1") (pin "D12") (pinfunction "SPI0_D0_D12") (pintype "bidirectional"))
    )
    (net (code "183") (name "/SPI0_D1") (class "Default")
      (node (ref "JP4") (pin "35") (pinfunction "35_35") (pintype "passive"))
      (node (ref "U1") (pin "C12") (pinfunction "SPI0_D1_C12") (pintype "bidirectional"))
    )
    (net (code "184") (name "/TCK") (class "Default")
      (node (ref "R19") (pin "1") (pinfunction "1_1") (pintype "passive"))
      (node (ref "TC1") (pin "4") (pinfunction "4_4") (pintype "passive"))
      (node (ref "U1") (pin "D9") (pinfunction "TCK_D9") (pintype "bidirectional"))
    )
    (net (code "185") (name "/TDI") (class "Default")
      (node (ref "R17") (pin "1") (pinfunction "1_1") (pintype "passive"))
      (node (ref "TC1") (pin "8") (pinfunction "8_8") (pintype "passive"))
      (node (ref "U1") (pin "D10") (pinfunction "TDI_D10") (pintype "bidirectional"))
    )
    (net (code "186") (name "/TDO") (class "Default")
      (node (ref "TC1") (pin "6") (pinfunction "6_6") (pintype "passive"))
      (node (ref "U1") (pin "D11") (pinfunction "TDO_D11") (pintype "bidirectional"))
    )
    (net (code "187") (name "/TMS") (class "Default")
      (node (ref "R18") (pin "1") (pinfunction "1_1") (pintype "passive"))
      (node (ref "TC1") (pin "2") (pinfunction "2_2") (pintype "passive"))
      (node (ref "U1") (pin "C10") (pinfunction "TMS_C10") (pintype "bidirectional"))
    )
    (net (code "188") (name "/TPS22965_EN") (class "Default")
      (node (ref "R73") (pin "1") (pinfunction "1_1") (pintype "passive"))
      (node (ref "U5") (pin "3") (pinfunction "ON_3") (pintype "input"))
      (node (ref "U6") (pin "17") (pinfunction "GPO2_17") (pintype "bidirectional"))
    )
    (net (code "189") (name "/TRSTN") (class "Default")
      (node (ref "R14") (pin "2") (pinfunction "2_2") (pintype "passive"))
      (node (ref "TC1") (pin "9") (pinfunction "9_9") (pintype "passive"))
      (node (ref "U1") (pin "C9") (pinfunction "TRSTN_C9") (pintype "bidirectional"))
    )
    (net (code "190") (name "/TS_INT#") (class "Default")
      (node (ref "J8") (pin "9") (pinfunction "9_9") (pintype "bidirectional"))
      (node (ref "TP7") (pin "TP") (pinfunction "TP_TP") (pintype "input"))
      (node (ref "U13") (pin "D2") (pinfunction "2A_D2") (pintype "bidirectional"))
    )
    (net (code "191") (name "/TS_RESET_N") (class "Default")
      (node (ref "J8") (pin "8") (pinfunction "8_8") (pintype "bidirectional"))
      (node (ref "TP6") (pin "TP") (pinfunction "TP_TP") (pintype "input"))
      (node (ref "U13") (pin "C2") (pinfunction "1Y_C2") (pintype "bidirectional"))
    )
    (net (code "192") (name "/TXD") (class "Default")
      (node (ref "JP1") (pin "3") (pinfunction "3_3") (pintype "passive"))
      (node (ref "U12") (pin "C1") (pinfunction "2Y_C1") (pintype "bidirectional"))
    )
    (net (code "193") (name "/UART0_CTSN") (class "Default")
      (node (ref "JP4") (pin "16") (pinfunction "16_16") (pintype "passive"))
      (node (ref "U1") (pin "A9") (pinfunction "UART0_CTSN_A9") (pintype "bidirectional"))
    )
    (net (code "194") (name "/UART0_RTSN") (class "Default")
      (node (ref "JP5") (pin "16") (pinfunction "16_16") (pintype "passive"))
      (node (ref "U1") (pin "B9") (pinfunction "UART0_RTSN_B9") (pintype "bidirectional"))
    )
    (net (code "195") (name "/UART0_RXD") (class "Default")
      (node (ref "U1") (pin "A10") (pinfunction "UART0_RXD_A10") (pintype "bidirectional"))
      (node (ref "U12") (pin "C2") (pinfunction "1Y_C2") (pintype "bidirectional"))
    )
    (net (code "196") (name "/UART0_TXD") (class "Default")
      (node (ref "U1") (pin "B10") (pinfunction "UART0_TXD_B10") (pintype "bidirectional"))
      (node (ref "U12") (pin "D2") (pinfunction "2A_D2") (pintype "bidirectional"))
    )
    (net (code "197") (name "/USB0_DM") (class "Default")
      (node (ref "J5") (pin "A7") (pinfunction "DN1_A7") (pintype "bidirectional"))
      (node (ref "J5") (pin "B7") (pinfunction "DN2_B7") (pintype "bidirectional"))
      (node (ref "U1") (pin "U12") (pinfunction "USB0_DM_U12") (pintype "bidirectional"))
      (node (ref "U9") (pin "2") (pinfunction "D-_2") (pintype "passive"))
    )
    (net (code "198") (name "/USB0_DP") (class "Default")
      (node (ref "J5") (pin "A6") (pinfunction "DP1_A6") (pintype "bidirectional"))
      (node (ref "J5") (pin "B6") (pinfunction "DP2_B6") (pintype "bidirectional"))
      (node (ref "U1") (pin "V12") (pinfunction "USB0_DP_V12") (pintype "bidirectional"))
      (node (ref "U9") (pin "1") (pinfunction "D+_1") (pintype "passive"))
    )
    (net (code "199") (name "/USB0_DRVVBUS") (class "Default")
      (node (ref "J4") (pin "11") (pinfunction "11_11") (pintype "passive"))
      (node (ref "U1") (pin "C19") (pinfunction "USB0_DRVVBUS_C19") (pintype "bidirectional"))
    )
    (net (code "200") (name "/USB0_VBUS") (class "Default")
      (node (ref "R62") (pin "1") (pinfunction "1_1") (pintype "passive"))
      (node (ref "R63") (pin "1") (pinfunction "1_1") (pintype "passive"))
      (node (ref "U1") (pin "V11") (pinfunction "USB0_VBUS_V11") (pintype "bidirectional"))
    )
    (net (code "201") (name "/USB1_DM") (class "Default")
      (node (ref "J6") (pin "A7") (pinfunction "DN1_A7") (pintype "bidirectional"))
      (node (ref "J6") (pin "B7") (pinfunction "DN2_B7") (pintype "bidirectional"))
      (node (ref "U1") (pin "U10") (pinfunction "USB1_DM_U10") (pintype "bidirectional"))
      (node (ref "U2") (pin "2") (pinfunction "D-_2") (pintype "passive"))
    )
    (net (code "202") (name "/USB1_DP") (class "Default")
      (node (ref "J6") (pin "A6") (pinfunction "DP1_A6") (pintype "bidirectional"))
      (node (ref "J6") (pin "B6") (pinfunction "DP2_B6") (pintype "bidirectional"))
      (node (ref "U1") (pin "V10") (pinfunction "USB1_DP_V10") (pintype "bidirectional"))
      (node (ref "U2") (pin "1") (pinfunction "D+_1") (pintype "passive"))
    )
    (net (code "203") (name "/USB1_DRVVBUS") (class "Default")
      (node (ref "J4") (pin "12") (pinfunction "12_12") (pintype "passive"))
      (node (ref "U1") (pin "D19") (pinfunction "USB1_DRVVBUS_D19") (pintype "bidirectional"))
    )
    (net (code "204") (name "/USB1_VBUS") (class "Default")
      (node (ref "R4") (pin "1") (pinfunction "1_1") (pintype "passive"))
      (node (ref "R5") (pin "1") (pinfunction "1_1") (pintype "passive"))
      (node (ref "U1") (pin "U11") (pinfunction "USB1_VBUS_U11") (pintype "bidirectional"))
    )
    (net (code "205") (name "/VBUS") (class "Default")
      (node (ref "C50") (pin "1") (pinfunction "1_1") (pintype "passive"))
      (node (ref "C60") (pin "1") (pinfunction "1_1") (pintype "passive"))
      (node (ref "D8") (pin "A") (pinfunction "A_A") (pintype "passive"))
      (node (ref "J5") (pin "A4_B9") (pinfunction "VBUS/A4/B9_A4_B9") (pintype "power_in"))
      (node (ref "J5") (pin "B4_A9") (pinfunction "VBUS/A9/B4_B4_A9") (pintype "power_in"))
      (node (ref "U9") (pin "6") (pinfunction "VBUS_6") (pintype "passive"))
    )
    (net (code "206") (name "/VDD_SD") (class "Default")
      (node (ref "C57") (pin "1") (pinfunction "1_1") (pintype "passive"))
      (node (ref "C58") (pin "1") (pinfunction "1_1") (pintype "passive"))
      (node (ref "U10") (pin "5") (pinfunction "QOD_5") (pintype "output"))
      (node (ref "U10") (pin "6") (pinfunction "VOUT_6") (pintype "output"))
      (node (ref "X1") (pin "PIN4") (pinfunction "VDD_PIN4") (pintype "power_in"))
    )
    (net (code "207") (name "/VIN-3P3") (class "Default")
      (node (ref "C30") (pin "2") (pinfunction "2_2") (pintype "passive"))
      (node (ref "C31") (pin "1") (pinfunction "1_1") (pintype "passive"))
      (node (ref "C32") (pin "1") (pinfunction "1_1") (pintype "passive"))
      (node (ref "C33") (pin "1") (pinfunction "1_1") (pintype "passive"))
      (node (ref "C39") (pin "1") (pinfunction "1_1") (pintype "passive"))
      (node (ref "C40") (pin "1") (pinfunction "1_1") (pintype "passive"))
      (node (ref "C48") (pin "1") (pinfunction "1_1") (pintype "passive"))
      (node (ref "C51") (pin "1") (pinfunction "1_1") (pintype "passive"))
      (node (ref "C52") (pin "1") (pinfunction "1_1") (pintype "passive"))
      (node (ref "L1") (pin "2") (pinfunction "2_2") (pintype "passive"))
      (node (ref "R22") (pin "2") (pinfunction "2_2") (pintype "passive"))
      (node (ref "R73") (pin "2") (pinfunction "2_2") (pintype "passive"))
      (node (ref "R9") (pin "1") (pinfunction "1_1") (pintype "passive"))
      (node (ref "U5") (pin "1") (pinfunction "VIN_1") (pintype "input"))
      (node (ref "U5") (pin "2") (pinfunction "VIN_2") (pintype "input"))
      (node (ref "U5") (pin "4") (pinfunction "VBIAS_4") (pintype "input"))
      (node (ref "U6") (pin "13") (pinfunction "VSYS_13") (pintype "bidirectional"))
      (node (ref "U6") (pin "22") (pinfunction "PVIN_LDO34_22") (pintype "bidirectional"))
      (node (ref "U6") (pin "26") (pinfunction "PVIN_B3_26") (pintype "bidirectional"))
      (node (ref "U6") (pin "30") (pinfunction "PVIN_B2_30") (pintype "bidirectional"))
      (node (ref "U6") (pin "4") (pinfunction "PVIN_B1_1_4") (pintype "bidirectional"))
      (node (ref "U6") (pin "5") (pinfunction "PVIN_B1_2_5") (pintype "bidirectional"))
      (node (ref "U6") (pin "6") (pinfunction "PVIN_LDO1_6") (pintype "bidirectional"))
    )
    (net (code "208") (name "/VIN-3P3-LS") (class "Default")
      (node (ref "C22") (pin "1") (pinfunction "1_1") (pintype "passive"))
      (node (ref "C26") (pin "1") (pinfunction "1_1") (pintype "passive"))
      (node (ref "C29") (pin "1") (pinfunction "1_1") (pintype "passive"))
      (node (ref "C34") (pin "1") (pinfunction "1_1") (pintype "passive"))
      (node (ref "C35") (pin "1") (pinfunction "1_1") (pintype "passive"))
      (node (ref "C36") (pin "1") (pinfunction "1_1") (pintype "passive"))
      (node (ref "C37") (pin "1") (pinfunction "1_1") (pintype "passive"))
      (node (ref "C6") (pin "1") (pinfunction "1_1") (pintype "passive"))
      (node (ref "C61") (pin "1") (pinfunction "1_1") (pintype "passive"))
      (node (ref "C63") (pin "1") (pinfunction "1_1") (pintype "passive"))
      (node (ref "J4") (pin "15") (pinfunction "15_15") (pintype "passive"))
      (node (ref "J8") (pin "1") (pinfunction "1_1") (pintype "bidirectional"))
      (node (ref "JP2") (pin "2") (pinfunction "2_2") (pintype "passive"))
      (node (ref "JP3") (pin "7") (pinfunction "7_7") (pintype "passive"))
      (node (ref "JP4") (pin "34") (pinfunction "34_34") (pintype "passive"))
      (node (ref "R10") (pin "2") (pinfunction "2_2") (pintype "passive"))
      (node (ref "R11") (pin "2") (pinfunction "2_2") (pintype "passive"))
      (node (ref "R12") (pin "2") (pinfunction "2_2") (pintype "passive"))
      (node (ref "R13") (pin "2") (pinfunction "2_2") (pintype "passive"))
      (node (ref "R16") (pin "2") (pinfunction "2_2") (pintype "passive"))
      (node (ref "R17") (pin "2") (pinfunction "2_2") (pintype "passive"))
      (node (ref "R18") (pin "2") (pinfunction "2_2") (pintype "passive"))
      (node (ref "R19") (pin "2") (pinfunction "2_2") (pintype "passive"))
      (node (ref "R20") (pin "2") (pinfunction "2_2") (pintype "passive"))
      (node (ref "R21") (pin "2") (pinfunction "2_2") (pintype "passive"))
      (node (ref "R23") (pin "2") (pinfunction "2_2") (pintype "passive"))
      (node (ref "R25") (pin "2") (pinfunction "2_2") (pintype "passive"))
      (node (ref "R28") (pin "2") (pinfunction "2_2") (pintype "passive"))
      (node (ref "R30") (pin "2") (pinfunction "2_2") (pintype "passive"))
      (node (ref "R31") (pin "2") (pinfunction "2_2") (pintype "passive"))
      (node (ref "R32") (pin "2") (pinfunction "2_2") (pintype "passive"))
      (node (ref "R38") (pin "2") (pinfunction "2_2") (pintype "passive"))
      (node (ref "R48") (pin "2") (pinfunction "2_2") (pintype "passive"))
      (node (ref "R49") (pin "2") (pinfunction "2_2") (pintype "passive"))
      (node (ref "R51") (pin "2") (pinfunction "2_2") (pintype "passive"))
      (node (ref "R52") (pin "2") (pinfunction "2_2") (pintype "passive"))
      (node (ref "R53") (pin "2") (pinfunction "2_2") (pintype "passive"))
      (node (ref "R54") (pin "1") (pinfunction "1_1") (pintype "passive"))
      (node (ref "R57") (pin "2") (pinfunction "2_2") (pintype "passive"))
      (node (ref "R64") (pin "2") (pinfunction "2_2") (pintype "passive"))
      (node (ref "R65") (pin "2") (pinfunction "2_2") (pintype "passive"))
      (node (ref "R66") (pin "2") (pinfunction "2_2") (pintype "passive"))
      (node (ref "R67") (pin "2") (pinfunction "2_2") (pintype "passive"))
      (node (ref "R68") (pin "2") (pinfunction "2_2") (pintype "passive"))
      (node (ref "R69") (pin "2") (pinfunction "2_2") (pintype "passive"))
      (node (ref "R7") (pin "2") (pinfunction "2_2") (pintype "passive"))
      (node (ref "R70") (pin "2") (pinfunction "2_2") (pintype "passive"))
      (node (ref "TC1") (pin "1") (pinfunction "1_1") (pintype "passive"))
      (node (ref "U1") (pin "B15") (pinfunction "VMON_3P3_SOC_B15") (pintype "bidirectional"))
      (node (ref "U1") (pin "F11") (pinfunction "VDDSHV_CANUART_F11") (pintype "bidirectional"))
      (node (ref "U1") (pin "F12") (pinfunction "VDDSHV_MCU_F12") (pintype "bidirectional"))
      (node (ref "U1") (pin "G10") (pinfunction "VDDSHV_CANUART_G10") (pintype "bidirectional"))
      (node (ref "U1") (pin "G11") (pinfunction "VDDSHV_MCU_G11") (pintype "bidirectional"))
      (node (ref "U1") (pin "H21") (pinfunction "VDDSHV6_H21") (pintype "bidirectional"))
      (node (ref "U1") (pin "H22") (pinfunction "VDDSHV6_H22") (pintype "bidirectional"))
      (node (ref "U1") (pin "J21") (pinfunction "VDDSHV0_J21") (pintype "bidirectional"))
      (node (ref "U1") (pin "J22") (pinfunction "VDDSHV0_J22") (pintype "bidirectional"))
      (node (ref "U1") (pin "K21") (pinfunction "VDDSHV1_K21") (pintype "bidirectional"))
      (node (ref "U1") (pin "K22") (pinfunction "VDDSHV1_K22") (pintype "bidirectional"))
      (node (ref "U1") (pin "L21") (pinfunction "VDDSHV3_L21") (pintype "bidirectional"))
      (node (ref "U1") (pin "L22") (pinfunction "VDDSHV3_L22") (pintype "bidirectional"))
      (node (ref "U1") (pin "M21") (pinfunction "VDDSHV2_M21") (pintype "bidirectional"))
      (node (ref "U1") (pin "M22") (pinfunction "VDDSHV2_M22") (pintype "bidirectional"))
      (node (ref "U1") (pin "N11") (pinfunction "VDDSHV4_N11") (pintype "bidirectional"))
      (node (ref "U1") (pin "N7") (pinfunction "VDDA_3P3_USB_N7") (pintype "bidirectional"))
      (node (ref "U1") (pin "P10") (pinfunction "VDDSHV4_P10") (pintype "bidirectional"))
      (node (ref "U10") (pin "1") (pinfunction "VIN_1") (pintype "input"))
      (node (ref "U11") (pin "6") (pinfunction "VCC_6") (pintype "power_in"))
      (node (ref "U12") (pin "A2") (pinfunction "VCC_A2") (pintype "bidirectional"))
      (node (ref "U12") (pin "B2") (pinfunction "2OE_B2") (pintype "bidirectional"))
      (node (ref "U13") (pin "A2") (pinfunction "VCC_A2") (pintype "bidirectional"))
      (node (ref "U13") (pin "B2") (pinfunction "2OE_B2") (pintype "bidirectional"))
      (node (ref "U14") (pin "4") (pinfunction "IN_4") (pintype "bidirectional"))
      (node (ref "U4") (pin "4") (pinfunction "VCC_4") (pintype "bidirectional"))
      (node (ref "U5") (pin "7") (pinfunction "VOUT_7") (pintype "output"))
      (node (ref "U5") (pin "8") (pinfunction "VOUT_8") (pintype "output"))
      (node (ref "U7") (pin "1") (pinfunction "VA_1") (pintype "power_in"))
      (node (ref "U8") (pin "1") (pinfunction "VA_1") (pintype "power_in"))
    )
    (net (code "209") (name "/VIN-5P0") (class "Default")
      (node (ref "C24") (pin "1") (pinfunction "1_1") (pintype "passive"))
      (node (ref "C25") (pin "+") (pinfunction "+_+") (pintype "passive"))
      (node (ref "C27") (pin "1") (pinfunction "1_1") (pintype "passive"))
      (node (ref "C55") (pin "1") (pinfunction "1_1") (pintype "passive"))
      (node (ref "C56") (pin "1") (pinfunction "1_1") (pintype "passive"))
      (node (ref "C59") (pin "1") (pinfunction "1_1") (pintype "passive"))
      (node (ref "D8") (pin "C") (pinfunction "C_C") (pintype "passive"))
      (node (ref "J6") (pin "A4") (pinfunction "VBUS_A4") (pintype "power_in"))
      (node (ref "J6") (pin "A9") (pinfunction "VBUS_A9") (pintype "power_in"))
      (node (ref "J6") (pin "B4") (pinfunction "VBUS_B4") (pintype "power_in"))
      (node (ref "J6") (pin "B9") (pinfunction "VBUS_B9") (pintype "power_in"))
      (node (ref "JP2") (pin "1") (pinfunction "1_1") (pintype "passive"))
      (node (ref "JP3") (pin "34") (pinfunction "34_34") (pintype "passive"))
      (node (ref "JP4") (pin "7") (pinfunction "7_7") (pintype "passive"))
      (node (ref "R2") (pin "2") (pinfunction "2_2") (pintype "passive"))
      (node (ref "R5") (pin "2") (pinfunction "2_2") (pintype "passive"))
      (node (ref "R62") (pin "2") (pinfunction "2_2") (pintype "passive"))
      (node (ref "R71") (pin "2") (pinfunction "2_2") (pintype "passive"))
      (node (ref "R72") (pin "2") (pinfunction "2_2") (pintype "passive"))
      (node (ref "U2") (pin "6") (pinfunction "VBUS_6") (pintype "passive"))
      (node (ref "U3") (pin "1") (pinfunction "EN_1") (pintype "bidirectional"))
      (node (ref "U3") (pin "6") (pinfunction "VIN_6") (pintype "bidirectional"))
    )
    (net (code "210") (name "/VMON_ER_SYS") (class "Default")
      (node (ref "R1") (pin "2") (pinfunction "2_2") (pintype "passive"))
      (node (ref "R2") (pin "1") (pinfunction "1_1") (pintype "passive"))
      (node (ref "U1") (pin "A15") (pinfunction "VMON_VSYS_A15") (pintype "bidirectional"))
    )
    (net (code "211") (name "/VOUT0_DATA0") (class "Default")
      (node (ref "JP2") (pin "21") (pinfunction "21_21") (pintype "passive"))
      (node (ref "U1") (pin "P26") (pinfunction "VOUT0_DATA0_P26") (pintype "bidirectional"))
    )
    (net (code "212") (name "/VOUT0_DATA1") (class "Default")
      (node (ref "JP3") (pin "21") (pinfunction "21_21") (pintype "passive"))
      (node (ref "U1") (pin "N25") (pinfunction "VOUT0_DATA1_N25") (pintype "bidirectional"))
    )
    (net (code "213") (name "/VOUT0_DATA2") (class "Default")
      (node (ref "JP2") (pin "22") (pinfunction "22_22") (pintype "passive"))
      (node (ref "U1") (pin "N26") (pinfunction "VOUT0_DATA2_N26") (pintype "bidirectional"))
    )
    (net (code "214") (name "/VOUT0_DATA3") (class "Default")
      (node (ref "JP3") (pin "22") (pinfunction "22_22") (pintype "passive"))
      (node (ref "U1") (pin "M25") (pinfunction "VOUT0_DATA3_M25") (pintype "bidirectional"))
    )
    (net (code "215") (name "/VOUT0_DATA4") (class "Default")
      (node (ref "JP2") (pin "23") (pinfunction "23_23") (pintype "passive"))
      (node (ref "U1") (pin "M26") (pinfunction "VOUT0_DATA4_M26") (pintype "bidirectional"))
    )
    (net (code "216") (name "/VOUT0_DATA5") (class "Default")
      (node (ref "JP3") (pin "23") (pinfunction "23_23") (pintype "passive"))
      (node (ref "U1") (pin "U27") (pinfunction "VOUT0_DATA5_U27") (pintype "bidirectional"))
    )
    (net (code "217") (name "/VOUT0_DATA6") (class "Default")
      (node (ref "JP2") (pin "24") (pinfunction "24_24") (pintype "passive"))
      (node (ref "U1") (pin "T27") (pinfunction "VOUT0_DATA6_T27") (pintype "bidirectional"))
    )
    (net (code "218") (name "/VOUT0_DATA7") (class "Default")
      (node (ref "JP3") (pin "24") (pinfunction "24_24") (pintype "passive"))
      (node (ref "U1") (pin "T28") (pinfunction "VOUT0_DATA7_T28") (pintype "bidirectional"))
    )
    (net (code "219") (name "/VOUT0_DATA8") (class "Default")
      (node (ref "JP2") (pin "25") (pinfunction "25_25") (pintype "passive"))
      (node (ref "U1") (pin "R27") (pinfunction "VOUT0_DATA8_R27") (pintype "bidirectional"))
    )
    (net (code "220") (name "/VOUT0_DATA9") (class "Default")
      (node (ref "JP3") (pin "25") (pinfunction "25_25") (pintype "passive"))
      (node (ref "U1") (pin "R28") (pinfunction "VOUT0_DATA9_R28") (pintype "bidirectional"))
    )
    (net (code "221") (name "/VOUT0_DATA10") (class "Default")
      (node (ref "JP2") (pin "26") (pinfunction "26_26") (pintype "passive"))
      (node (ref "U1") (pin "P27") (pinfunction "VOUT0_DATA10_P27") (pintype "bidirectional"))
    )
    (net (code "222") (name "/VOUT0_DATA11") (class "Default")
      (node (ref "JP3") (pin "26") (pinfunction "26_26") (pintype "passive"))
      (node (ref "U1") (pin "P28") (pinfunction "VOUT0_DATA11_P28") (pintype "bidirectional"))
    )
    (net (code "223") (name "/VOUT0_DATA12") (class "Default")
      (node (ref "JP2") (pin "27") (pinfunction "27_27") (pintype "passive"))
      (node (ref "U1") (pin "N27") (pinfunction "VOUT0_DATA12_N27") (pintype "bidirectional"))
    )
    (net (code "224") (name "/VOUT0_DATA13") (class "Default")
      (node (ref "JP3") (pin "27") (pinfunction "27_27") (pintype "passive"))
      (node (ref "U1") (pin "N28") (pinfunction "VOUT0_DATA13_N28") (pintype "bidirectional"))
    )
    (net (code "225") (name "/VOUT0_DATA14") (class "Default")
      (node (ref "JP2") (pin "28") (pinfunction "28_28") (pintype "passive"))
      (node (ref "U1") (pin "M27") (pinfunction "VOUT0_DATA14_M27") (pintype "bidirectional"))
    )
    (net (code "226") (name "/VOUT0_DATA15") (class "Default")
      (node (ref "JP3") (pin "28") (pinfunction "28_28") (pintype "passive"))
      (node (ref "U1") (pin "M28") (pinfunction "VOUT0_DATA15_M28") (pintype "bidirectional"))
    )
    (net (code "227") (name "/VOUT0_DE") (class "Default")
      (node (ref "JP2") (pin "19") (pinfunction "19_19") (pintype "passive"))
      (node (ref "U1") (pin "R25") (pinfunction "VOUT0_DE_R25") (pintype "bidirectional"))
    )
    (net (code "228") (name "/VOUT0_HSYNC") (class "Default")
      (node (ref "JP3") (pin "20") (pinfunction "20_20") (pintype "passive"))
      (node (ref "U1") (pin "P25") (pinfunction "VOUT0_HSYNC_P25") (pintype "bidirectional"))
    )
    (net (code "229") (name "/VOUT0_PCLK") (class "Default")
      (node (ref "JP3") (pin "19") (pinfunction "19_19") (pintype "passive"))
      (node (ref "U1") (pin "T26") (pinfunction "VOUT0_PCLK_T26") (pintype "bidirectional"))
    )
    (net (code "230") (name "/VOUT0_VSYNC") (class "Default")
      (node (ref "JP2") (pin "20") (pinfunction "20_20") (pintype "passive"))
      (node (ref "U1") (pin "R26") (pinfunction "VOUT0_VSYNC_R26") (pintype "bidirectional"))
    )
    (net (code "231") (name "/VPP") (class "Default")
      (node (ref "C62") (pin "1") (pinfunction "1_1") (pintype "passive"))
      (node (ref "U1") (pin "C16") (pinfunction "VPP_C16") (pintype "bidirectional"))
      (node (ref "U14") (pin "1") (pinfunction "OUT_1") (pintype "bidirectional"))
    )
    (net (code "232") (name "/WKUP_CLKOUT0") (class "Default")
      (node (ref "JP5") (pin "15") (pinfunction "15_15") (pintype "passive"))
      (node (ref "U1") (pin "C7") (pinfunction "WKUP_CLKOUT0_C7") (pintype "bidirectional"))
    )
    (net (code "233") (name "/WKUP_I2C0_SCL") (class "Default")
      (node (ref "J4") (pin "13") (pinfunction "13_13") (pintype "passive"))
      (node (ref "R64") (pin "1") (pinfunction "1_1") (pintype "passive"))
      (node (ref "U1") (pin "A8") (pinfunction "WKUP_I2C0_SCL_A8") (pintype "bidirectional"))
    )
    (net (code "234") (name "/WKUP_I2C0_SDA") (class "Default")
      (node (ref "J4") (pin "14") (pinfunction "14_14") (pintype "passive"))
      (node (ref "R12") (pin "1") (pinfunction "1_1") (pintype "passive"))
      (node (ref "U1") (pin "B8") (pinfunction "WKUP_I2C0_SDA_B8") (pintype "bidirectional"))
    )
    (net (code "235") (name "/WKUP_LFOSC0_XI") (class "Default")
      (node (ref "U1") (pin "H1") (pinfunction "WKUP_LFOSC0_XI_H1") (pintype "bidirectional"))
      (node (ref "Y1") (pin "3") (pinfunction "OUT_3") (pintype "bidirectional"))
    )
    (net (code "236") (name "/WKUP_UART0_CTSN") (class "Default")
      (node (ref "JP5") (pin "6") (pinfunction "6_6") (pintype "passive"))
      (node (ref "U1") (pin "D1") (pinfunction "WKUP_UART0_CTSN_D1") (pintype "bidirectional"))
    )
    (net (code "237") (name "/WKUP_UART0_RTSN") (class "Default")
      (node (ref "JP5") (pin "7") (pinfunction "7_7") (pintype "passive"))
      (node (ref "U1") (pin "D2") (pinfunction "WKUP_UART0_RTSN_D2") (pintype "bidirectional"))
    )
    (net (code "238") (name "/WKUP_UART0_RXD") (class "Default")
      (node (ref "JP5") (pin "9") (pinfunction "9_9") (pintype "passive"))
      (node (ref "U1") (pin "C2") (pinfunction "WKUP_UART0_RXD_C2") (pintype "bidirectional"))
    )
    (net (code "239") (name "/WKUP_UART0_TXD") (class "Default")
      (node (ref "JP5") (pin "8") (pinfunction "8_8") (pintype "passive"))
      (node (ref "U1") (pin "C1") (pinfunction "WKUP_UART0_TXD_C1") (pintype "bidirectional"))
    )
    (net (code "240") (name "GND") (class "Default")
      (node (ref "C1") (pin "2") (pinfunction "2_2") (pintype "passive"))
      (node (ref "C10") (pin "2") (pinfunction "2_2") (pintype "passive"))
      (node (ref "C11") (pin "2") (pinfunction "2_2") (pintype "passive"))
      (node (ref "C12") (pin "2") (pinfunction "2_2") (pintype "passive"))
      (node (ref "C13") (pin "2") (pinfunction "2_2") (pintype "passive"))
      (node (ref "C14") (pin "2") (pinfunction "2_2") (pintype "passive"))
      (node (ref "C15") (pin "2") (pinfunction "2_2") (pintype "passive"))
      (node (ref "C16") (pin "2") (pinfunction "2_2") (pintype "passive"))
      (node (ref "C17") (pin "2") (pinfunction "2_2") (pintype "passive"))
      (node (ref "C18") (pin "2") (pinfunction "2_2") (pintype "passive"))
      (node (ref "C19") (pin "2") (pinfunction "2_2") (pintype "passive"))
      (node (ref "C2") (pin "2") (pinfunction "2_2") (pintype "passive"))
      (node (ref "C20") (pin "2") (pinfunction "2_2") (pintype "passive"))
      (node (ref "C21") (pin "2") (pinfunction "2_2") (pintype "passive"))
      (node (ref "C22") (pin "2") (pinfunction "2_2") (pintype "passive"))
      (node (ref "C23") (pin "2") (pinfunction "2_2") (pintype "passive"))
      (node (ref "C24") (pin "2") (pinfunction "2_2") (pintype "passive"))
      (node (ref "C25") (pin "-") (pinfunction "-_-") (pintype "passive"))
      (node (ref "C26") (pin "2") (pinfunction "2_2") (pintype "passive"))
      (node (ref "C27") (pin "2") (pinfunction "2_2") (pintype "passive"))
      (node (ref "C28") (pin "2") (pinfunction "2_2") (pintype "passive"))
      (node (ref "C29") (pin "2") (pinfunction "2_2") (pintype "passive"))
      (node (ref "C3") (pin "2") (pinfunction "2_2") (pintype "passive"))
      (node (ref "C31") (pin "2") (pinfunction "2_2") (pintype "passive"))
      (node (ref "C32") (pin "2") (pinfunction "2_2") (pintype "passive"))
      (node (ref "C33") (pin "2") (pinfunction "2_2") (pintype "passive"))
      (node (ref "C34") (pin "2") (pinfunction "2_2") (pintype "passive"))
      (node (ref "C35") (pin "2") (pinfunction "2_2") (pintype "passive"))
      (node (ref "C36") (pin "2") (pinfunction "2_2") (pintype "passive"))
      (node (ref "C37") (pin "2") (pinfunction "2_2") (pintype "passive"))
      (node (ref "C38") (pin "2") (pinfunction "2_2") (pintype "passive"))
      (node (ref "C39") (pin "2") (pinfunction "2_2") (pintype "passive"))
      (node (ref "C4") (pin "2") (pinfunction "2_2") (pintype "passive"))
      (node (ref "C40") (pin "2") (pinfunction "2_2") (pintype "passive"))
      (node (ref "C41") (pin "2") (pinfunction "2_2") (pintype "passive"))
      (node (ref "C42") (pin "2") (pinfunction "2_2") (pintype "passive"))
      (node (ref "C43") (pin "2") (pinfunction "2_2") (pintype "passive"))
      (node (ref "C44") (pin "2") (pinfunction "2_2") (pintype "passive"))
      (node (ref "C45") (pin "2") (pinfunction "2_2") (pintype "passive"))
      (node (ref "C46") (pin "2") (pinfunction "2_2") (pintype "passive"))
      (node (ref "C47") (pin "2") (pinfunction "2_2") (pintype "passive"))
      (node (ref "C48") (pin "2") (pinfunction "2_2") (pintype "passive"))
      (node (ref "C49") (pin "2") (pinfunction "2_2") (pintype "passive"))
      (node (ref "C5") (pin "2") (pinfunction "2_2") (pintype "passive"))
      (node (ref "C50") (pin "2") (pinfunction "2_2") (pintype "passive"))
      (node (ref "C51") (pin "2") (pinfunction "2_2") (pintype "passive"))
      (node (ref "C52") (pin "2") (pinfunction "2_2") (pintype "passive"))
      (node (ref "C53") (pin "2") (pinfunction "2_2") (pintype "passive"))
      (node (ref "C54") (pin "2") (pinfunction "2_2") (pintype "passive"))
      (node (ref "C55") (pin "2") (pinfunction "2_2") (pintype "passive"))
      (node (ref "C56") (pin "2") (pinfunction "2_2") (pintype "passive"))
      (node (ref "C57") (pin "2") (pinfunction "2_2") (pintype "passive"))
      (node (ref "C58") (pin "2") (pinfunction "2_2") (pintype "passive"))
      (node (ref "C59") (pin "2") (pinfunction "2_2") (pintype "passive"))
      (node (ref "C6") (pin "2") (pinfunction "2_2") (pintype "passive"))
      (node (ref "C60") (pin "2") (pinfunction "2_2") (pintype "passive"))
      (node (ref "C61") (pin "2") (pinfunction "2_2") (pintype "passive"))
      (node (ref "C62") (pin "2") (pinfunction "2_2") (pintype "passive"))
      (node (ref "C63") (pin "2") (pinfunction "2_2") (pintype "passive"))
      (node (ref "C7") (pin "2") (pinfunction "2_2") (pintype "passive"))
      (node (ref "C8") (pin "2") (pinfunction "2_2") (pintype "passive"))
      (node (ref "C9") (pin "2") (pinfunction "2_2") (pintype "passive"))
      (node (ref "D1") (pin "2") (pinfunction "C_2") (pintype "passive"))
      (node (ref "D2") (pin "2") (pinfunction "C_2") (pintype "passive"))
      (node (ref "D3") (pin "2") (pinfunction "C_2") (pintype "passive"))
      (node (ref "D4") (pin "2") (pinfunction "C_2") (pintype "passive"))
      (node (ref "D5") (pin "2") (pinfunction "C_2") (pintype "passive"))
      (node (ref "J2") (pin "1") (pinfunction "1_1") (pintype "bidirectional"))
      (node (ref "J4") (pin "1") (pinfunction "1_1") (pintype "passive"))
      (node (ref "J4") (pin "10") (pinfunction "10_10") (pintype "passive"))
      (node (ref "J4") (pin "4") (pinfunction "4_4") (pintype "passive"))
      (node (ref "J4") (pin "7") (pinfunction "7_7") (pintype "passive"))
      (node (ref "J5") (pin "A1_B12") (pinfunction "GND/A1/B12_A1_B12") (pintype "power_in"))
      (node (ref "J5") (pin "B1_A12") (pinfunction "GND/A12/B1_B1_A12") (pintype "power_in"))
      (node (ref "J5") (pin "SH1_B") (pinfunction "SH1_SH1_B") (pintype "power_in"))
      (node (ref "J5") (pin "SH1_T") (pinfunction "SH1_SH1_T") (pintype "power_in"))
      (node (ref "J5") (pin "SH2_B") (pinfunction "SH2_SH2_B") (pintype "power_in"))
      (node (ref "J5") (pin "SH2_T") (pinfunction "SH2_SH2_T") (pintype "power_in"))
      (node (ref "J5") (pin "SH3_B") (pinfunction "SH3_SH3_B") (pintype "power_in"))
      (node (ref "J5") (pin "SH3_T") (pinfunction "SH3_SH3_T") (pintype "power_in"))
      (node (ref "J5") (pin "SH4_B") (pinfunction "SH4_SH4_B") (pintype "power_in"))
      (node (ref "J5") (pin "SH4_T") (pinfunction "SH4_SH4_T") (pintype "power_in"))
      (node (ref "J6") (pin "A1") (pinfunction "GND_A1") (pintype "power_in"))
      (node (ref "J6") (pin "A12") (pinfunction "GND_A12") (pintype "power_in"))
      (node (ref "J6") (pin "B1") (pinfunction "GND_B1") (pintype "power_in"))
      (node (ref "J6") (pin "B12") (pinfunction "GND_B12") (pintype "power_in"))
      (node (ref "J6") (pin "SH_B_1") (pinfunction "SH1_SH_B_1") (pintype "passive"))
      (node (ref "J6") (pin "SH_B_2") (pinfunction "SH2_SH_B_2") (pintype "passive"))
      (node (ref "J6") (pin "SH_B_3") (pinfunction "SH3_SH_B_3") (pintype "passive"))
      (node (ref "J6") (pin "SH_B_4") (pinfunction "SH4_SH_B_4") (pintype "passive"))
      (node (ref "J6") (pin "SH_T_1") (pinfunction "SH1_SH_T_1") (pintype "passive"))
      (node (ref "J6") (pin "SH_T_2") (pinfunction "SH2_SH_T_2") (pintype "passive"))
      (node (ref "J6") (pin "SH_T_3") (pinfunction "SH3_SH_T_3") (pintype "passive"))
      (node (ref "J6") (pin "SH_T_4") (pinfunction "SH4_SH_T_4") (pintype "passive"))
      (node (ref "J8") (pin "10") (pinfunction "10_10") (pintype "bidirectional"))
      (node (ref "J8") (pin "13") (pinfunction "13_13") (pintype "bidirectional"))
      (node (ref "J8") (pin "16") (pinfunction "16_16") (pintype "bidirectional"))
      (node (ref "J8") (pin "19") (pinfunction "19_19") (pintype "bidirectional"))
      (node (ref "J8") (pin "22") (pinfunction "22_22") (pintype "bidirectional"))
      (node (ref "J8") (pin "25") (pinfunction "25_25") (pintype "bidirectional"))
      (node (ref "J8") (pin "28") (pinfunction "28_28") (pintype "bidirectional"))
      (node (ref "J8") (pin "31") (pinfunction "31_31") (pintype "bidirectional"))
      (node (ref "J8") (pin "34") (pinfunction "34_34") (pintype "bidirectional"))
      (node (ref "J8") (pin "37") (pinfunction "37_37") (pintype "bidirectional"))
      (node (ref "J8") (pin "40") (pinfunction "40_40") (pintype "bidirectional"))
      (node (ref "J8") (pin "6") (pinfunction "6_6") (pintype "bidirectional"))
      (node (ref "J8") (pin "7") (pinfunction "7_7") (pintype "bidirectional"))
      (node (ref "J8") (pin "S1") (pinfunction "PAD1_S1") (pintype "bidirectional"))
      (node (ref "J8") (pin "S2") (pinfunction "PAD2_S2") (pintype "bidirectional"))
      (node (ref "JP1") (pin "1") (pinfunction "1_1") (pintype "passive"))
      (node (ref "JP2") (pin "33") (pinfunction "33_33") (pintype "passive"))
      (node (ref "JP2") (pin "40") (pinfunction "40_40") (pintype "passive"))
      (node (ref "JP3") (pin "33") (pinfunction "33_33") (pintype "passive"))
      (node (ref "JP3") (pin "8") (pinfunction "8_8") (pintype "passive"))
      (node (ref "JP4") (pin "33") (pinfunction "33_33") (pintype "passive"))
      (node (ref "JP4") (pin "8") (pinfunction "8_8") (pintype "passive"))
      (node (ref "JP5") (pin "1") (pinfunction "1_1") (pintype "passive"))
      (node (ref "JP5") (pin "30") (pinfunction "30_30") (pintype "passive"))
      (node (ref "JP5") (pin "40") (pinfunction "40_40") (pintype "passive"))
      (node (ref "R1") (pin "1") (pinfunction "1_1") (pintype "passive"))
      (node (ref "R14") (pin "1") (pinfunction "1_1") (pintype "passive"))
      (node (ref "R15") (pin "1") (pinfunction "1_1") (pintype "passive"))
      (node (ref "R26") (pin "2") (pinfunction "2_2") (pintype "passive"))
      (node (ref "R27") (pin "2") (pinfunction "2_2") (pintype "passive"))
      (node (ref "R29") (pin "2") (pinfunction "2_2") (pintype "passive"))
      (node (ref "R3") (pin "1") (pinfunction "1_1") (pintype "passive"))
      (node (ref "R34") (pin "2") (pinfunction "2_2") (pintype "passive"))
      (node (ref "R35") (pin "1") (pinfunction "1_1") (pintype "passive"))
      (node (ref "R36") (pin "1") (pinfunction "1_1") (pintype "passive"))
      (node (ref "R37") (pin "2") (pinfunction "2_2") (pintype "passive"))
      (node (ref "R39") (pin "2") (pinfunction "2_2") (pintype "passive"))
      (node (ref "R4") (pin "2") (pinfunction "2_2") (pintype "passive"))
      (node (ref "R40") (pin "2") (pinfunction "2_2") (pintype "passive"))
      (node (ref "R41") (pin "2") (pinfunction "2_2") (pintype "passive"))
      (node (ref "R42") (pin "2") (pinfunction "2_2") (pintype "passive"))
      (node (ref "R6") (pin "1") (pinfunction "1_1") (pintype "passive"))
      (node (ref "R63") (pin "2") (pinfunction "2_2") (pintype "passive"))
      (node (ref "R76") (pin "1") (pinfunction "1_1") (pintype "passive"))
      (node (ref "S1") (pin "P$3") (pinfunction "P$3_P$3") (pintype "bidirectional"))
      (node (ref "S1") (pin "P$4") (pinfunction "P$4_P$4") (pintype "bidirectional"))
      (node (ref "TC1") (pin "3") (pinfunction "3_3") (pintype "passive"))
      (node (ref "TC1") (pin "5") (pinfunction "5_5") (pintype "passive"))
      (node (ref "U1") (pin "A14") (pinfunction "VSS_A14") (pintype "bidirectional"))
      (node (ref "U1") (pin "A2") (pinfunction "VSS_A2") (pintype "bidirectional"))
      (node (ref "U1") (pin "A27") (pinfunction "VSS_A27") (pintype "bidirectional"))
      (node (ref "U1") (pin "B1") (pinfunction "VSS_B1") (pintype "bidirectional"))
      (node (ref "U1") (pin "B14") (pinfunction "VSS_B14") (pintype "bidirectional"))
      (node (ref "U1") (pin "B28") (pinfunction "VSS_B28") (pintype "bidirectional"))
      (node (ref "U1") (pin "C14") (pinfunction "VSS_C14") (pintype "bidirectional"))
      (node (ref "U1") (pin "C3") (pinfunction "VSS_C3") (pintype "bidirectional"))
      (node (ref "U1") (pin "C4") (pinfunction "VSS_C4") (pintype "bidirectional"))
      (node (ref "U1") (pin "D14") (pinfunction "VSS_D14") (pintype "bidirectional"))
      (node (ref "U1") (pin "D3") (pinfunction "VSS_D3") (pintype "bidirectional"))
      (node (ref "U1") (pin "D4") (pinfunction "VSS_D4") (pintype "bidirectional"))
      (node (ref "U1") (pin "E10") (pinfunction "VSS_E10") (pintype "bidirectional"))
      (node (ref "U1") (pin "E11") (pinfunction "VSS_E11") (pintype "bidirectional"))
      (node (ref "U1") (pin "E12") (pinfunction "VSS_E12") (pintype "bidirectional"))
      (node (ref "U1") (pin "E13") (pinfunction "VSS_E13") (pintype "bidirectional"))
      (node (ref "U1") (pin "E16") (pinfunction "VSS_E16") (pintype "bidirectional"))
      (node (ref "U1") (pin "E17") (pinfunction "VSS_E17") (pintype "bidirectional"))
      (node (ref "U1") (pin "E18") (pinfunction "VSS_E18") (pintype "bidirectional"))
      (node (ref "U1") (pin "E19") (pinfunction "VSS_E19") (pintype "bidirectional"))
      (node (ref "U1") (pin "E20") (pinfunction "VSS_E20") (pintype "bidirectional"))
      (node (ref "U1") (pin "E21") (pinfunction "VSS_E21") (pintype "bidirectional"))
      (node (ref "U1") (pin "E22") (pinfunction "VSS_E22") (pintype "bidirectional"))
      (node (ref "U1") (pin "E23") (pinfunction "VSS_E23") (pintype "bidirectional"))
      (node (ref "U1") (pin "E24") (pinfunction "VSS_E24") (pintype "bidirectional"))
      (node (ref "U1") (pin "E3") (pinfunction "VSS_E3") (pintype "bidirectional"))
      (node (ref "U1") (pin "E4") (pinfunction "VSS_E4") (pintype "bidirectional"))
      (node (ref "U1") (pin "E5") (pinfunction "VSS_E5") (pintype "bidirectional"))
      (node (ref "U1") (pin "E6") (pinfunction "VSS_E6") (pintype "bidirectional"))
      (node (ref "U1") (pin "E7") (pinfunction "VSS_E7") (pintype "bidirectional"))
      (node (ref "U1") (pin "E8") (pinfunction "VSS_E8") (pintype "bidirectional"))
      (node (ref "U1") (pin "E9") (pinfunction "VSS_E9") (pintype "bidirectional"))
      (node (ref "U1") (pin "F19") (pinfunction "VSS_F19") (pintype "bidirectional"))
      (node (ref "U1") (pin "F20") (pinfunction "VSS_F20") (pintype "bidirectional"))
      (node (ref "U1") (pin "F21") (pinfunction "VSS_F21") (pintype "bidirectional"))
      (node (ref "U1") (pin "F22") (pinfunction "VSS_F22") (pintype "bidirectional"))
      (node (ref "U1") (pin "F23") (pinfunction "VSS_F23") (pintype "bidirectional"))
      (node (ref "U1") (pin "F24") (pinfunction "VSS_F24") (pintype "bidirectional"))
      (node (ref "U1") (pin "G19") (pinfunction "VSS_G19") (pintype "bidirectional"))
      (node (ref "U1") (pin "G2") (pinfunction "MCU_OSC0_XO_G2") (pintype "bidirectional"))
      (node (ref "U1") (pin "G20") (pinfunction "VSS_G20") (pintype "bidirectional"))
      (node (ref "U1") (pin "G23") (pinfunction "VSS_G23") (pintype "bidirectional"))
      (node (ref "U1") (pin "G24") (pinfunction "VSS_G24") (pintype "bidirectional"))
      (node (ref "U1") (pin "H19") (pinfunction "VSS_H19") (pintype "bidirectional"))
      (node (ref "U1") (pin "H2") (pinfunction "WKUP_LFOSC0_XO_H2") (pintype "bidirectional"))
      (node (ref "U1") (pin "H20") (pinfunction "VSS_H20") (pintype "bidirectional"))
      (node (ref "U1") (pin "H24") (pinfunction "VSS_H24") (pintype "bidirectional"))
      (node (ref "U1") (pin "J14") (pinfunction "VSS_J14") (pintype "bidirectional"))
      (node (ref "U1") (pin "J15") (pinfunction "VSS_J15") (pintype "bidirectional"))
      (node (ref "U1") (pin "J19") (pinfunction "VSS_J19") (pintype "bidirectional"))
      (node (ref "U1") (pin "J20") (pinfunction "VSS_J20") (pintype "bidirectional"))
      (node (ref "U1") (pin "J24") (pinfunction "VSS_J24") (pintype "bidirectional"))
      (node (ref "U1") (pin "K14") (pinfunction "VSS_K14") (pintype "bidirectional"))
      (node (ref "U1") (pin "K15") (pinfunction "VSS_K15") (pintype "bidirectional"))
      (node (ref "U1") (pin "K19") (pinfunction "VSS_K19") (pintype "bidirectional"))
      (node (ref "U1") (pin "K20") (pinfunction "VSS_K20") (pintype "bidirectional"))
      (node (ref "U1") (pin "K24") (pinfunction "VSS_K24") (pintype "bidirectional"))
      (node (ref "U1") (pin "K6") (pinfunction "VSS_K6") (pintype "bidirectional"))
      (node (ref "U1") (pin "K7") (pinfunction "VSS_K7") (pintype "bidirectional"))
      (node (ref "U1") (pin "K8") (pinfunction "VSS_K8") (pintype "bidirectional"))
      (node (ref "U1") (pin "K9") (pinfunction "VSS_K9") (pintype "bidirectional"))
      (node (ref "U1") (pin "L19") (pinfunction "VSS_L19") (pintype "bidirectional"))
      (node (ref "U1") (pin "L20") (pinfunction "VSS_L20") (pintype "bidirectional"))
      (node (ref "U1") (pin "L24") (pinfunction "VSS_L24") (pintype "bidirectional"))
      (node (ref "U1") (pin "L5") (pinfunction "VSS_L5") (pintype "bidirectional"))
      (node (ref "U1") (pin "L6") (pinfunction "VSS_L6") (pintype "bidirectional"))
      (node (ref "U1") (pin "L7") (pinfunction "VSS_L7") (pintype "bidirectional"))
      (node (ref "U1") (pin "L8") (pinfunction "VSS_L8") (pintype "bidirectional"))
      (node (ref "U1") (pin "M20") (pinfunction "VSS_M20") (pintype "bidirectional"))
      (node (ref "U1") (pin "M23") (pinfunction "VSS_M23") (pintype "bidirectional"))
      (node (ref "U1") (pin "M24") (pinfunction "VSS_M24") (pintype "bidirectional"))
      (node (ref "U1") (pin "M4") (pinfunction "VSS_M4") (pintype "bidirectional"))
      (node (ref "U1") (pin "M5") (pinfunction "VSS_M5") (pintype "bidirectional"))
      (node (ref "U1") (pin "M6") (pinfunction "VSS_M6") (pintype "bidirectional"))
      (node (ref "U1") (pin "M7") (pinfunction "VSS_M7") (pintype "bidirectional"))
      (node (ref "U1") (pin "N20") (pinfunction "VSS_N20") (pintype "bidirectional"))
      (node (ref "U1") (pin "N21") (pinfunction "VSS_N21") (pintype "bidirectional"))
      (node (ref "U1") (pin "N22") (pinfunction "VSS_N22") (pintype "bidirectional"))
      (node (ref "U1") (pin "N23") (pinfunction "VSS_N23") (pintype "bidirectional"))
      (node (ref "U1") (pin "N24") (pinfunction "VSS_N24") (pintype "bidirectional"))
      (node (ref "U1") (pin "N3") (pinfunction "VSS_N3") (pintype "bidirectional"))
      (node (ref "U1") (pin "N4") (pinfunction "VSS_N4") (pintype "bidirectional"))
      (node (ref "U1") (pin "N5") (pinfunction "VSS_N5") (pintype "bidirectional"))
      (node (ref "U1") (pin "N6") (pinfunction "VSS_N6") (pintype "bidirectional"))
      (node (ref "U1") (pin "P16") (pinfunction "VSS_P16") (pintype "bidirectional"))
      (node (ref "U1") (pin "P17") (pinfunction "VSS_P17") (pintype "bidirectional"))
      (node (ref "U1") (pin "P18") (pinfunction "VSS_P18") (pintype "bidirectional"))
      (node (ref "U1") (pin "P19") (pinfunction "VSS_P19") (pintype "bidirectional"))
      (node (ref "U1") (pin "P20") (pinfunction "VSS_P20") (pintype "bidirectional"))
      (node (ref "U1") (pin "P21") (pinfunction "VSS_P21") (pintype "bidirectional"))
      (node (ref "U1") (pin "P22") (pinfunction "VSS_P22") (pintype "bidirectional"))
      (node (ref "U1") (pin "P23") (pinfunction "VSS_P23") (pintype "bidirectional"))
      (node (ref "U1") (pin "P24") (pinfunction "VSS_P24") (pintype "bidirectional"))
      (node (ref "U1") (pin "P3") (pinfunction "VSS_P3") (pintype "bidirectional"))
      (node (ref "U1") (pin "P4") (pinfunction "VSS_P4") (pintype "bidirectional"))
      (node (ref "U1") (pin "P5") (pinfunction "VSS_P5") (pintype "bidirectional"))
      (node (ref "U1") (pin "R3") (pinfunction "VSS_R3") (pintype "bidirectional"))
      (node (ref "U1") (pin "R4") (pinfunction "VSS_R4") (pintype "bidirectional"))
      (node (ref "U1") (pin "T19") (pinfunction "VSS_T19") (pintype "bidirectional"))
      (node (ref "U1") (pin "T3") (pinfunction "VSS_T3") (pintype "bidirectional"))
      (node (ref "U1") (pin "U1") (pinfunction "VSS_U1") (pintype "bidirectional"))
      (node (ref "U1") (pin "U19") (pinfunction "VSS_U19") (pintype "bidirectional"))
      (node (ref "U1") (pin "U28") (pinfunction "VSS_U28") (pintype "bidirectional"))
      (node (ref "U1") (pin "V19") (pinfunction "VSS_V19") (pintype "bidirectional"))
      (node (ref "U1") (pin "V2") (pinfunction "VSS_V2") (pintype "bidirectional"))
      (node (ref "U1") (pin "V27") (pinfunction "VSS_V27") (pintype "bidirectional"))
      (node (ref "U10") (pin "2") (pinfunction "GND_2") (pintype "power_in"))
      (node (ref "U11") (pin "3") (pinfunction "GND_3") (pintype "passive"))
      (node (ref "U12") (pin "A1") (pinfunction "1OEN_A1") (pintype "bidirectional"))
      (node (ref "U12") (pin "D1") (pinfunction "GND_D1") (pintype "bidirectional"))
      (node (ref "U13") (pin "A1") (pinfunction "1OEN_A1") (pintype "bidirectional"))
      (node (ref "U13") (pin "D1") (pinfunction "GND_D1") (pintype "bidirectional"))
      (node (ref "U14") (pin "2") (pinfunction "GND_2") (pintype "bidirectional"))
      (node (ref "U14") (pin "5") (pinfunction "EP_5") (pintype "bidirectional"))
      (node (ref "U2") (pin "4") (pinfunction "GND_4") (pintype "power_in"))
      (node (ref "U3") (pin "4") (pinfunction "GND_4") (pintype "bidirectional"))
      (node (ref "U4") (pin "2") (pinfunction "VSS_2") (pintype "bidirectional"))
      (node (ref "U5") (pin "5") (pinfunction "GND_5") (pintype "power_in"))
      (node (ref "U5") (pin "9") (pinfunction "EXP_9") (pintype "passive"))
      (node (ref "U6") (pin "15") (pinfunction "AGND_15") (pintype "bidirectional"))
      (node (ref "U6") (pin "PAD") (pinfunction "PAD_PAD") (pintype "bidirectional"))
      (node (ref "U7") (pin "2") (pinfunction "GND_2") (pintype "power_in"))
      (node (ref "U8") (pin "2") (pinfunction "GND_2") (pintype "power_in"))
      (node (ref "U9") (pin "4") (pinfunction "GND_4") (pintype "power_in"))
      (node (ref "X1") (pin "G0") (pinfunction "GND_G0") (pintype "passive"))
      (node (ref "X1") (pin "G1") (pinfunction "GND_G1") (pintype "passive"))
      (node (ref "X1") (pin "PIN6") (pinfunction "VSS_PIN6") (pintype "power_in"))
      (node (ref "Y1") (pin "2") (pinfunction "GND_2") (pintype "bidirectional"))
      (node (ref "Y2") (pin "2") (pinfunction "GND_2") (pintype "bidirectional"))
    )
    (net (code "241") (name "Net-(D1-A)") (class "Default")
      (node (ref "D1") (pin "1") (pinfunction "A_1") (pintype "passive"))
      (node (ref "R57") (pin "1") (pinfunction "1_1") (pintype "passive"))
    )
    (net (code "242") (name "Net-(D2-A)") (class "Default")
      (node (ref "D2") (pin "1") (pinfunction "A_1") (pintype "passive"))
      (node (ref "R58") (pin "1") (pinfunction "1_1") (pintype "passive"))
    )
    (net (code "243") (name "Net-(D3-A)") (class "Default")
      (node (ref "D3") (pin "1") (pinfunction "A_1") (pintype "passive"))
      (node (ref "R59") (pin "1") (pinfunction "1_1") (pintype "passive"))
    )
    (net (code "244") (name "Net-(D4-A)") (class "Default")
      (node (ref "D4") (pin "1") (pinfunction "A_1") (pintype "passive"))
      (node (ref "R60") (pin "1") (pinfunction "1_1") (pintype "passive"))
    )
    (net (code "245") (name "Net-(D5-A)") (class "Default")
      (node (ref "D5") (pin "1") (pinfunction "A_1") (pintype "passive"))
      (node (ref "R61") (pin "1") (pinfunction "1_1") (pintype "passive"))
    )
    (net (code "246") (name "Net-(D6-A)") (class "Default")
      (node (ref "D6") (pin "ANODE") (pinfunction "A_ANODE") (pintype "passive"))
      (node (ref "D7") (pin "ANODE") (pinfunction "A_ANODE") (pintype "passive"))
      (node (ref "R54") (pin "2") (pinfunction "2_2") (pintype "passive"))
      (node (ref "U10") (pin "3") (pinfunction "ON_3") (pintype "input"))
    )
    (net (code "247") (name "Net-(J5-CC1)") (class "Default")
      (node (ref "J5") (pin "A5") (pinfunction "CC1_A5") (pintype "bidirectional"))
      (node (ref "R35") (pin "2") (pinfunction "2_2") (pintype "passive"))
    )
    (net (code "248") (name "Net-(J5-CC2)") (class "Default")
      (node (ref "J5") (pin "B5") (pinfunction "CC2_B5") (pintype "bidirectional"))
      (node (ref "R36") (pin "2") (pinfunction "2_2") (pintype "passive"))
    )
    (net (code "249") (name "Net-(J6-CC1)") (class "Default")
      (node (ref "J6") (pin "A5") (pinfunction "CC1_A5") (pintype "bidirectional"))
      (node (ref "R72") (pin "1") (pinfunction "1_1") (pintype "passive"))
    )
    (net (code "250") (name "Net-(J6-CC2)") (class "Default")
      (node (ref "J6") (pin "B5") (pinfunction "CC2_B5") (pintype "bidirectional"))
      (node (ref "R71") (pin "1") (pinfunction "1_1") (pintype "passive"))
    )
    (net (code "251") (name "Net-(R8-Pad1)") (class "Default")
      (node (ref "R8") (pin "1") (pinfunction "1_1") (pintype "passive"))
      (node (ref "R9") (pin "2") (pinfunction "2_2") (pintype "passive"))
    )
    (net (code "252") (name "Net-(U3-FB)") (class "Default")
      (node (ref "C30") (pin "1") (pinfunction "1_1") (pintype "passive"))
      (node (ref "R6") (pin "2") (pinfunction "2_2") (pintype "passive"))
      (node (ref "R8") (pin "2") (pinfunction "2_2") (pintype "passive"))
      (node (ref "U3") (pin "3") (pinfunction "FB_3") (pintype "bidirectional"))
    )
    (net (code "253") (name "Net-(U3-SW)") (class "Default")
      (node (ref "L1") (pin "1") (pinfunction "1_1") (pintype "passive"))
      (node (ref "U3") (pin "5") (pinfunction "SW_5") (pintype "bidirectional"))
    )
    (net (code "254") (name "Net-(U5-CT)") (class "Default")
      (node (ref "C28") (pin "1") (pinfunction "1_1") (pintype "passive"))
      (node (ref "U5") (pin "6") (pinfunction "CT_6") (pintype "output"))
    )
    (net (code "255") (name "Net-(U6-LX_B1_1)") (class "Default")
      (node (ref "L4") (pin "1") (pinfunction "1_1") (pintype "passive"))
      (node (ref "U6") (pin "2") (pinfunction "LX_B1_1_2") (pintype "bidirectional"))
      (node (ref "U6") (pin "3") (pinfunction "LX_B1_2_3") (pintype "bidirectional"))
    )
    (net (code "256") (name "Net-(U6-LX_B2)") (class "Default")
      (node (ref "L3") (pin "1") (pinfunction "1_1") (pintype "passive"))
      (node (ref "U6") (pin "29") (pinfunction "LX_B2_29") (pintype "bidirectional"))
    )
    (net (code "257") (name "Net-(U6-LX_B3)") (class "Default")
      (node (ref "L2") (pin "1") (pinfunction "1_1") (pintype "passive"))
      (node (ref "U6") (pin "27") (pinfunction "LX_B3_27") (pintype "bidirectional"))
    )
    (net (code "258") (name "Net-(U6-VDD1P8)") (class "Default")
      (node (ref "C41") (pin "1") (pinfunction "1_1") (pintype "passive"))
      (node (ref "U6") (pin "14") (pinfunction "VDD1P8_14") (pintype "bidirectional"))
    )
    (net (code "259") (name "Net-(U7-ADDR)") (class "Default")
      (node (ref "R15") (pin "2") (pinfunction "2_2") (pintype "passive"))
      (node (ref "U7") (pin "4") (pinfunction "ADDR_4") (pintype "input"))
    )
    (net (code "260") (name "Net-(U8-ADDR)") (class "Default")
      (node (ref "R16") (pin "1") (pinfunction "1_1") (pintype "passive"))
      (node (ref "U8") (pin "4") (pinfunction "ADDR_4") (pintype "input"))
    )
    (net (code "261") (name "Net-(U11-A)") (class "Default")
      (node (ref "R48") (pin "1") (pinfunction "1_1") (pintype "passive"))
      (node (ref "U11") (pin "2") (pinfunction "A_2") (pintype "input"))
      (node (ref "X1") (pin "PIN10") (pinfunction "DET_PIN10") (pintype "passive"))
      (node (ref "X1") (pin "PIN9") (pinfunction "DET_PIN9") (pintype "passive"))
    )
    (net (code "262") (name "Net-(U14-EN)") (class "Default")
      (node (ref "J1") (pin "2") (pinfunction "2_2") (pintype "bidirectional"))
      (node (ref "R3") (pin "2") (pinfunction "2_2") (pintype "passive"))
      (node (ref "U14") (pin "3") (pinfunction "EN_3") (pintype "bidirectional"))
    )
    (net (code "263") (name "Net-(X1-CLK)") (class "Default")
      (node (ref "R33") (pin "1") (pinfunction "1_1") (pintype "passive"))
      (node (ref "X1") (pin "PIN5") (pinfunction "CLK_PIN5") (pintype "bidirectional"))
    )
    (net (code "264") (name "Net-(Y2-ST)") (class "Default")
      (node (ref "R50") (pin "2") (pinfunction "2_2") (pintype "passive"))
      (node (ref "Y2") (pin "1") (pinfunction "ST_1") (pintype "bidirectional"))
    )
    (net (code "265") (name "unconnected-(FUD1-PadP$1)") (class "Default")
      (node (ref "FUD1") (pin "P$1") (pinfunction "P$1_P$1") (pintype "no_connect"))
    )
    (net (code "266") (name "unconnected-(FUD2-PadP$1)") (class "Default")
      (node (ref "FUD2") (pin "P$1") (pinfunction "P$1_P$1") (pintype "no_connect"))
    )
    (net (code "267") (name "unconnected-(FUD3-PadP$1)") (class "Default")
      (node (ref "FUD3") (pin "P$1") (pinfunction "P$1_P$1") (pintype "no_connect"))
    )
    (net (code "268") (name "unconnected-(FUD4-PadP$1)") (class "Default")
      (node (ref "FUD4") (pin "P$1") (pinfunction "P$1_P$1") (pintype "no_connect"))
    )
    (net (code "269") (name "unconnected-(FUD5-PadP$1)") (class "Default")
      (node (ref "FUD5") (pin "P$1") (pinfunction "P$1_P$1") (pintype "no_connect"))
    )
    (net (code "270") (name "unconnected-(FUD6-PadP$1)") (class "Default")
      (node (ref "FUD6") (pin "P$1") (pinfunction "P$1_P$1") (pintype "no_connect"))
    )
    (net (code "271") (name "unconnected-(J4-16-Pad15_1)") (class "Default")
      (node (ref "J4") (pin "15_1") (pinfunction "16_15_1") (pintype "passive"))
    )
    (net (code "272") (name "unconnected-(J4-17-Pad14_1)") (class "Default")
      (node (ref "J4") (pin "14_1") (pinfunction "17_14_1") (pintype "passive"))
    )
    (net (code "273") (name "unconnected-(J4-18-Pad13_1)") (class "Default")
      (node (ref "J4") (pin "13_1") (pinfunction "18_13_1") (pintype "passive"))
    )
    (net (code "274") (name "unconnected-(J4-19-Pad12_1)") (class "Default")
      (node (ref "J4") (pin "12_1") (pinfunction "19_12_1") (pintype "passive"))
    )
    (net (code "275") (name "unconnected-(J4-20-Pad11_1)") (class "Default")
      (node (ref "J4") (pin "11_1") (pinfunction "20_11_1") (pintype "passive"))
    )
    (net (code "276") (name "unconnected-(J4-21-Pad10_1)") (class "Default")
      (node (ref "J4") (pin "10_1") (pinfunction "21_10_1") (pintype "passive"))
    )
    (net (code "277") (name "unconnected-(J4-22-Pad9_1)") (class "Default")
      (node (ref "J4") (pin "9_1") (pinfunction "22_9_1") (pintype "passive"))
    )
    (net (code "278") (name "unconnected-(J4-23-Pad8_1)") (class "Default")
      (node (ref "J4") (pin "8_1") (pinfunction "23_8_1") (pintype "passive"))
    )
    (net (code "279") (name "unconnected-(J4-24-Pad7_1)") (class "Default")
      (node (ref "J4") (pin "7_1") (pinfunction "24_7_1") (pintype "passive"))
    )
    (net (code "280") (name "unconnected-(J4-25-Pad6_1)") (class "Default")
      (node (ref "J4") (pin "6_1") (pinfunction "25_6_1") (pintype "passive"))
    )
    (net (code "281") (name "unconnected-(J4-26-Pad5_1)") (class "Default")
      (node (ref "J4") (pin "5_1") (pinfunction "26_5_1") (pintype "passive"))
    )
    (net (code "282") (name "unconnected-(J4-27-Pad4_1)") (class "Default")
      (node (ref "J4") (pin "4_1") (pinfunction "27_4_1") (pintype "passive"))
    )
    (net (code "283") (name "unconnected-(J4-28-Pad3_1)") (class "Default")
      (node (ref "J4") (pin "3_1") (pinfunction "28_3_1") (pintype "passive"))
    )
    (net (code "284") (name "unconnected-(J4-29-Pad2_1)") (class "Default")
      (node (ref "J4") (pin "2_1") (pinfunction "29_2_1") (pintype "passive"))
    )
    (net (code "285") (name "unconnected-(J4-30-Pad1_1)") (class "Default")
      (node (ref "J4") (pin "1_1") (pinfunction "30_1_1") (pintype "passive"))
    )
    (net (code "286") (name "unconnected-(J5-SBU1-PadA8)") (class "Default")
      (node (ref "J5") (pin "A8") (pinfunction "SBU1_A8") (pintype "bidirectional"))
    )
    (net (code "287") (name "unconnected-(J5-SBU2-PadB8)") (class "Default")
      (node (ref "J5") (pin "B8") (pinfunction "SBU2_B8") (pintype "bidirectional"))
    )
    (net (code "288") (name "unconnected-(J6-SBU1-PadA8)") (class "Default")
      (node (ref "J6") (pin "A8") (pinfunction "SBU1_A8") (pintype "bidirectional"))
    )
    (net (code "289") (name "unconnected-(J6-SBU2-PadB8)") (class "Default")
      (node (ref "J6") (pin "B8") (pinfunction "SBU2_B8") (pintype "bidirectional"))
    )
    (net (code "290") (name "unconnected-(J8-Pad4)") (class "Default")
      (node (ref "J8") (pin "4") (pinfunction "4_4") (pintype "bidirectional"))
    )
    (net (code "291") (name "unconnected-(J8-Pad5)") (class "Default")
      (node (ref "J8") (pin "5") (pinfunction "5_5") (pintype "bidirectional"))
    )
    (net (code "292") (name "unconnected-(U1F-CSI0_RXN2-PadU14)") (class "Default")
      (node (ref "U1") (pin "U14") (pinfunction "CSI0_RXN2_U14") (pintype "bidirectional"))
    )
    (net (code "293") (name "unconnected-(U1F-CSI0_RXN3-PadU13)") (class "Default")
      (node (ref "U1") (pin "U13") (pinfunction "CSI0_RXN3_U13") (pintype "bidirectional"))
    )
    (net (code "294") (name "unconnected-(U1F-CSI0_RXP2-PadV14)") (class "Default")
      (node (ref "U1") (pin "V14") (pinfunction "CSI0_RXP2_V14") (pintype "bidirectional"))
    )
    (net (code "295") (name "unconnected-(U1F-CSI0_RXP3-PadV13)") (class "Default")
      (node (ref "U1") (pin "V13") (pinfunction "CSI0_RXP3_V13") (pintype "bidirectional"))
    )
    (net (code "296") (name "unconnected-(U1K-AM62X_RSVD0-PadF5)") (class "Default")
      (node (ref "U1") (pin "F5") (pinfunction "AM62X_RSVD0_F5") (pintype "bidirectional"))
    )
    (net (code "297") (name "unconnected-(U1K-AM62X_RSVD1-PadF4)") (class "Default")
      (node (ref "U1") (pin "F4") (pinfunction "AM62X_RSVD1_F4") (pintype "bidirectional"))
    )
    (net (code "298") (name "unconnected-(U1K-AM62X_RSVD2-PadF6)") (class "Default")
      (node (ref "U1") (pin "F6") (pinfunction "AM62X_RSVD2_F6") (pintype "bidirectional"))
    )
    (net (code "299") (name "unconnected-(U1K-AM62X_RSVD3-PadN17)") (class "Default")
      (node (ref "U1") (pin "N17") (pinfunction "AM62X_RSVD3_N17") (pintype "bidirectional"))
    )
    (net (code "300") (name "unconnected-(U1K-AM62X_RSVD4-PadF8)") (class "Default")
      (node (ref "U1") (pin "F8") (pinfunction "AM62X_RSVD4_F8") (pintype "bidirectional"))
    )
    (net (code "301") (name "unconnected-(U1K-AM62X_RSVD5-PadF9)") (class "Default")
      (node (ref "U1") (pin "F9") (pinfunction "AM62X_RSVD5_F9") (pintype "bidirectional"))
    )
    (net (code "302") (name "unconnected-(U1K-AM62X_RSVD6-PadM18)") (class "Default")
      (node (ref "U1") (pin "M18") (pinfunction "AM62X_RSVD6_M18") (pintype "bidirectional"))
    )
    (net (code "303") (name "unconnected-(U1K-AM62X_RSVD7-PadN18)") (class "Default")
      (node (ref "U1") (pin "N18") (pinfunction "AM62X_RSVD7_N18") (pintype "bidirectional"))
    )
    (net (code "304") (name "unconnected-(U1K-AM62X_RSVD8-PadF7)") (class "Default")
      (node (ref "U1") (pin "F7") (pinfunction "AM62X_RSVD8_F7") (pintype "bidirectional"))
    )
    (net (code "305") (name "unconnected-(U1K-DDR_RSVD0-PadF10)") (class "Default")
      (node (ref "U1") (pin "F10") (pinfunction "DDR_RSVD0_F10") (pintype "bidirectional"))
    )
    (net (code "306") (name "unconnected-(U1L-AM62X_DNU0-PadV18)") (class "Default")
      (node (ref "U1") (pin "V18") (pinfunction "AM62X_DNU0_V18") (pintype "bidirectional"))
    )
    (net (code "307") (name "unconnected-(U1L-AM62X_DNU1-PadU18)") (class "Default")
      (node (ref "U1") (pin "U18") (pinfunction "AM62X_DNU1_U18") (pintype "bidirectional"))
    )
    (net (code "308") (name "unconnected-(U1L-AM62X_DNU2-PadT18)") (class "Default")
      (node (ref "U1") (pin "T18") (pinfunction "AM62X_DNU2_T18") (pintype "bidirectional"))
    )
    (net (code "309") (name "unconnected-(U1L-AM62X_DNU3-PadT17)") (class "Default")
      (node (ref "U1") (pin "T17") (pinfunction "AM62X_DNU3_T17") (pintype "bidirectional"))
    )
    (net (code "310") (name "unconnected-(U1L-AM62X_DNU4-PadT16)") (class "Default")
      (node (ref "U1") (pin "T16") (pinfunction "AM62X_DNU4_T16") (pintype "bidirectional"))
    )
    (net (code "311") (name "unconnected-(U1L-AM62X_DNU5-PadT15)") (class "Default")
      (node (ref "U1") (pin "T15") (pinfunction "AM62X_DNU5_T15") (pintype "bidirectional"))
    )
    (net (code "312") (name "unconnected-(U1L-AM62X_DNU6-PadR18)") (class "Default")
      (node (ref "U1") (pin "R18") (pinfunction "AM62X_DNU6_R18") (pintype "bidirectional"))
    )
    (net (code "313") (name "unconnected-(U1L-AM62X_DNU7-PadR17)") (class "Default")
      (node (ref "U1") (pin "R17") (pinfunction "AM62X_DNU7_R17") (pintype "bidirectional"))
    )
    (net (code "314") (name "unconnected-(U1L-AM62X_DNU8-PadR16)") (class "Default")
      (node (ref "U1") (pin "R16") (pinfunction "AM62X_DNU8_R16") (pintype "bidirectional"))
    )
    (net (code "315") (name "unconnected-(U1L-AM62X_DNU9-PadR15)") (class "Default")
      (node (ref "U1") (pin "R15") (pinfunction "AM62X_DNU9_R15") (pintype "bidirectional"))
    )
    (net (code "316") (name "unconnected-(U1L-AM62X_DNU10-PadM14)") (class "Default")
      (node (ref "U1") (pin "M14") (pinfunction "AM62X_DNU10_M14") (pintype "bidirectional"))
    )
    (net (code "317") (name "unconnected-(U1L-AM62X_DNU11-PadF15)") (class "Default")
      (node (ref "U1") (pin "F15") (pinfunction "AM62X_DNU11_F15") (pintype "bidirectional"))
    )
    (net (code "318") (name "unconnected-(U1L-AM62X_DNU12-PadF16)") (class "Default")
      (node (ref "U1") (pin "F16") (pinfunction "AM62X_DNU12_F16") (pintype "bidirectional"))
    )
    (net (code "319") (name "unconnected-(U1L-AM62X_DNU13-PadJ2)") (class "Default")
      (node (ref "U1") (pin "J2") (pinfunction "AM62X_DNU13_J2") (pintype "bidirectional"))
    )
    (net (code "320") (name "unconnected-(U1L-AM62X_DNU14-PadM19)") (class "Default")
      (node (ref "U1") (pin "M19") (pinfunction "AM62X_DNU14_M19") (pintype "bidirectional"))
    )
    (net (code "321") (name "unconnected-(U1L-AM62X_DNU15-PadN19)") (class "Default")
      (node (ref "U1") (pin "N19") (pinfunction "AM62X_DNU15_N19") (pintype "bidirectional"))
    )
    (net (code "322") (name "unconnected-(U1M-NC_01-PadE14)") (class "Default")
      (node (ref "U1") (pin "E14") (pinfunction "NC_01_E14") (pintype "bidirectional"))
    )
    (net (code "323") (name "unconnected-(U1M-NC_02-PadE15)") (class "Default")
      (node (ref "U1") (pin "E15") (pinfunction "NC_02_E15") (pintype "bidirectional"))
    )
    (net (code "324") (name "unconnected-(U1M-NC_03-PadF3)") (class "Default")
      (node (ref "U1") (pin "F3") (pinfunction "NC_03_F3") (pintype "bidirectional"))
    )
    (net (code "325") (name "unconnected-(U1M-NC_04-PadF17)") (class "Default")
      (node (ref "U1") (pin "F17") (pinfunction "NC_04_F17") (pintype "bidirectional"))
    )
    (net (code "326") (name "unconnected-(U1M-NC_05-PadF18)") (class "Default")
      (node (ref "U1") (pin "F18") (pinfunction "NC_05_F18") (pintype "bidirectional"))
    )
    (net (code "327") (name "unconnected-(U1M-NC_06-PadG3)") (class "Default")
      (node (ref "U1") (pin "G3") (pinfunction "NC_06_G3") (pintype "bidirectional"))
    )
    (net (code "328") (name "unconnected-(U1M-NC_07-PadG4)") (class "Default")
      (node (ref "U1") (pin "G4") (pinfunction "NC_07_G4") (pintype "bidirectional"))
    )
    (net (code "329") (name "unconnected-(U1M-NC_08-PadG5)") (class "Default")
      (node (ref "U1") (pin "G5") (pinfunction "NC_08_G5") (pintype "bidirectional"))
    )
    (net (code "330") (name "unconnected-(U1M-NC_09-PadG6)") (class "Default")
      (node (ref "U1") (pin "G6") (pinfunction "NC_09_G6") (pintype "bidirectional"))
    )
    (net (code "331") (name "unconnected-(U1M-NC_10-PadG7)") (class "Default")
      (node (ref "U1") (pin "G7") (pinfunction "NC_10_G7") (pintype "bidirectional"))
    )
    (net (code "332") (name "unconnected-(U1M-NC_11-PadG8)") (class "Default")
      (node (ref "U1") (pin "G8") (pinfunction "NC_11_G8") (pintype "bidirectional"))
    )
    (net (code "333") (name "unconnected-(U1M-NC_12-PadG9)") (class "Default")
      (node (ref "U1") (pin "G9") (pinfunction "NC_12_G9") (pintype "bidirectional"))
    )
    (net (code "334") (name "unconnected-(U1M-NC_13-PadG17)") (class "Default")
      (node (ref "U1") (pin "G17") (pinfunction "NC_13_G17") (pintype "bidirectional"))
    )
    (net (code "335") (name "unconnected-(U1M-NC_14-PadG18)") (class "Default")
      (node (ref "U1") (pin "G18") (pinfunction "NC_14_G18") (pintype "bidirectional"))
    )
    (net (code "336") (name "unconnected-(U1M-NC_15-PadH3)") (class "Default")
      (node (ref "U1") (pin "H3") (pinfunction "NC_15_H3") (pintype "bidirectional"))
    )
    (net (code "337") (name "unconnected-(U1M-NC_16-PadH4)") (class "Default")
      (node (ref "U1") (pin "H4") (pinfunction "NC_16_H4") (pintype "bidirectional"))
    )
    (net (code "338") (name "unconnected-(U1M-NC_17-PadH5)") (class "Default")
      (node (ref "U1") (pin "H5") (pinfunction "NC_17_H5") (pintype "bidirectional"))
    )
    (net (code "339") (name "unconnected-(U1M-NC_18-PadH6)") (class "Default")
      (node (ref "U1") (pin "H6") (pinfunction "NC_18_H6") (pintype "bidirectional"))
    )
    (net (code "340") (name "unconnected-(U1M-NC_19-PadH7)") (class "Default")
      (node (ref "U1") (pin "H7") (pinfunction "NC_19_H7") (pintype "bidirectional"))
    )
    (net (code "341") (name "unconnected-(U1M-NC_20-PadH8)") (class "Default")
      (node (ref "U1") (pin "H8") (pinfunction "NC_20_H8") (pintype "bidirectional"))
    )
    (net (code "342") (name "unconnected-(U1M-NC_21-PadH9)") (class "Default")
      (node (ref "U1") (pin "H9") (pinfunction "NC_21_H9") (pintype "bidirectional"))
    )
    (net (code "343") (name "unconnected-(U1M-NC_22-PadH10)") (class "Default")
      (node (ref "U1") (pin "H10") (pinfunction "NC_22_H10") (pintype "bidirectional"))
    )
    (net (code "344") (name "unconnected-(U1M-NC_23-PadH11)") (class "Default")
      (node (ref "U1") (pin "H11") (pinfunction "NC_23_H11") (pintype "bidirectional"))
    )
    (net (code "345") (name "unconnected-(U1M-NC_24-PadH23)") (class "Default")
      (node (ref "U1") (pin "H23") (pinfunction "NC_24_H23") (pintype "bidirectional"))
    )
    (net (code "346") (name "unconnected-(U1M-NC_25-PadJ3)") (class "Default")
      (node (ref "U1") (pin "J3") (pinfunction "NC_25_J3") (pintype "bidirectional"))
    )
    (net (code "347") (name "unconnected-(U1M-NC_26-PadJ4)") (class "Default")
      (node (ref "U1") (pin "J4") (pinfunction "NC_26_J4") (pintype "bidirectional"))
    )
    (net (code "348") (name "unconnected-(U1M-NC_27-PadJ5)") (class "Default")
      (node (ref "U1") (pin "J5") (pinfunction "NC_27_J5") (pintype "bidirectional"))
    )
    (net (code "349") (name "unconnected-(U1M-NC_28-PadJ6)") (class "Default")
      (node (ref "U1") (pin "J6") (pinfunction "NC_28_J6") (pintype "bidirectional"))
    )
    (net (code "350") (name "unconnected-(U1M-NC_29-PadJ7)") (class "Default")
      (node (ref "U1") (pin "J7") (pinfunction "NC_29_J7") (pintype "bidirectional"))
    )
    (net (code "351") (name "unconnected-(U1M-NC_30-PadJ8)") (class "Default")
      (node (ref "U1") (pin "J8") (pinfunction "NC_30_J8") (pintype "bidirectional"))
    )
    (net (code "352") (name "unconnected-(U1M-NC_31-PadJ9)") (class "Default")
      (node (ref "U1") (pin "J9") (pinfunction "NC_31_J9") (pintype "bidirectional"))
    )
    (net (code "353") (name "unconnected-(U1M-NC_32-PadJ10)") (class "Default")
      (node (ref "U1") (pin "J10") (pinfunction "NC_32_J10") (pintype "bidirectional"))
    )
    (net (code "354") (name "unconnected-(U1M-NC_33-PadJ11)") (class "Default")
      (node (ref "U1") (pin "J11") (pinfunction "NC_33_J11") (pintype "bidirectional"))
    )
    (net (code "355") (name "unconnected-(U1M-NC_34-PadJ23)") (class "Default")
      (node (ref "U1") (pin "J23") (pinfunction "NC_34_J23") (pintype "bidirectional"))
    )
    (net (code "356") (name "unconnected-(U1M-NC_35-PadK3)") (class "Default")
      (node (ref "U1") (pin "K3") (pinfunction "NC_35_K3") (pintype "bidirectional"))
    )
    (net (code "357") (name "unconnected-(U1M-NC_36-PadK4)") (class "Default")
      (node (ref "U1") (pin "K4") (pinfunction "NC_36_K4") (pintype "bidirectional"))
    )
    (net (code "358") (name "unconnected-(U1M-NC_37-PadK5)") (class "Default")
      (node (ref "U1") (pin "K5") (pinfunction "NC_37_K5") (pintype "bidirectional"))
    )
    (net (code "359") (name "unconnected-(U1M-NC_38-PadK23)") (class "Default")
      (node (ref "U1") (pin "K23") (pinfunction "NC_38_K23") (pintype "bidirectional"))
    )
    (net (code "360") (name "unconnected-(U1M-NC_39-PadL3)") (class "Default")
      (node (ref "U1") (pin "L3") (pinfunction "NC_39_L3") (pintype "bidirectional"))
    )
    (net (code "361") (name "unconnected-(U1M-NC_40-PadL4)") (class "Default")
      (node (ref "U1") (pin "L4") (pinfunction "NC_40_L4") (pintype "bidirectional"))
    )
    (net (code "362") (name "unconnected-(U1M-NC_41-PadL12)") (class "Default")
      (node (ref "U1") (pin "L12") (pinfunction "NC_41_L12") (pintype "bidirectional"))
    )
    (net (code "363") (name "unconnected-(U1M-NC_42-PadL16)") (class "Default")
      (node (ref "U1") (pin "L16") (pinfunction "NC_42_L16") (pintype "bidirectional"))
    )
    (net (code "364") (name "unconnected-(U1M-NC_43-PadL23)") (class "Default")
      (node (ref "U1") (pin "L23") (pinfunction "NC_43_L23") (pintype "bidirectional"))
    )
    (net (code "365") (name "unconnected-(U1M-NC_44-PadM3)") (class "Default")
      (node (ref "U1") (pin "M3") (pinfunction "NC_44_M3") (pintype "bidirectional"))
    )
    (net (code "366") (name "unconnected-(U1M-NC_45-PadM11)") (class "Default")
      (node (ref "U1") (pin "M11") (pinfunction "NC_45_M11") (pintype "bidirectional"))
    )
    (net (code "367") (name "unconnected-(U1M-NC_46-PadM15)") (class "Default")
      (node (ref "U1") (pin "M15") (pinfunction "NC_46_M15") (pintype "bidirectional"))
    )
    (net (code "368") (name "unconnected-(U1M-NC_47-PadM16)") (class "Default")
      (node (ref "U1") (pin "M16") (pinfunction "NC_47_M16") (pintype "bidirectional"))
    )
    (net (code "369") (name "unconnected-(U1M-NC_48-PadM17)") (class "Default")
      (node (ref "U1") (pin "M17") (pinfunction "NC_48_M17") (pintype "bidirectional"))
    )
    (net (code "370") (name "unconnected-(U1M-NC_49-PadN15)") (class "Default")
      (node (ref "U1") (pin "N15") (pinfunction "NC_49_N15") (pintype "bidirectional"))
    )
    (net (code "371") (name "unconnected-(U1M-NC_50-PadN16)") (class "Default")
      (node (ref "U1") (pin "N16") (pinfunction "NC_50_N16") (pintype "bidirectional"))
    )
    (net (code "372") (name "unconnected-(U1M-NC_51-PadP6)") (class "Default")
      (node (ref "U1") (pin "P6") (pinfunction "NC_51_P6") (pintype "bidirectional"))
    )
    (net (code "373") (name "unconnected-(U1M-NC_52-PadP7)") (class "Default")
      (node (ref "U1") (pin "P7") (pinfunction "NC_52_P7") (pintype "bidirectional"))
    )
    (net (code "374") (name "unconnected-(U1M-NC_53-PadP8)") (class "Default")
      (node (ref "U1") (pin "P8") (pinfunction "NC_53_P8") (pintype "bidirectional"))
    )
    (net (code "375") (name "unconnected-(U1M-NC_54-PadP9)") (class "Default")
      (node (ref "U1") (pin "P9") (pinfunction "NC_54_P9") (pintype "bidirectional"))
    )
    (net (code "376") (name "unconnected-(U1M-NC_55-PadP14)") (class "Default")
      (node (ref "U1") (pin "P14") (pinfunction "NC_55_P14") (pintype "bidirectional"))
    )
    (net (code "377") (name "unconnected-(U1M-NC_56-PadP15)") (class "Default")
      (node (ref "U1") (pin "P15") (pinfunction "NC_56_P15") (pintype "bidirectional"))
    )
    (net (code "378") (name "unconnected-(U1M-NC_57-PadR5)") (class "Default")
      (node (ref "U1") (pin "R5") (pinfunction "NC_57_R5") (pintype "bidirectional"))
    )
    (net (code "379") (name "unconnected-(U1M-NC_58-PadR6)") (class "Default")
      (node (ref "U1") (pin "R6") (pinfunction "NC_58_R6") (pintype "bidirectional"))
    )
    (net (code "380") (name "unconnected-(U1M-NC_59-PadR7)") (class "Default")
      (node (ref "U1") (pin "R7") (pinfunction "NC_59_R7") (pintype "bidirectional"))
    )
    (net (code "381") (name "unconnected-(U1M-NC_60-PadR8)") (class "Default")
      (node (ref "U1") (pin "R8") (pinfunction "NC_60_R8") (pintype "bidirectional"))
    )
    (net (code "382") (name "unconnected-(U1M-NC_61-PadR9)") (class "Default")
      (node (ref "U1") (pin "R9") (pinfunction "NC_61_R9") (pintype "bidirectional"))
    )
    (net (code "383") (name "unconnected-(U1M-NC_62-PadR10)") (class "Default")
      (node (ref "U1") (pin "R10") (pinfunction "NC_62_R10") (pintype "bidirectional"))
    )
    (net (code "384") (name "unconnected-(U1M-NC_63-PadR11)") (class "Default")
      (node (ref "U1") (pin "R11") (pinfunction "NC_63_R11") (pintype "bidirectional"))
    )
    (net (code "385") (name "unconnected-(U1M-NC_64-PadR12)") (class "Default")
      (node (ref "U1") (pin "R12") (pinfunction "NC_64_R12") (pintype "bidirectional"))
    )
    (net (code "386") (name "unconnected-(U1M-NC_65-PadR13)") (class "Default")
      (node (ref "U1") (pin "R13") (pinfunction "NC_65_R13") (pintype "bidirectional"))
    )
    (net (code "387") (name "unconnected-(U1M-NC_66-PadR14)") (class "Default")
      (node (ref "U1") (pin "R14") (pinfunction "NC_66_R14") (pintype "bidirectional"))
    )
    (net (code "388") (name "unconnected-(U1M-NC_67-PadT4)") (class "Default")
      (node (ref "U1") (pin "T4") (pinfunction "NC_67_T4") (pintype "bidirectional"))
    )
    (net (code "389") (name "unconnected-(U1M-NC_68-PadT5)") (class "Default")
      (node (ref "U1") (pin "T5") (pinfunction "NC_68_T5") (pintype "bidirectional"))
    )
    (net (code "390") (name "unconnected-(U1M-NC_69-PadT6)") (class "Default")
      (node (ref "U1") (pin "T6") (pinfunction "NC_69_T6") (pintype "bidirectional"))
    )
    (net (code "391") (name "unconnected-(U1M-NC_70-PadT7)") (class "Default")
      (node (ref "U1") (pin "T7") (pinfunction "NC_70_T7") (pintype "bidirectional"))
    )
    (net (code "392") (name "unconnected-(U1M-NC_71-PadT8)") (class "Default")
      (node (ref "U1") (pin "T8") (pinfunction "NC_71_T8") (pintype "bidirectional"))
    )
    (net (code "393") (name "unconnected-(U1M-NC_72-PadT9)") (class "Default")
      (node (ref "U1") (pin "T9") (pinfunction "NC_72_T9") (pintype "bidirectional"))
    )
    (net (code "394") (name "unconnected-(U1M-NC_73-PadT10)") (class "Default")
      (node (ref "U1") (pin "T10") (pinfunction "NC_73_T10") (pintype "bidirectional"))
    )
    (net (code "395") (name "unconnected-(U1M-NC_74-PadT11)") (class "Default")
      (node (ref "U1") (pin "T11") (pinfunction "NC_74_T11") (pintype "bidirectional"))
    )
    (net (code "396") (name "unconnected-(U1M-NC_75-PadT12)") (class "Default")
      (node (ref "U1") (pin "T12") (pinfunction "NC_75_T12") (pintype "bidirectional"))
    )
    (net (code "397") (name "unconnected-(U1M-NC_76-PadT13)") (class "Default")
      (node (ref "U1") (pin "T13") (pinfunction "NC_76_T13") (pintype "bidirectional"))
    )
    (net (code "398") (name "unconnected-(U1M-NC_77-PadT14)") (class "Default")
      (node (ref "U1") (pin "T14") (pinfunction "NC_77_T14") (pintype "bidirectional"))
    )
    (net (code "399") (name "unconnected-(U2-ID-Pad3)") (class "Default")
      (node (ref "U2") (pin "3") (pinfunction "ID_3") (pintype "passive"))
    )
    (net (code "400") (name "unconnected-(U2-N.C.-Pad5)") (class "Default")
      (node (ref "U2") (pin "5") (pinfunction "N.C._5") (pintype "no_connect"))
    )
    (net (code "401") (name "unconnected-(U3-PG-Pad2)") (class "Default")
      (node (ref "U3") (pin "2") (pinfunction "PG_2") (pintype "bidirectional"))
    )
    (net (code "402") (name "unconnected-(U6-GPIO-Pad16)") (class "Default")
      (node (ref "U6") (pin "16") (pinfunction "GPIO_16") (pintype "bidirectional"))
    )
    (net (code "403") (name "unconnected-(U6-GPO1-Pad8)") (class "Default")
      (node (ref "U6") (pin "8") (pinfunction "GPO1_8") (pintype "bidirectional"))
    )
    (net (code "404") (name "unconnected-(U9-ID-Pad3)") (class "Default")
      (node (ref "U9") (pin "3") (pinfunction "ID_3") (pintype "passive"))
    )
    (net (code "405") (name "unconnected-(U9-N.C.-Pad5)") (class "Default")
      (node (ref "U9") (pin "5") (pinfunction "N.C._5") (pintype "no_connect"))
    )
    (net (code "406") (name "unconnected-(U10-CT-Pad4)") (class "Default")
      (node (ref "U10") (pin "4") (pinfunction "CT_4") (pintype "output"))
    )
    (net (code "407") (name "unconnected-(U11-NC-Pad1)") (class "Default")
      (node (ref "U11") (pin "1") (pinfunction "NC_1") (pintype "no_connect"))
    )
    (net (code "408") (name "unconnected-(U11-NC-Pad5)") (class "Default")
      (node (ref "U11") (pin "5") (pinfunction "NC_5") (pintype "no_connect"))
    )
    (net (code "409") (name "unconnected-(Y1-NC-Pad1)") (class "Default")
      (node (ref "Y1") (pin "1") (pinfunction "NC_1") (pintype "bidirectional"))
    )
  )
)
